# tc08nh.net
KiCad netlist of a schematic drawn in EAGLE
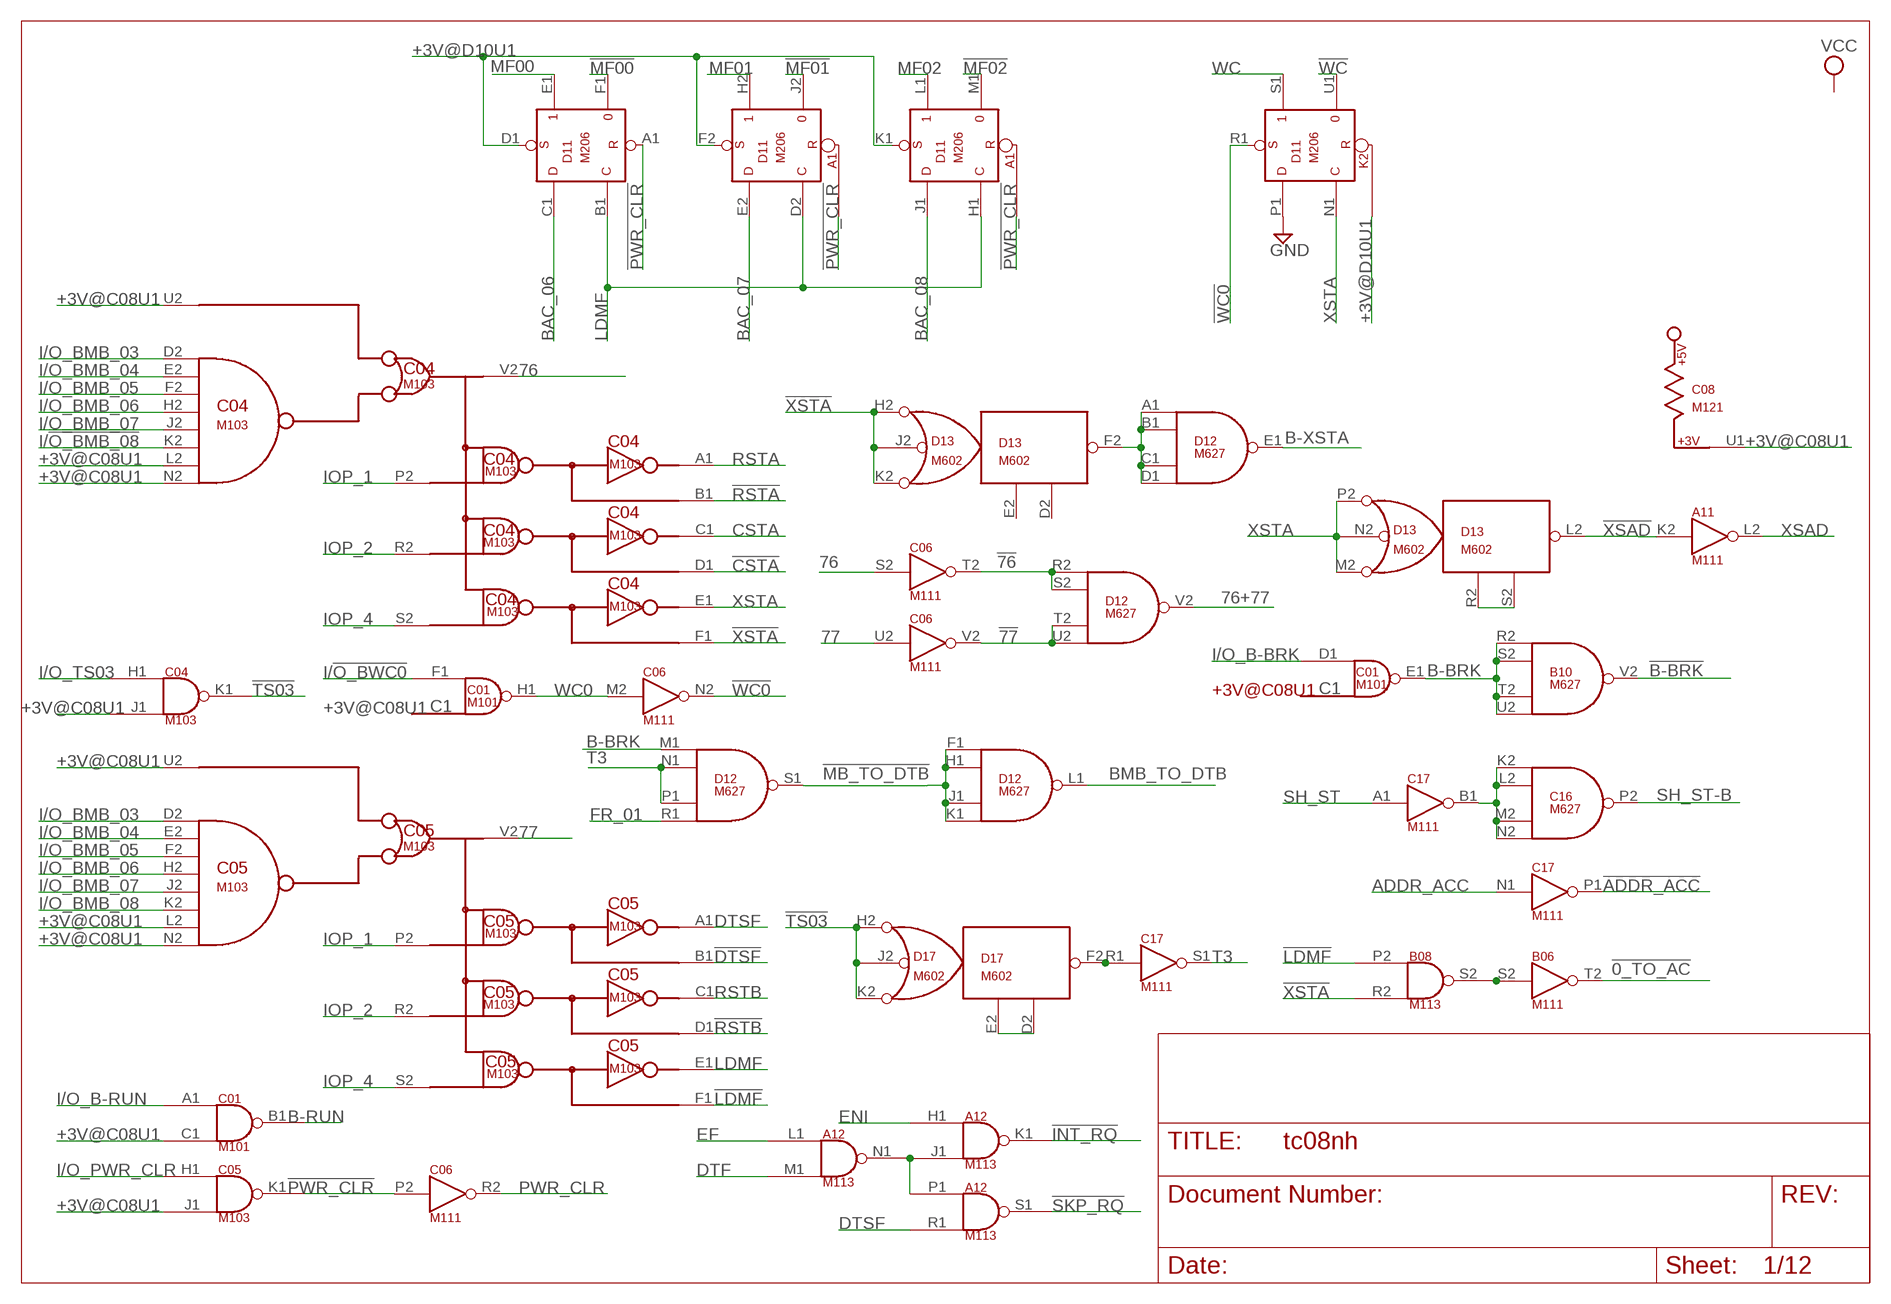
[diagram p0: schematic, sheet 1]
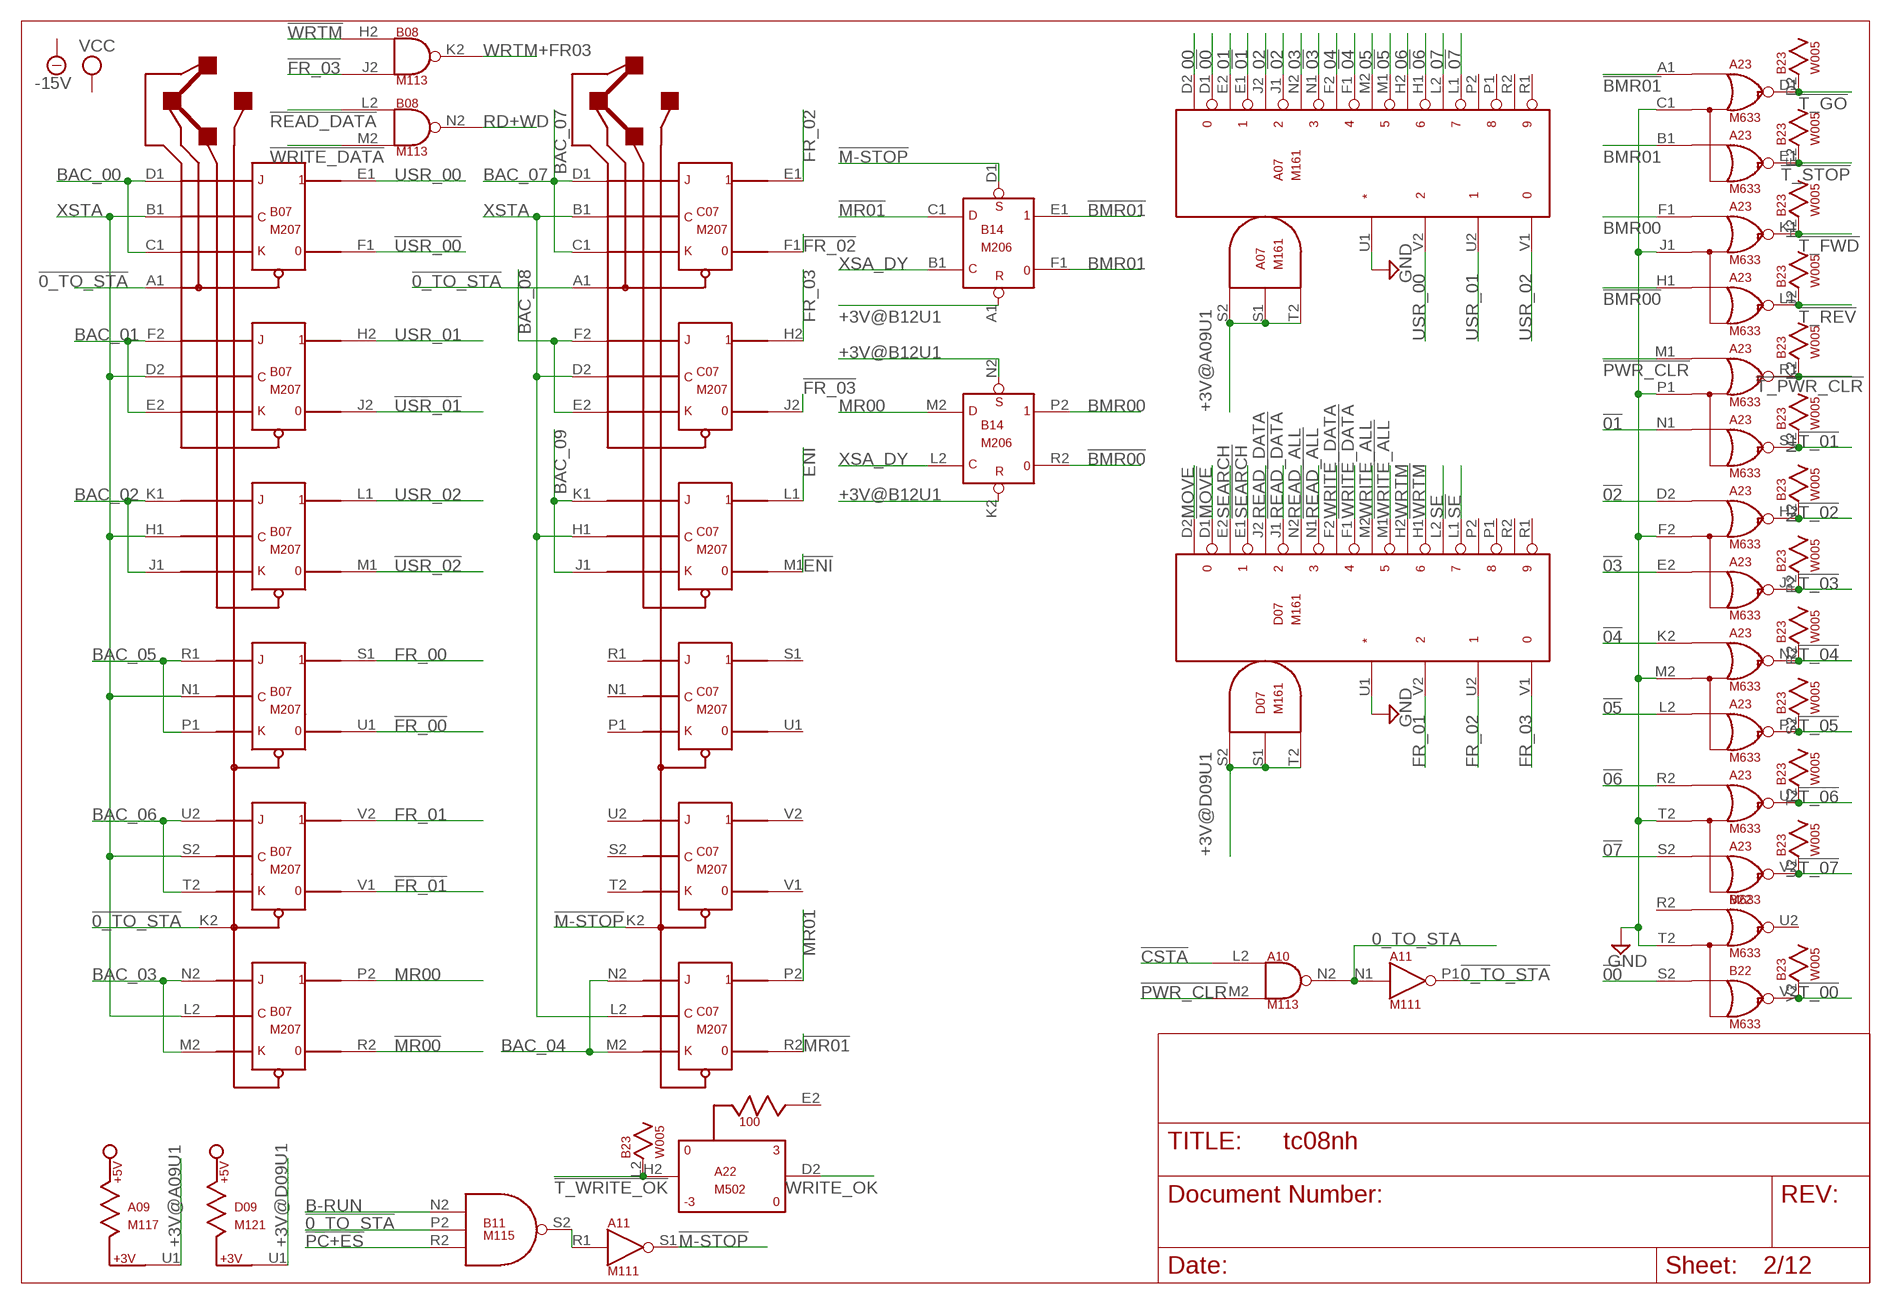
[diagram p1: schematic, sheet 2]
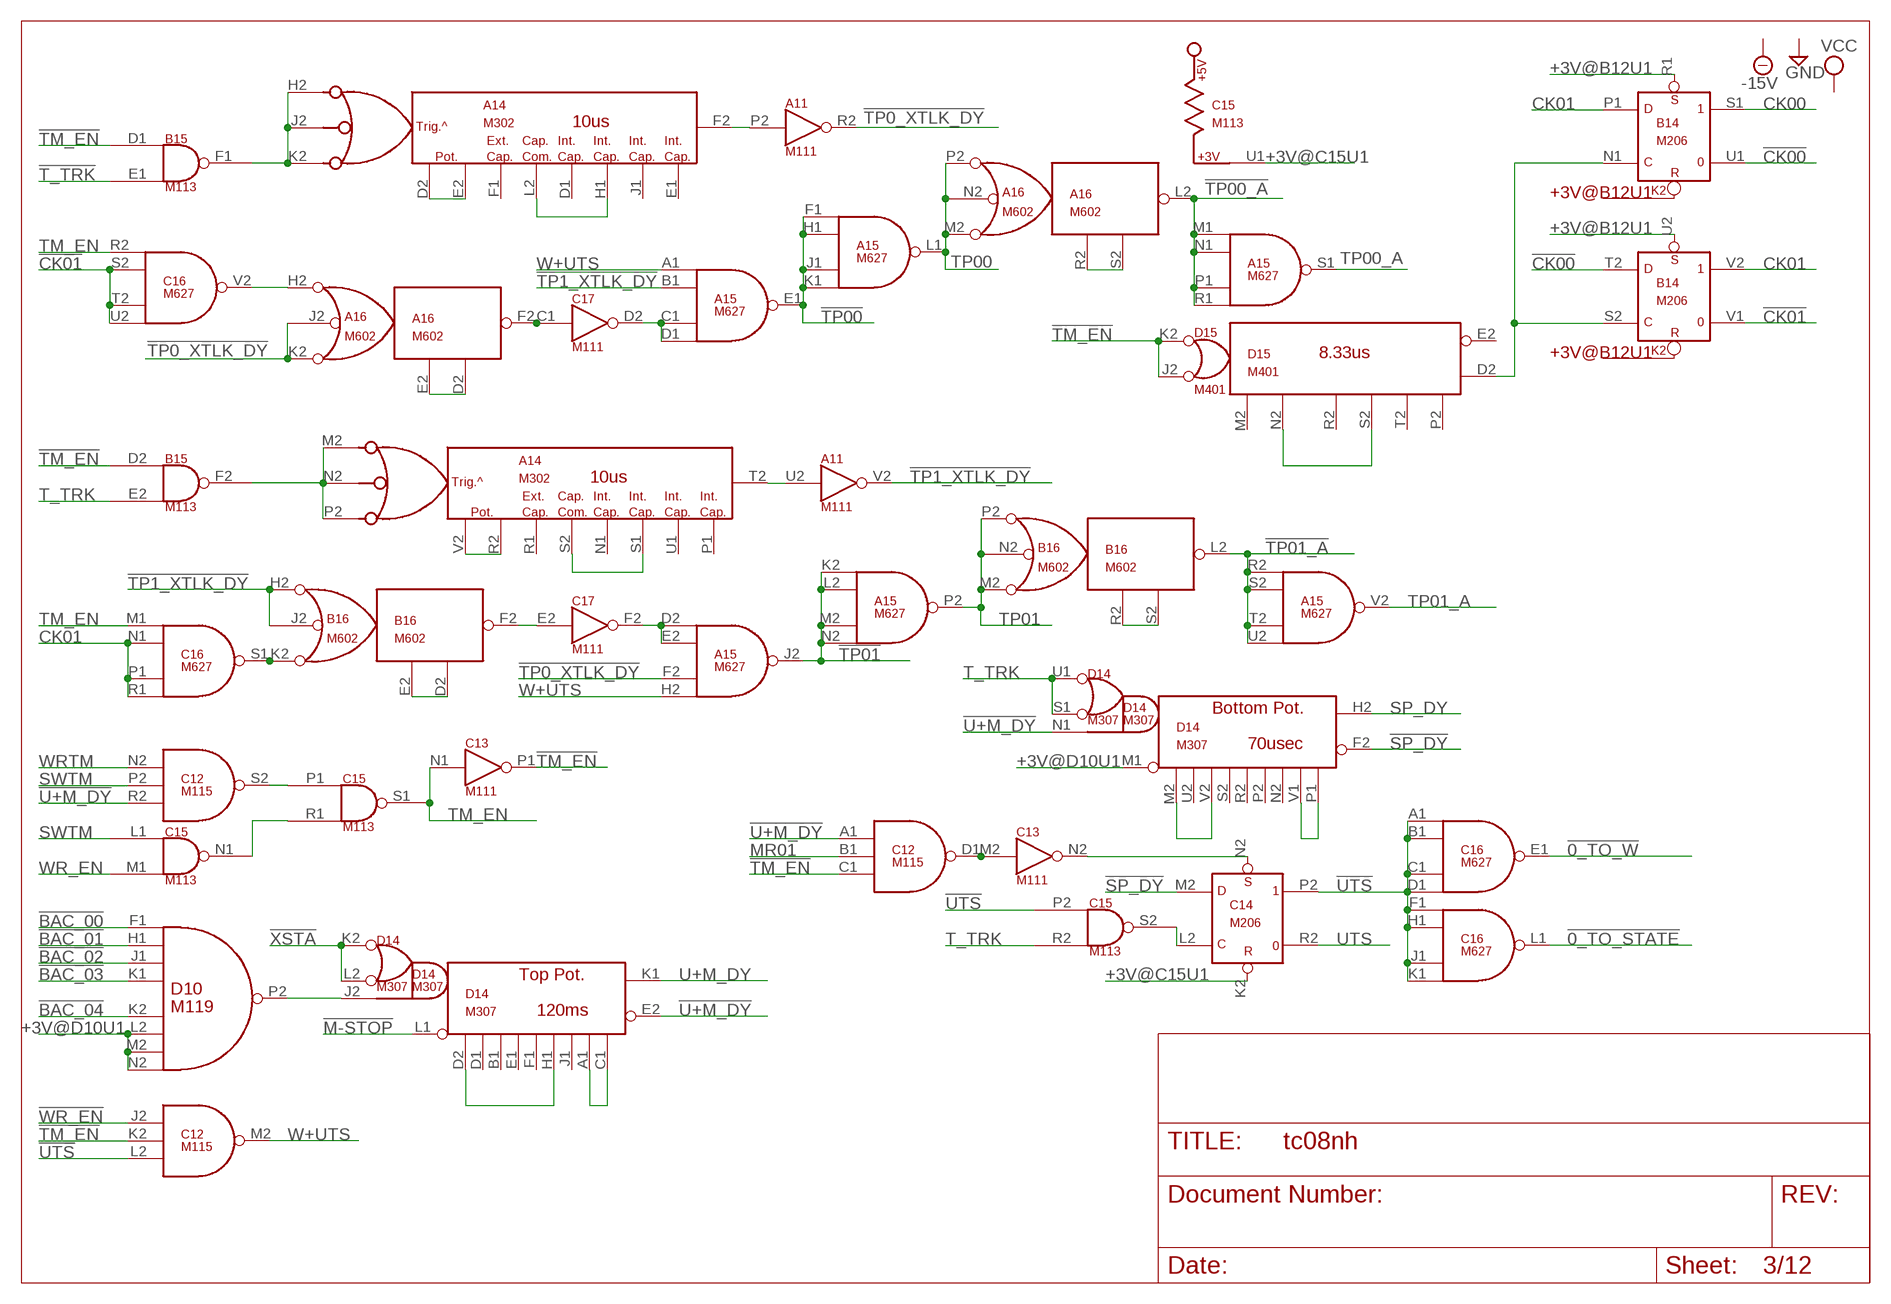
[diagram p2: schematic, sheet 3]
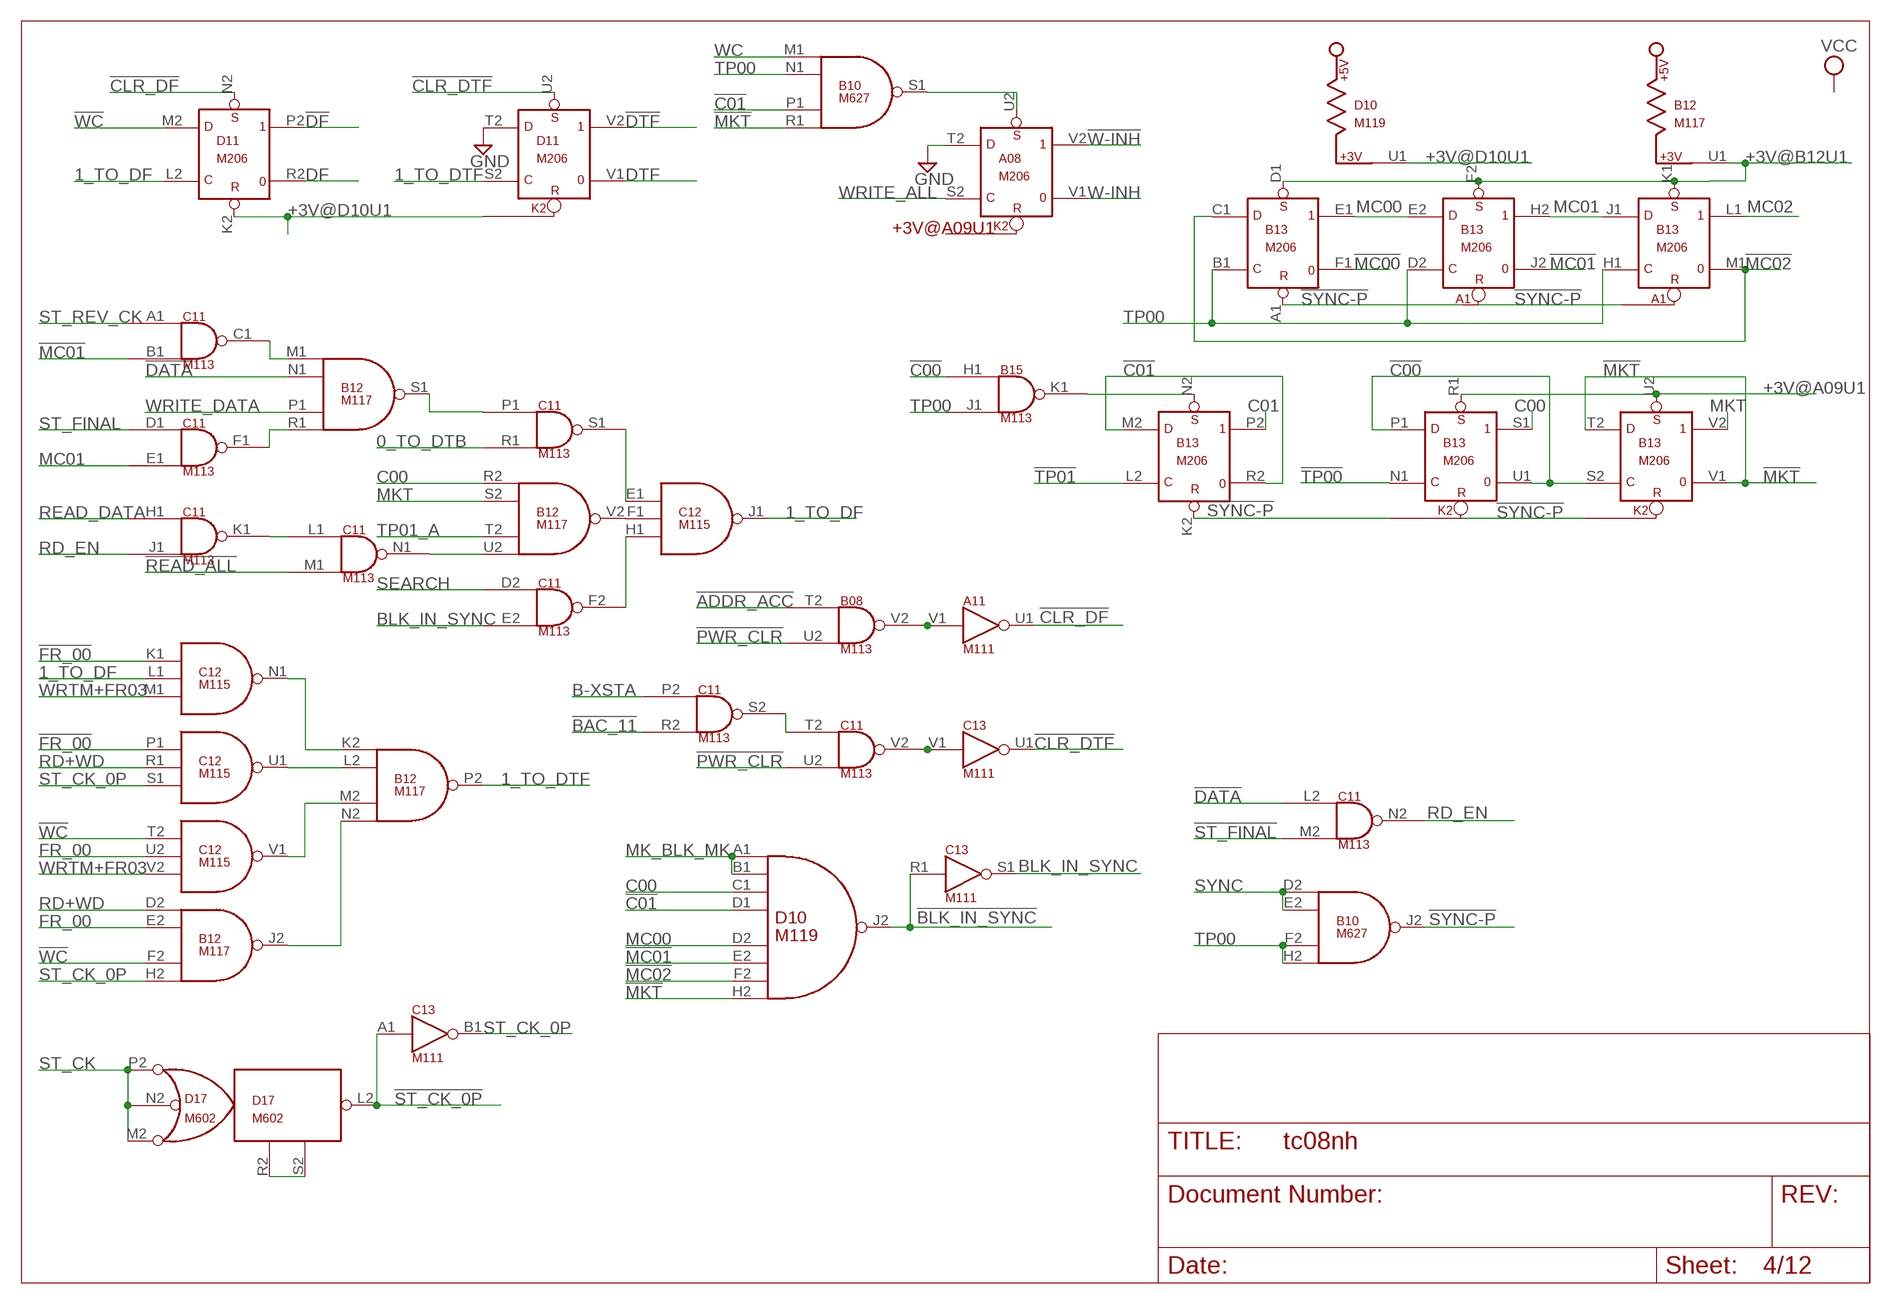
[diagram p3: schematic, sheet 4]
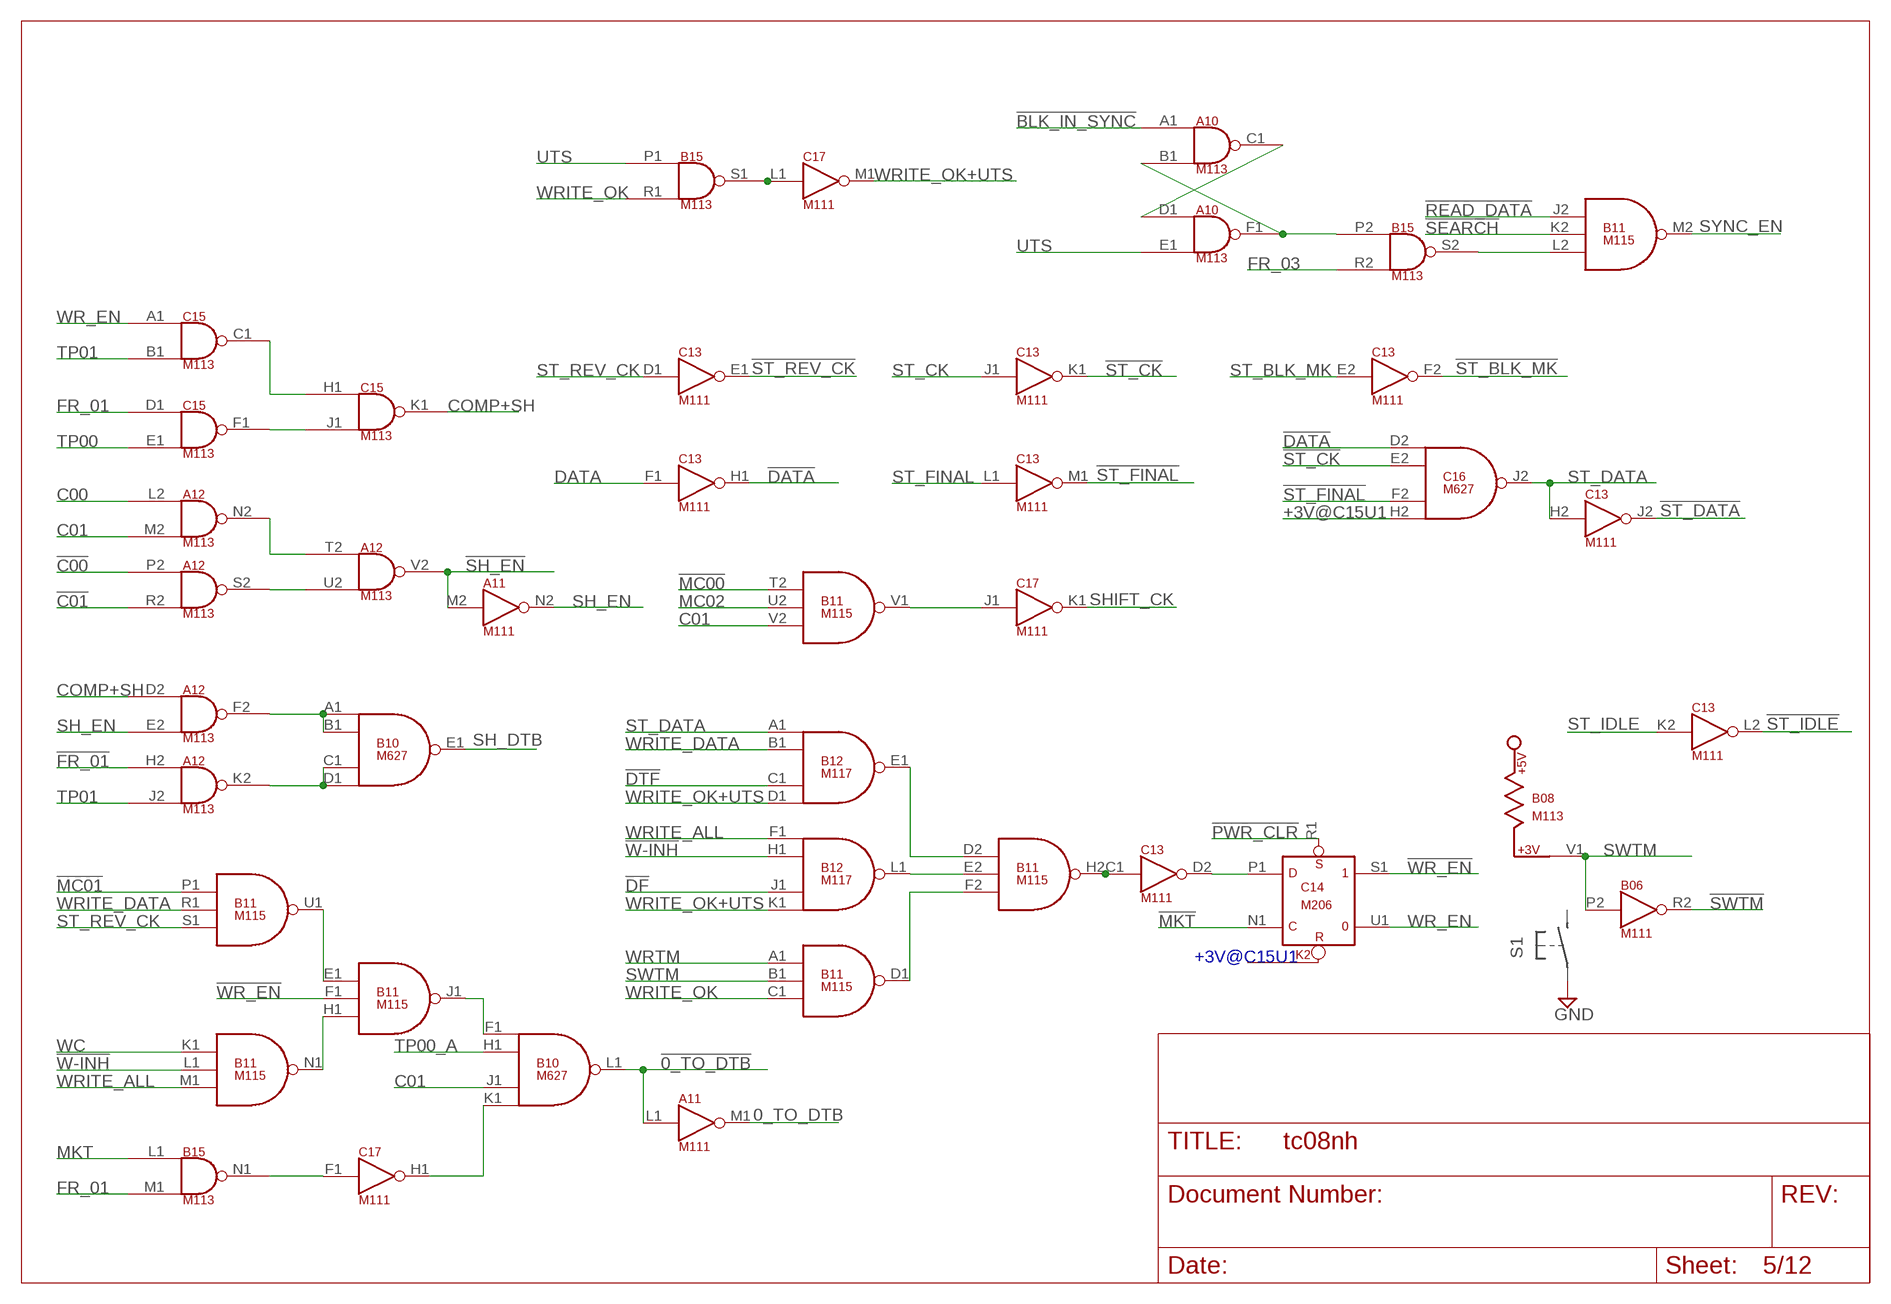
[diagram p4: schematic, sheet 5]
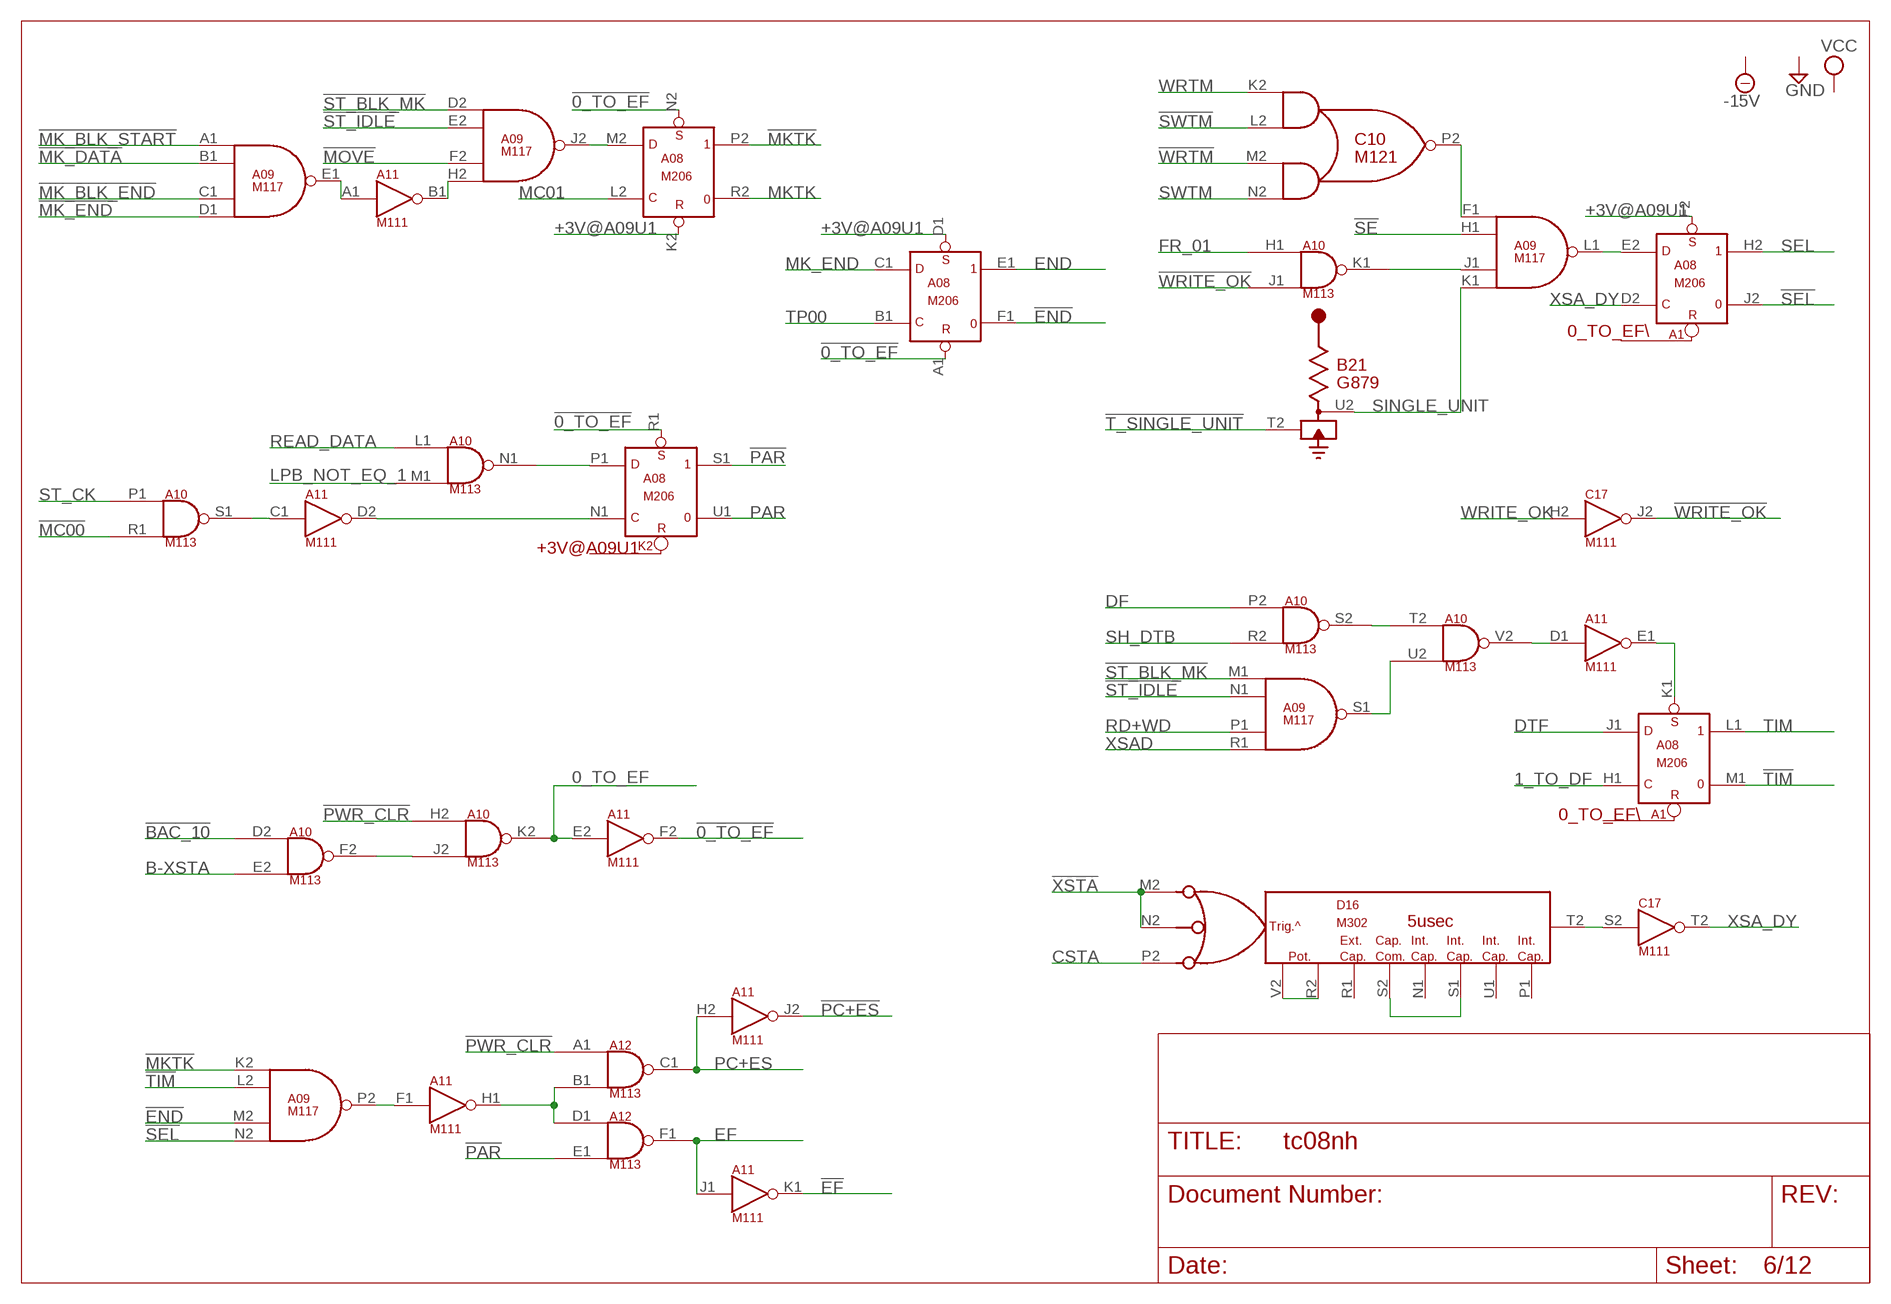
[diagram p5: schematic, sheet 6]
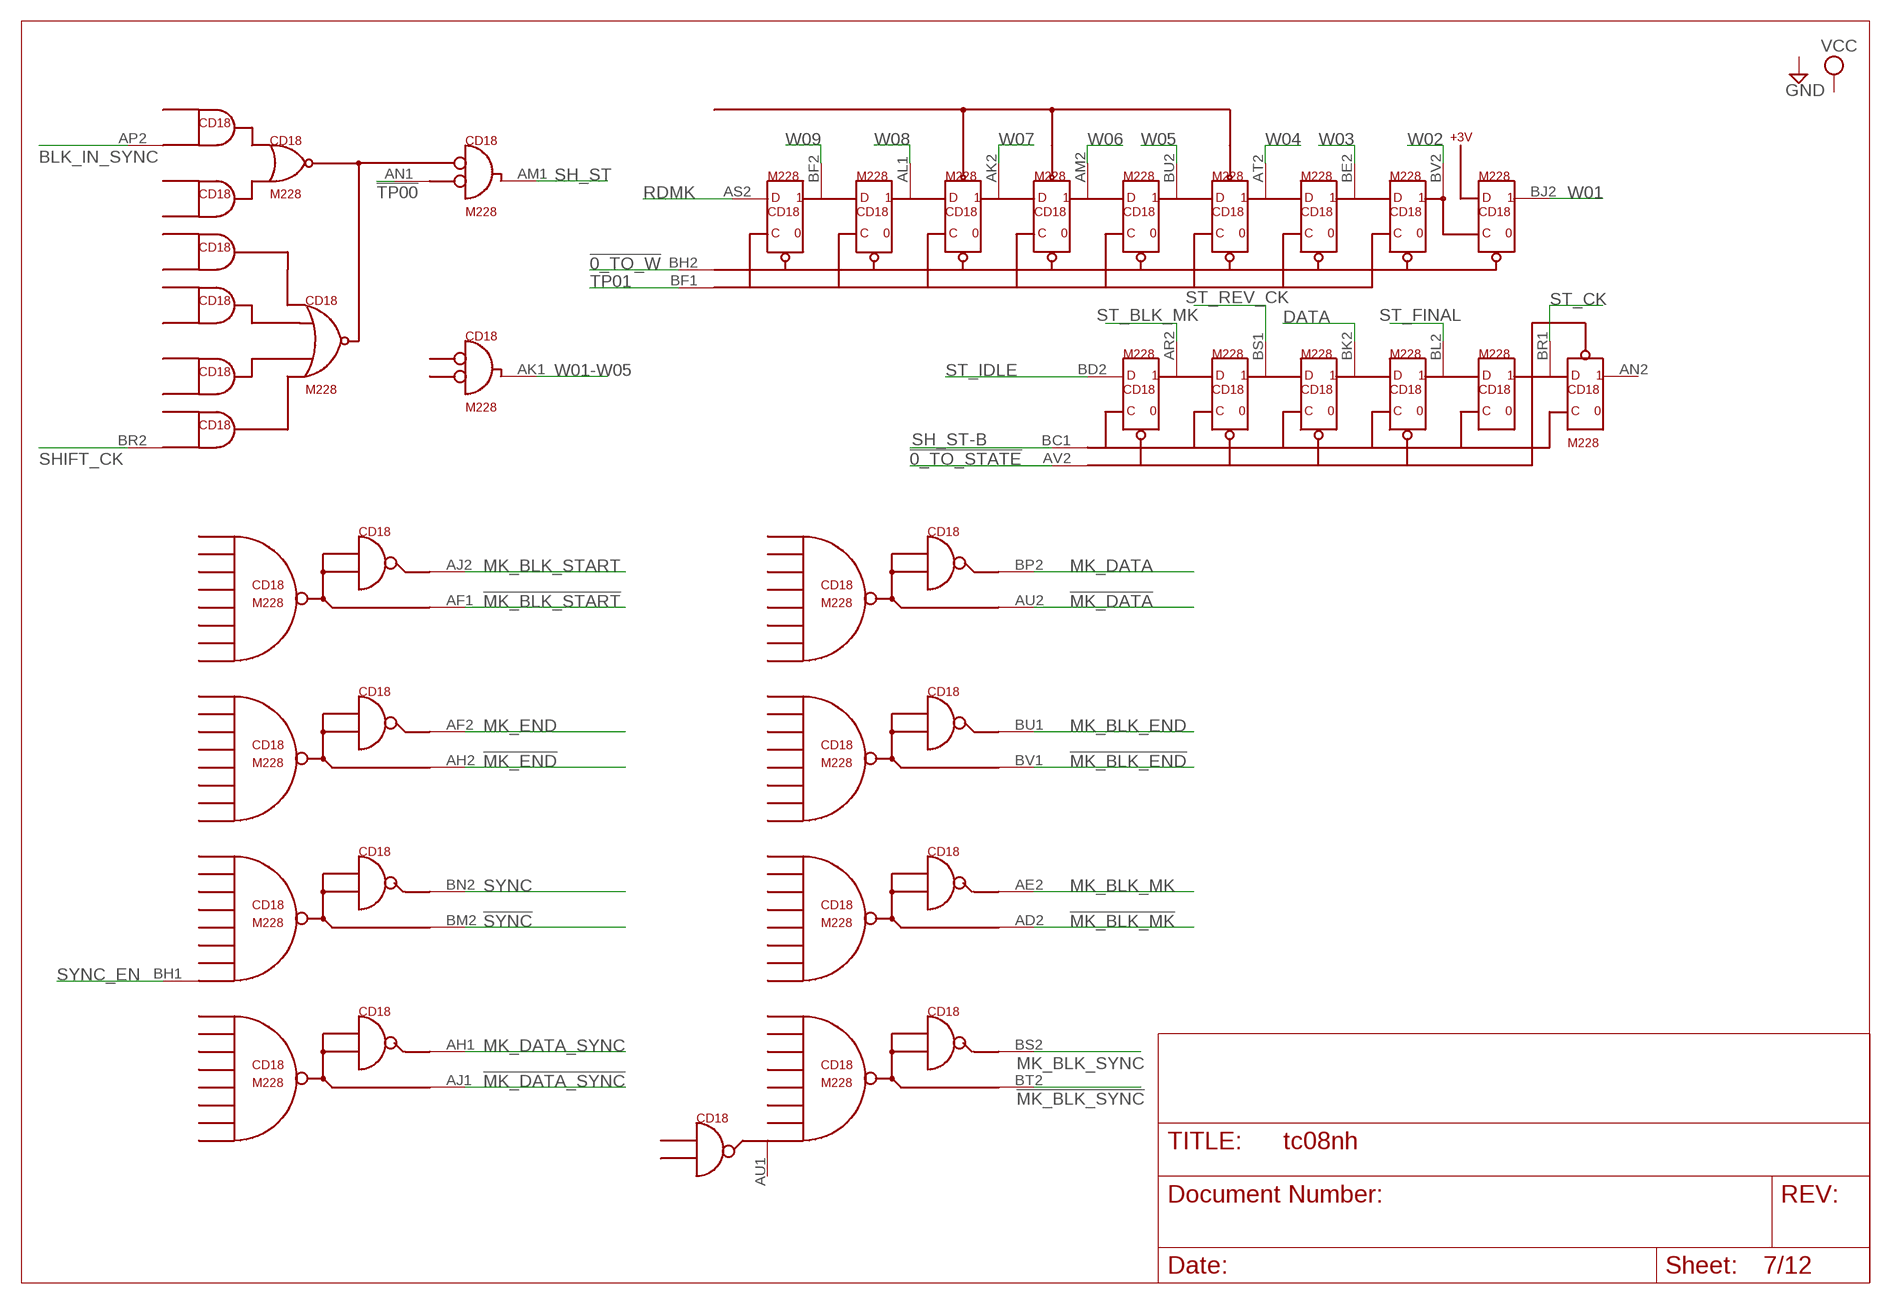
[diagram p6: schematic, sheet 7]
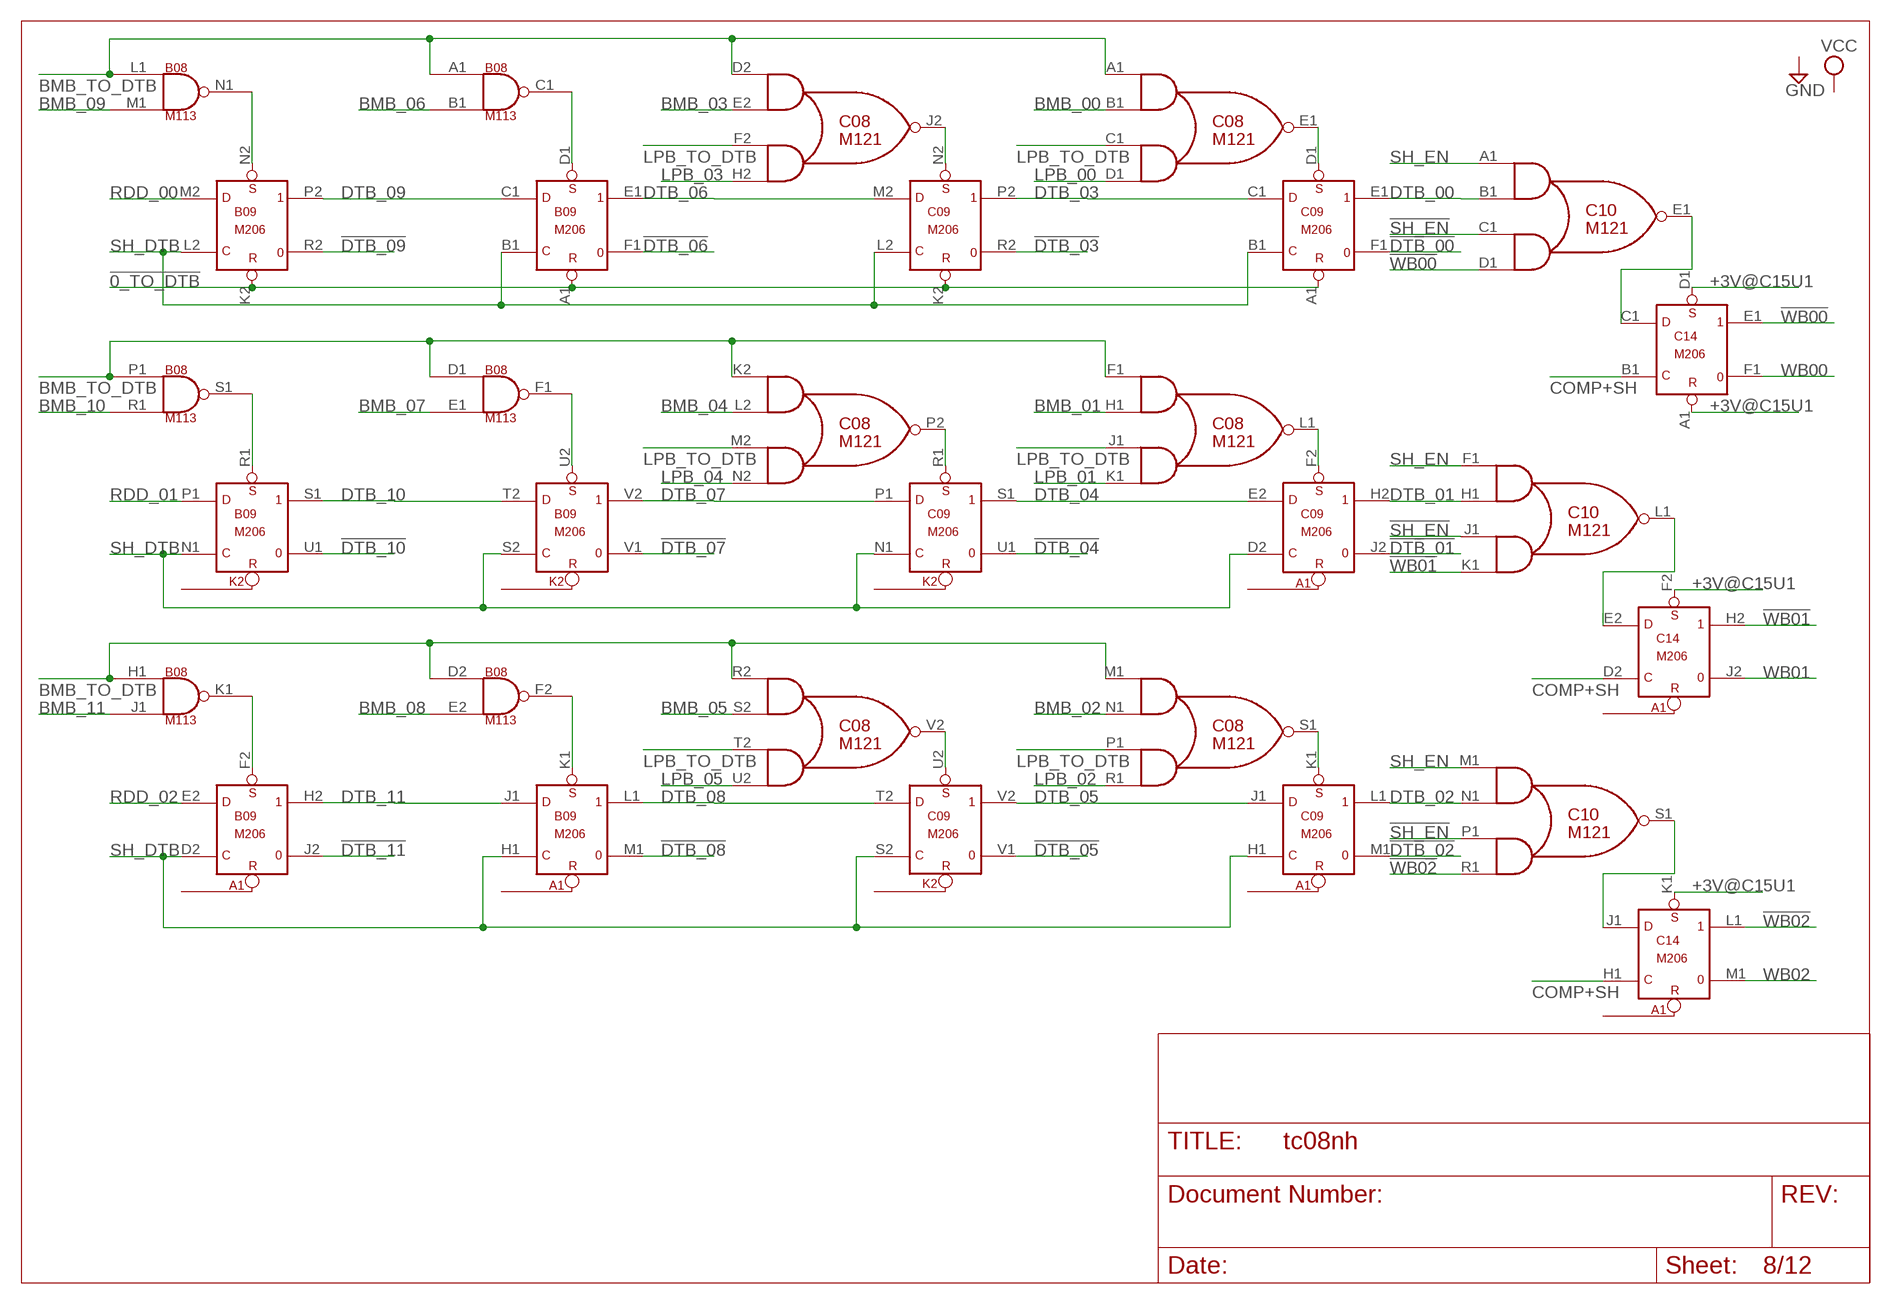
[diagram p7: schematic, sheet 8]
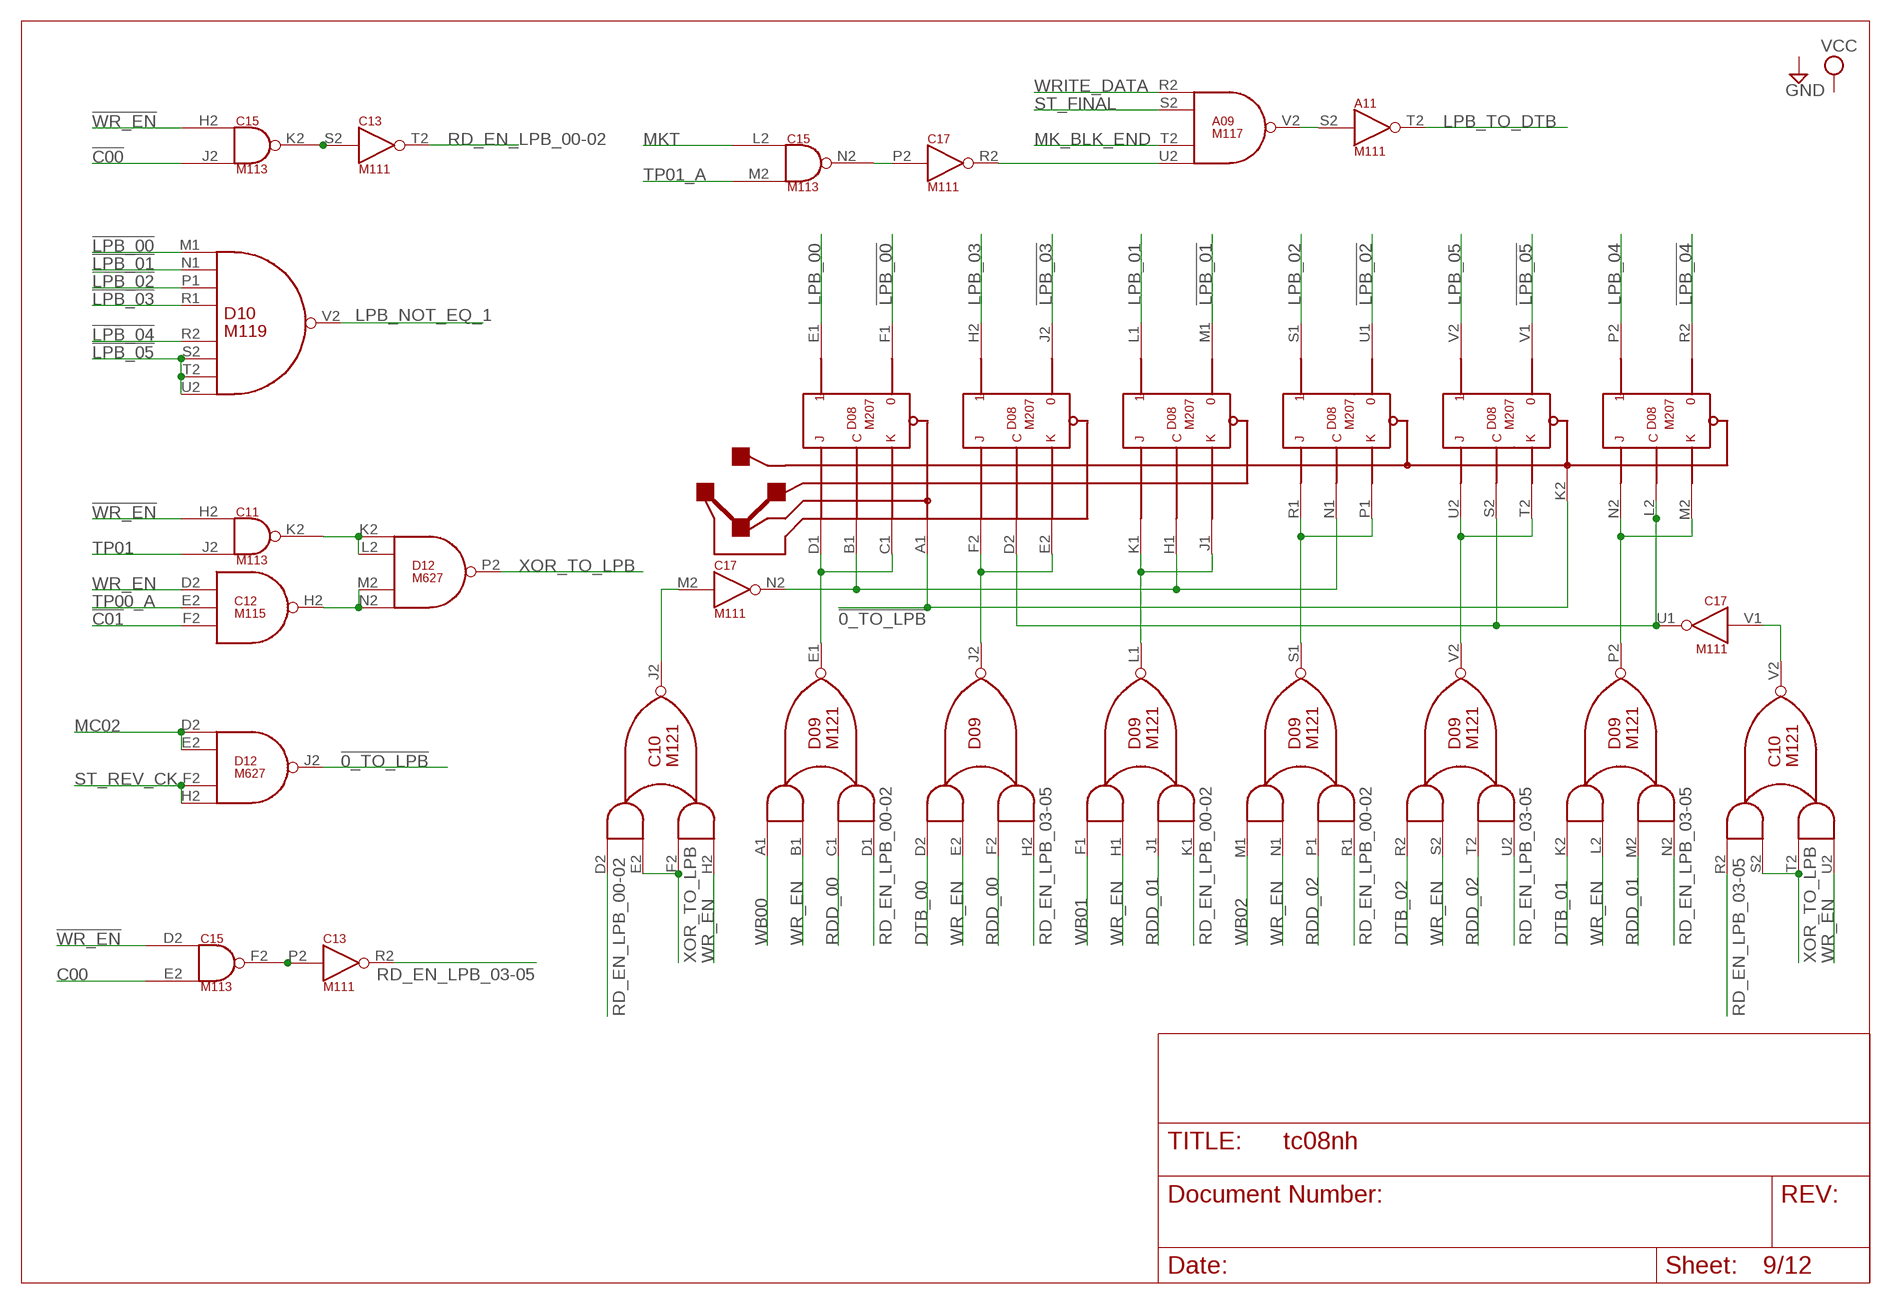
[diagram p8: schematic, sheet 9]
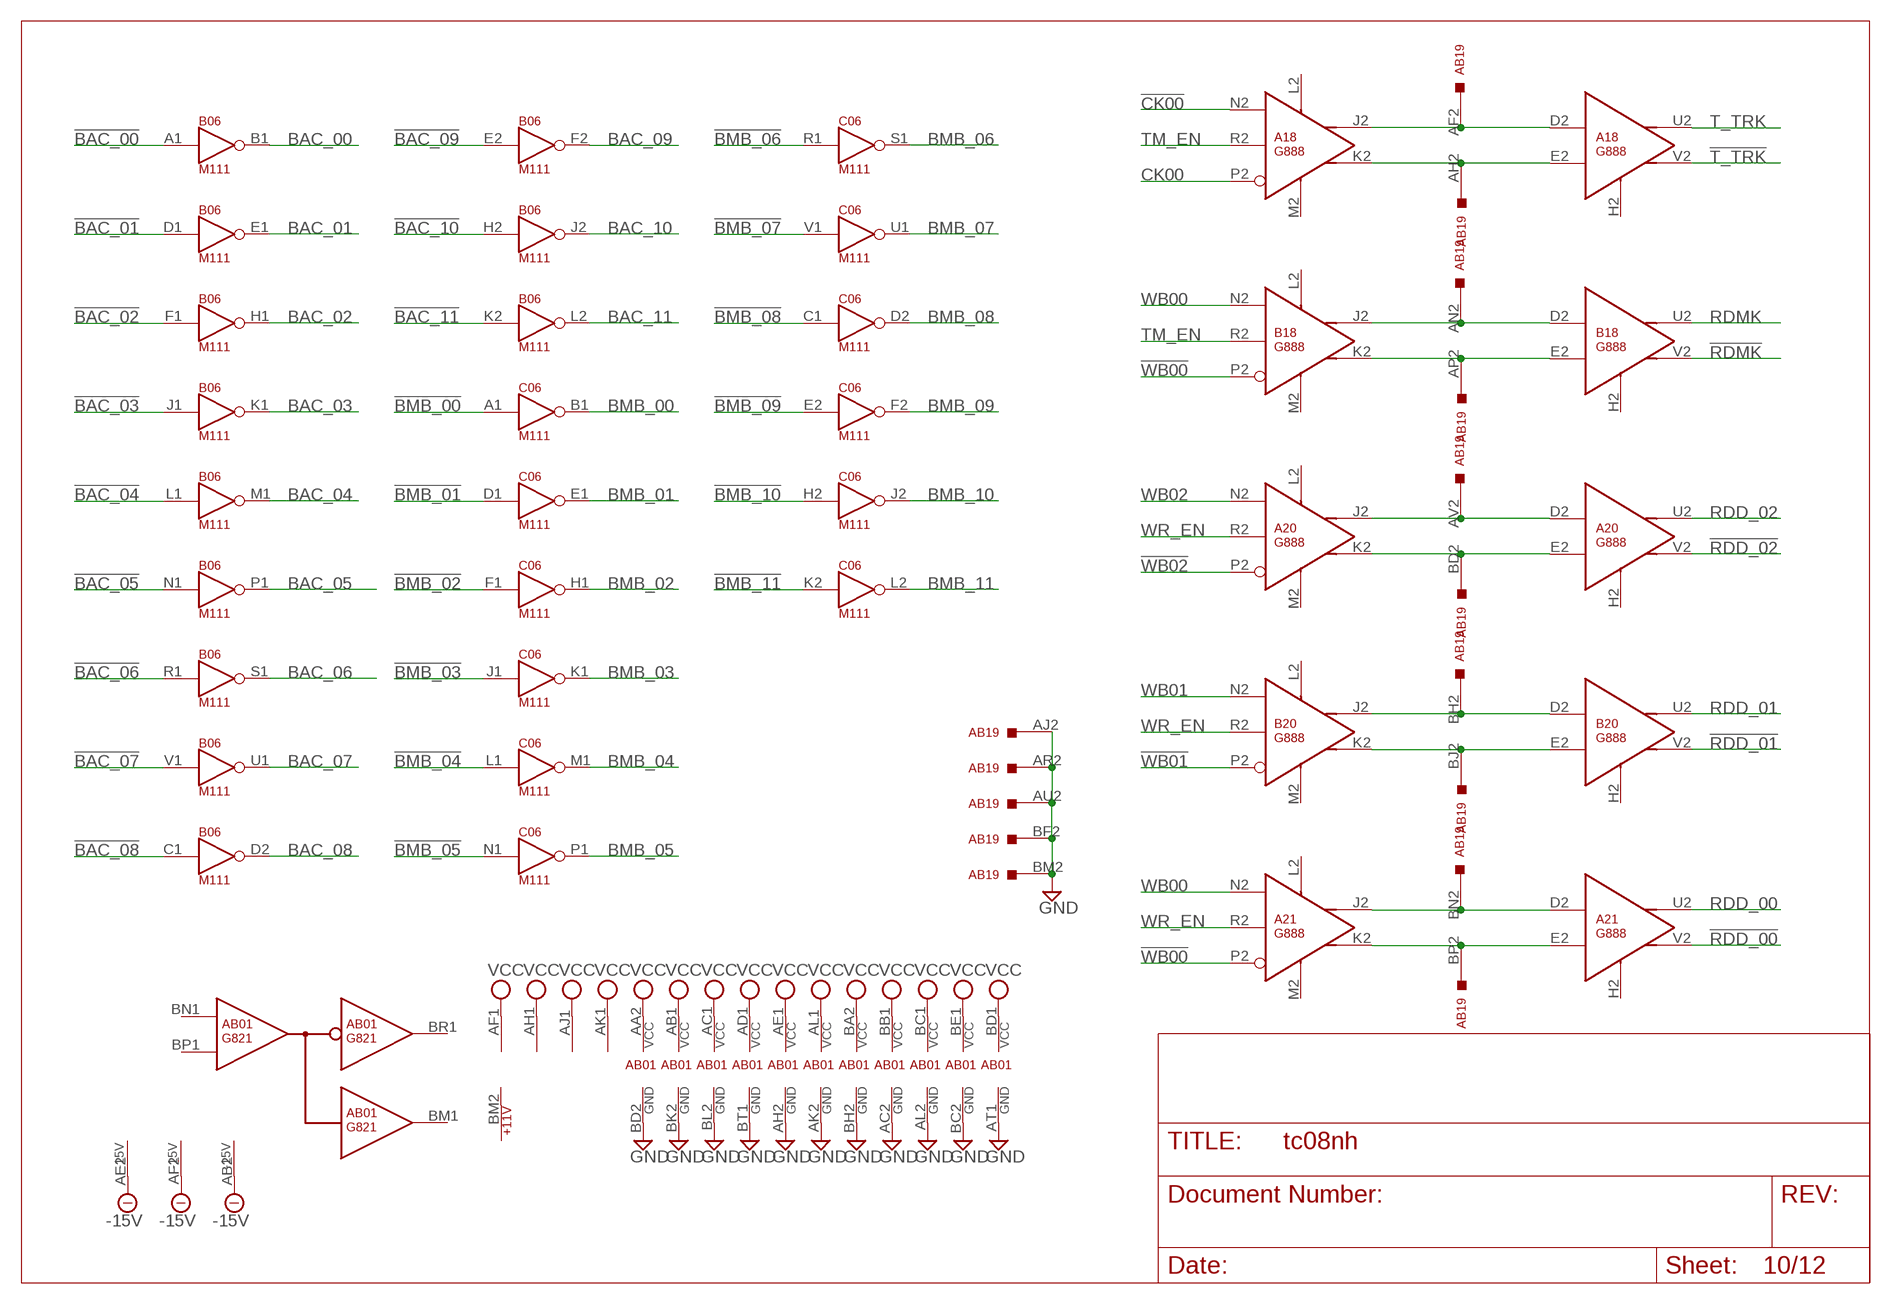
[diagram p9: schematic, sheet 10]
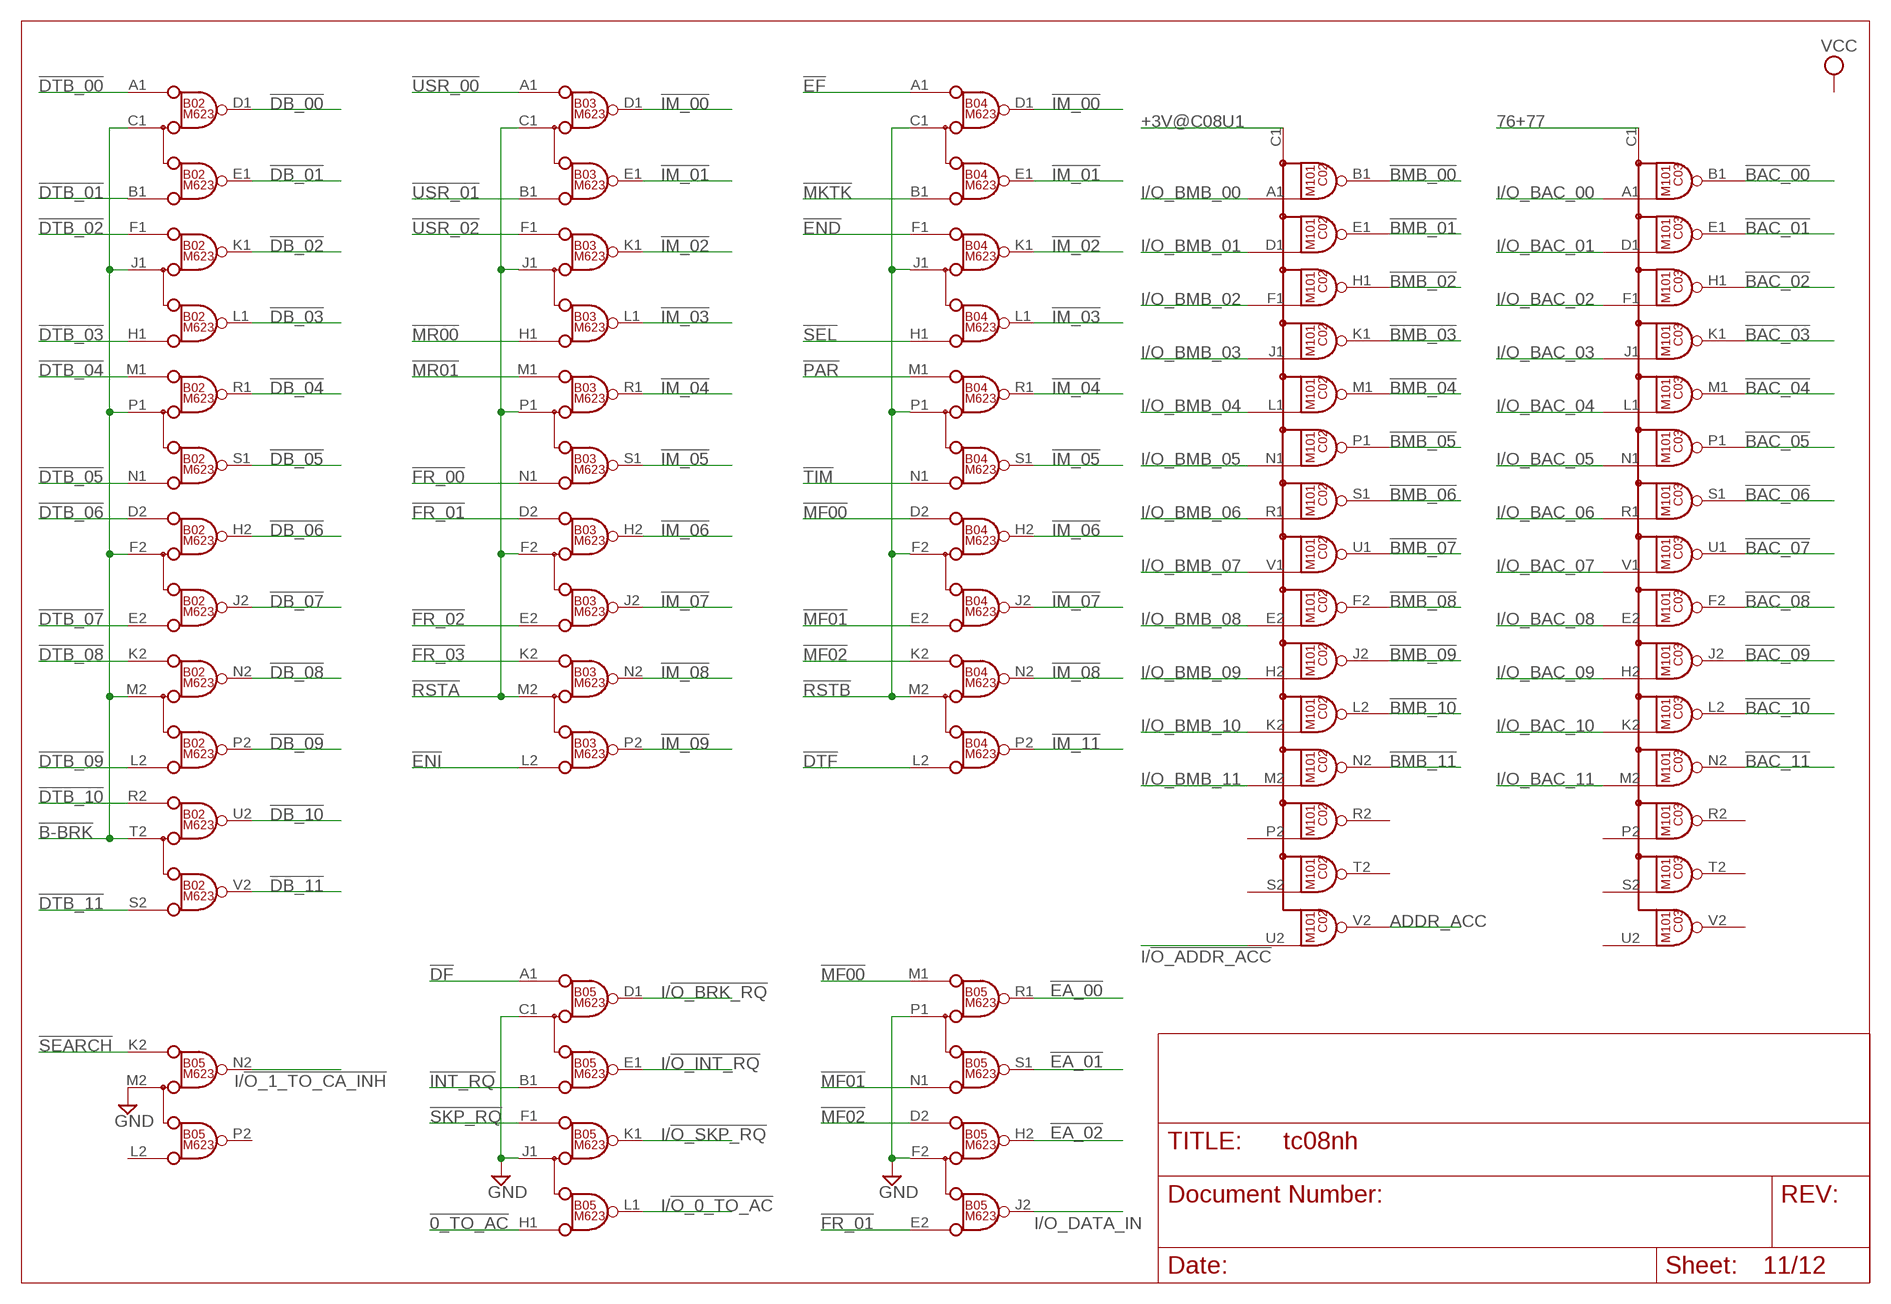
[diagram p10: schematic, sheet 11]
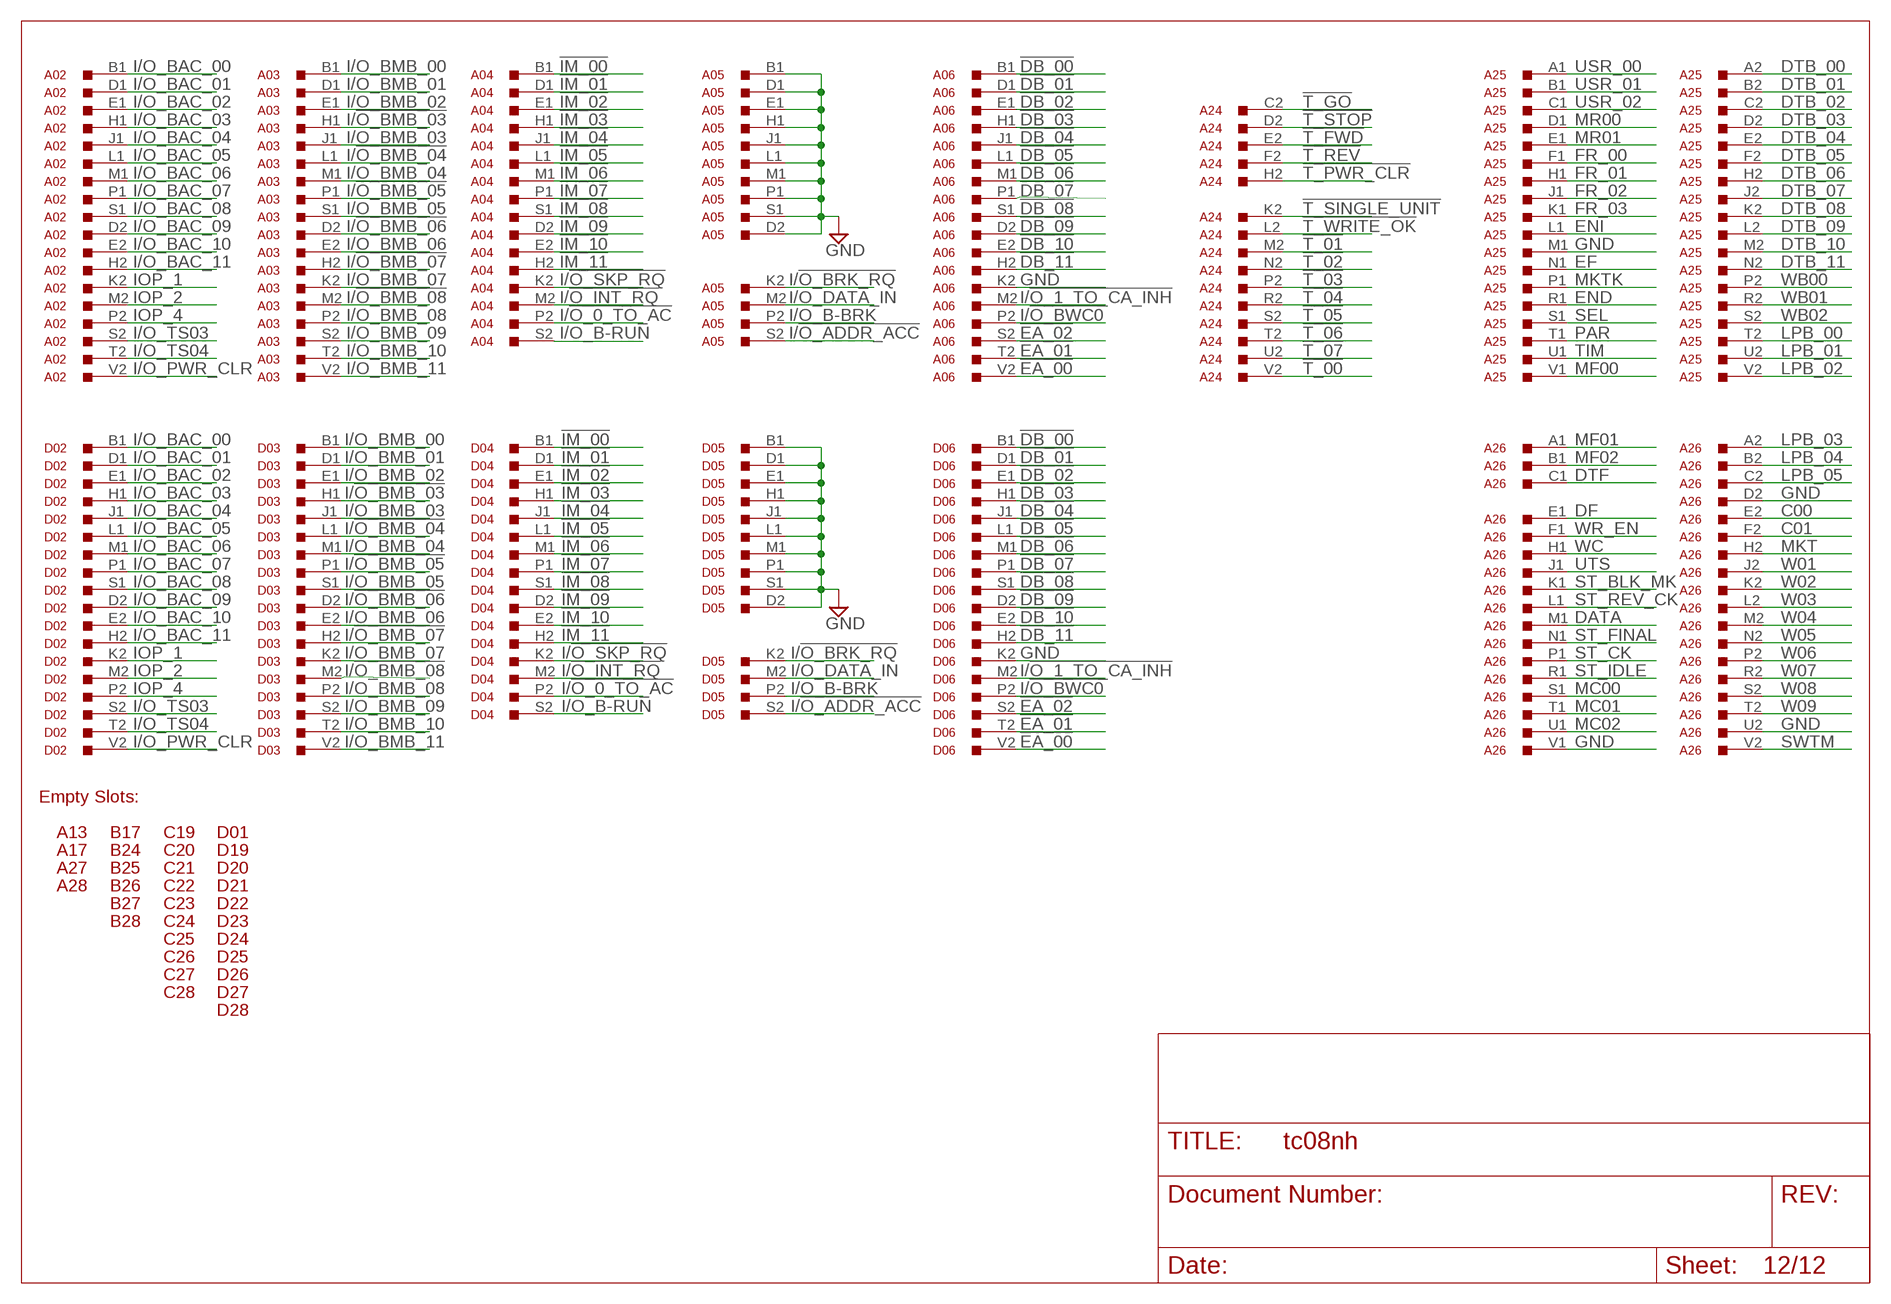
[diagram p11: schematic, sheet 12]

(export (version "E")
  (design (tool "Eeschema 10.0.6"))
  (components
    (comp (ref "B08")
      (value "M113")
      (footprint "eagle-import:H807")
      (libsource (lib "eagle-import") (part "M113"))
    )
    (comp (ref "B09")
      (value "M206")
      (footprint "eagle-import:H807")
      (libsource (lib "eagle-import") (part "M206X"))
    )
    (comp (ref "C08")
      (value "M121")
      (footprint "eagle-import:H807")
      (libsource (lib "eagle-import") (part "M121"))
    )
    (comp (ref "C09")
      (value "M206")
      (footprint "eagle-import:H807")
      (libsource (lib "eagle-import") (part "M206X"))
    )
    (comp (ref "C10")
      (value "M121")
      (footprint "eagle-import:H807")
      (libsource (lib "eagle-import") (part "M121"))
    )
    (comp (ref "C14")
      (value "M206")
      (footprint "eagle-import:H807")
      (libsource (lib "eagle-import") (part "M206X"))
    )
    (comp (ref "A09")
      (value "M117")
      (footprint "eagle-import:H807")
      (libsource (lib "eagle-import") (part "M117"))
    )
    (comp (ref "A11")
      (value "M111")
      (footprint "eagle-import:H807")
      (libsource (lib "eagle-import") (part "M111"))
    )
    (comp (ref "C11")
      (value "M113")
      (footprint "eagle-import:H807")
      (libsource (lib "eagle-import") (part "M113"))
    )
    (comp (ref "C12")
      (value "M115")
      (footprint "eagle-import:H807")
      (libsource (lib "eagle-import") (part "M115"))
    )
    (comp (ref "C13")
      (value "M111")
      (footprint "eagle-import:H807")
      (libsource (lib "eagle-import") (part "M111"))
    )
    (comp (ref "C15")
      (value "M113")
      (footprint "eagle-import:H807")
      (libsource (lib "eagle-import") (part "M113"))
    )
    (comp (ref "C17")
      (value "M111")
      (footprint "eagle-import:H807")
      (libsource (lib "eagle-import") (part "M111"))
    )
    (comp (ref "D08")
      (value "M207")
      (footprint "eagle-import:H807")
      (libsource (lib "eagle-import") (part "M207"))
    )
    (comp (ref "D09")
      (value "M121")
      (footprint "eagle-import:H807")
      (libsource (lib "eagle-import") (part "M121"))
    )
    (comp (ref "D10")
      (value "M119")
      (footprint "eagle-import:H807")
      (libsource (lib "eagle-import") (part "M119"))
    )
    (comp (ref "D12")
      (value "M627")
      (footprint "eagle-import:H807")
      (libsource (lib "eagle-import") (part "M627"))
    )
    (comp (ref "A08")
      (value "M206")
      (footprint "eagle-import:H807")
      (libsource (lib "eagle-import") (part "M206X"))
    )
    (comp (ref "B10")
      (value "M627")
      (footprint "eagle-import:H807")
      (libsource (lib "eagle-import") (part "M627"))
    )
    (comp (ref "B12")
      (value "M117")
      (footprint "eagle-import:H807")
      (libsource (lib "eagle-import") (part "M117"))
    )
    (comp (ref "B13")
      (value "M206")
      (footprint "eagle-import:H807")
      (libsource (lib "eagle-import") (part "M206X"))
    )
    (comp (ref "B15")
      (value "M113")
      (footprint "eagle-import:H807")
      (libsource (lib "eagle-import") (part "M113"))
    )
    (comp (ref "D11")
      (value "M206")
      (footprint "eagle-import:H807")
      (libsource (lib "eagle-import") (part "M206X"))
    )
    (comp (ref "D17")
      (value "M602")
      (footprint "eagle-import:H807")
      (libsource (lib "eagle-import") (part "M602"))
    )
    (comp (ref "A14")
      (value "M302")
      (footprint "eagle-import:H807")
      (libsource (lib "eagle-import") (part "M302"))
    )
    (comp (ref "A15")
      (value "M627")
      (footprint "eagle-import:H807")
      (libsource (lib "eagle-import") (part "M627"))
    )
    (comp (ref "A16")
      (value "M602")
      (footprint "eagle-import:H807")
      (libsource (lib "eagle-import") (part "M602"))
    )
    (comp (ref "B14")
      (value "M206")
      (footprint "eagle-import:H807")
      (libsource (lib "eagle-import") (part "M206X"))
    )
    (comp (ref "B16")
      (value "M602")
      (footprint "eagle-import:H807")
      (libsource (lib "eagle-import") (part "M602"))
    )
    (comp (ref "C16")
      (value "M627")
      (footprint "eagle-import:H807")
      (libsource (lib "eagle-import") (part "M627"))
    )
    (comp (ref "D14")
      (value "M307")
      (footprint "eagle-import:H807")
      (libsource (lib "eagle-import") (part "M307"))
    )
    (comp (ref "D15")
      (value "M401")
      (footprint "eagle-import:H807")
      (libsource (lib "eagle-import") (part "M401"))
    )
    (comp (ref "B02")
      (value "M623")
      (footprint "eagle-import:H807")
      (libsource (lib "eagle-import") (part "M623"))
    )
    (comp (ref "B03")
      (value "M623")
      (footprint "eagle-import:H807")
      (libsource (lib "eagle-import") (part "M623"))
    )
    (comp (ref "B04")
      (value "M623")
      (footprint "eagle-import:H807")
      (libsource (lib "eagle-import") (part "M623"))
    )
    (comp (ref "B05")
      (value "M623")
      (footprint "eagle-import:H807")
      (libsource (lib "eagle-import") (part "M623"))
    )
    (comp (ref "C02")
      (value "M101")
      (footprint "eagle-import:H807")
      (libsource (lib "eagle-import") (part "M101-ARRAY"))
    )
    (comp (ref "C03")
      (value "M101")
      (footprint "eagle-import:H807")
      (libsource (lib "eagle-import") (part "M101-ARRAY"))
    )
    (comp (ref "A02")
      (value "M903")
      (footprint "eagle-import:H807")
      (libsource (lib "eagle-import") (part "M903"))
    )
    (comp (ref "A03")
      (value "M903")
      (footprint "eagle-import:H807")
      (libsource (lib "eagle-import") (part "M903"))
    )
    (comp (ref "A04")
      (value "M903")
      (footprint "eagle-import:H807")
      (libsource (lib "eagle-import") (part "M903"))
    )
    (comp (ref "A05")
      (value "M903")
      (footprint "eagle-import:H807")
      (libsource (lib "eagle-import") (part "M903"))
    )
    (comp (ref "A06")
      (value "M903")
      (footprint "eagle-import:H807")
      (libsource (lib "eagle-import") (part "M903"))
    )
    (comp (ref "A13")
      (value "H807")
      (footprint "eagle-import:H807")
      (libsource (lib "eagle-import") (part "H807"))
    )
    (comp (ref "A17")
      (value "H807")
      (footprint "eagle-import:H807")
      (libsource (lib "eagle-import") (part "H807"))
    )
    (comp (ref "A24")
      (value "W023")
      (footprint "eagle-import:H807")
      (libsource (lib "eagle-import") (part "W023"))
    )
    (comp (ref "A25")
      (value "M916")
      (footprint "eagle-import:H807")
      (libsource (lib "eagle-import") (part "M916"))
    )
    (comp (ref "A26")
      (value "M916")
      (footprint "eagle-import:H807")
      (libsource (lib "eagle-import") (part "M916"))
    )
    (comp (ref "A27")
      (value "H807")
      (footprint "eagle-import:H807")
      (libsource (lib "eagle-import") (part "H807"))
    )
    (comp (ref "A28")
      (value "H807")
      (footprint "eagle-import:H807")
      (libsource (lib "eagle-import") (part "H807"))
    )
    (comp (ref "B17")
      (value "H807")
      (footprint "eagle-import:H807")
      (libsource (lib "eagle-import") (part "H807"))
    )
    (comp (ref "B24")
      (value "H807")
      (footprint "eagle-import:H807")
      (libsource (lib "eagle-import") (part "H807"))
    )
    (comp (ref "B25")
      (value "H807")
      (footprint "eagle-import:H807")
      (libsource (lib "eagle-import") (part "H807"))
    )
    (comp (ref "B26")
      (value "H807")
      (footprint "eagle-import:H807")
      (libsource (lib "eagle-import") (part "H807"))
    )
    (comp (ref "B27")
      (value "H807")
      (footprint "eagle-import:H807")
      (libsource (lib "eagle-import") (part "H807"))
    )
    (comp (ref "B28")
      (value "H807")
      (footprint "eagle-import:H807")
      (libsource (lib "eagle-import") (part "H807"))
    )
    (comp (ref "C19")
      (value "H807")
      (footprint "eagle-import:H807")
      (libsource (lib "eagle-import") (part "H807"))
    )
    (comp (ref "C20")
      (value "H807")
      (footprint "eagle-import:H807")
      (libsource (lib "eagle-import") (part "H807"))
    )
    (comp (ref "C21")
      (value "H807")
      (footprint "eagle-import:H807")
      (libsource (lib "eagle-import") (part "H807"))
    )
    (comp (ref "C22")
      (value "H807")
      (footprint "eagle-import:H807")
      (libsource (lib "eagle-import") (part "H807"))
    )
    (comp (ref "C23")
      (value "H807")
      (footprint "eagle-import:H807")
      (libsource (lib "eagle-import") (part "H807"))
    )
    (comp (ref "C24")
      (value "H807")
      (footprint "eagle-import:H807")
      (libsource (lib "eagle-import") (part "H807"))
    )
    (comp (ref "C25")
      (value "H807")
      (footprint "eagle-import:H807")
      (libsource (lib "eagle-import") (part "H807"))
    )
    (comp (ref "C26")
      (value "H807")
      (footprint "eagle-import:H807")
      (libsource (lib "eagle-import") (part "H807"))
    )
    (comp (ref "C27")
      (value "H807")
      (footprint "eagle-import:H807")
      (libsource (lib "eagle-import") (part "H807"))
    )
    (comp (ref "C28")
      (value "H807")
      (footprint "eagle-import:H807")
      (libsource (lib "eagle-import") (part "H807"))
    )
    (comp (ref "D01")
      (value "H807")
      (footprint "eagle-import:H807")
      (libsource (lib "eagle-import") (part "H807"))
    )
    (comp (ref "D02")
      (value "M903")
      (footprint "eagle-import:H807")
      (libsource (lib "eagle-import") (part "M903"))
    )
    (comp (ref "D03")
      (value "M903")
      (footprint "eagle-import:H807")
      (libsource (lib "eagle-import") (part "M903"))
    )
    (comp (ref "D04")
      (value "M903")
      (footprint "eagle-import:H807")
      (libsource (lib "eagle-import") (part "M903"))
    )
    (comp (ref "D05")
      (value "M903")
      (footprint "eagle-import:H807")
      (libsource (lib "eagle-import") (part "M903"))
    )
    (comp (ref "D06")
      (value "M903")
      (footprint "eagle-import:H807")
      (libsource (lib "eagle-import") (part "M903"))
    )
    (comp (ref "D19")
      (value "H807")
      (footprint "eagle-import:H807")
      (libsource (lib "eagle-import") (part "H807"))
    )
    (comp (ref "D20")
      (value "H807")
      (footprint "eagle-import:H807")
      (libsource (lib "eagle-import") (part "H807"))
    )
    (comp (ref "D21")
      (value "H807")
      (footprint "eagle-import:H807")
      (libsource (lib "eagle-import") (part "H807"))
    )
    (comp (ref "D22")
      (value "H807")
      (footprint "eagle-import:H807")
      (libsource (lib "eagle-import") (part "H807"))
    )
    (comp (ref "D23")
      (value "H807")
      (footprint "eagle-import:H807")
      (libsource (lib "eagle-import") (part "H807"))
    )
    (comp (ref "D24")
      (value "H807")
      (footprint "eagle-import:H807")
      (libsource (lib "eagle-import") (part "H807"))
    )
    (comp (ref "D25")
      (value "H807")
      (footprint "eagle-import:H807")
      (libsource (lib "eagle-import") (part "H807"))
    )
    (comp (ref "D26")
      (value "H807")
      (footprint "eagle-import:H807")
      (libsource (lib "eagle-import") (part "H807"))
    )
    (comp (ref "D27")
      (value "H807")
      (footprint "eagle-import:H807")
      (libsource (lib "eagle-import") (part "H807"))
    )
    (comp (ref "D28")
      (value "H807")
      (footprint "eagle-import:H807")
      (libsource (lib "eagle-import") (part "H807"))
    )
    (comp (ref "CD18")
      (value "M228")
      (footprint "eagle-import:H807-2")
      (libsource (lib "eagle-import") (part "M228"))
    )
    (comp (ref "A07")
      (value "M161")
      (footprint "eagle-import:H807")
      (libsource (lib "eagle-import") (part "M161"))
    )
    (comp (ref "A10")
      (value "M113")
      (footprint "eagle-import:H807")
      (libsource (lib "eagle-import") (part "M113"))
    )
    (comp (ref "A22")
      (value "M502")
      (footprint "eagle-import:H807")
      (libsource (lib "eagle-import") (part "M502"))
    )
    (comp (ref "A23")
      (value "M633")
      (footprint "eagle-import:H807")
      (libsource (lib "eagle-import") (part "M633"))
    )
    (comp (ref "B07")
      (value "M207")
      (footprint "eagle-import:H807")
      (libsource (lib "eagle-import") (part "M207"))
    )
    (comp (ref "B11")
      (value "M115")
      (footprint "eagle-import:H807")
      (libsource (lib "eagle-import") (part "M115"))
    )
    (comp (ref "B22")
      (value "M633")
      (footprint "eagle-import:H807")
      (libsource (lib "eagle-import") (part "M633"))
    )
    (comp (ref "B23")
      (value "W005")
      (footprint "eagle-import:H807")
      (libsource (lib "eagle-import") (part "W005"))
    )
    (comp (ref "C07")
      (value "M207")
      (footprint "eagle-import:H807")
      (libsource (lib "eagle-import") (part "M207"))
    )
    (comp (ref "D07")
      (value "M161")
      (footprint "eagle-import:H807")
      (libsource (lib "eagle-import") (part "M161"))
    )
    (comp (ref "A18")
      (value "G888")
      (footprint "eagle-import:H807")
      (libsource (lib "eagle-import") (part "G888"))
    )
    (comp (ref "A20")
      (value "G888")
      (footprint "eagle-import:H807")
      (libsource (lib "eagle-import") (part "G888"))
    )
    (comp (ref "A21")
      (value "G888")
      (footprint "eagle-import:H807")
      (libsource (lib "eagle-import") (part "G888"))
    )
    (comp (ref "AB01")
      (value "G821")
      (footprint "eagle-import:H807-2")
      (libsource (lib "eagle-import") (part "G821"))
    )
    (comp (ref "AB19")
      (value "W032")
      (footprint "eagle-import:H807-2")
      (libsource (lib "eagle-import") (part "W032"))
    )
    (comp (ref "B06")
      (value "M111")
      (footprint "eagle-import:H807")
      (libsource (lib "eagle-import") (part "M111"))
    )
    (comp (ref "B18")
      (value "G888")
      (footprint "eagle-import:H807")
      (libsource (lib "eagle-import") (part "G888"))
    )
    (comp (ref "B20")
      (value "G888")
      (footprint "eagle-import:H807")
      (libsource (lib "eagle-import") (part "G888"))
    )
    (comp (ref "C06")
      (value "M111")
      (footprint "eagle-import:H807")
      (libsource (lib "eagle-import") (part "M111"))
    )
    (comp (ref "A12")
      (value "M113")
      (footprint "eagle-import:H807")
      (libsource (lib "eagle-import") (part "M113"))
    )
    (comp (ref "B21")
      (value "G879")
      (footprint "eagle-import:H807")
      (libsource (lib "eagle-import") (part "G879"))
    )
    (comp (ref "D16")
      (value "M302")
      (footprint "eagle-import:H807")
      (libsource (lib "eagle-import") (part "M302"))
    )
    (comp (ref "C01")
      (value "M101")
      (footprint "eagle-import:H807")
      (libsource (lib "eagle-import") (part "M101"))
    )
    (comp (ref "C04")
      (value "M103")
      (footprint "eagle-import:H807")
      (libsource (lib "eagle-import") (part "M103"))
    )
    (comp (ref "C05")
      (value "M103")
      (footprint "eagle-import:H807")
      (libsource (lib "eagle-import") (part "M103"))
    )
    (comp (ref "D13")
      (value "M602")
      (footprint "eagle-import:H807")
      (libsource (lib "eagle-import") (part "M602"))
    )
  )
  (nets
    (net (code "1") (name "+3V@A09U1") (class "Default")
      (node (ref "A07") (pin "S1") (pinfunction "EN2_S1") (pintype "input"))
      (node (ref "A07") (pin "S2") (pinfunction "EN1_S2") (pintype "input"))
      (node (ref "A07") (pin "T2") (pinfunction "EN3_T2") (pintype "input"))
      (node (ref "A08") (pin "D1") (pinfunction "S_D1") (pintype "input"))
      (node (ref "A08") (pin "F2") (pinfunction "S_F2") (pintype "input"))
      (node (ref "A08") (pin "K2") (pinfunction "R_K2") (pintype "input"))
      (node (ref "A09") (pin "U1") (pinfunction "P$1_U1") (pintype "passive"))
      (node (ref "B13") (pin "R1") (pinfunction "S_R1") (pintype "input"))
      (node (ref "B13") (pin "U2") (pinfunction "S_U2") (pintype "input"))
    )
    (net (code "2") (name "+3V@B12U1") (class "Default")
      (node (ref "B12") (pin "U1") (pinfunction "P$1_U1") (pintype "passive"))
      (node (ref "B13") (pin "D1") (pinfunction "S_D1") (pintype "input"))
      (node (ref "B13") (pin "F2") (pinfunction "S_F2") (pintype "input"))
      (node (ref "B13") (pin "K1") (pinfunction "S_K1") (pintype "input"))
      (node (ref "B14") (pin "A1") (pinfunction "R_A1") (pintype "input"))
      (node (ref "B14") (pin "K2") (pinfunction "R_K2") (pintype "input"))
      (node (ref "B14") (pin "N2") (pinfunction "S_N2") (pintype "input"))
      (node (ref "B14") (pin "R1") (pinfunction "S_R1") (pintype "input"))
      (node (ref "B14") (pin "U2") (pinfunction "S_U2") (pintype "input"))
    )
    (net (code "3") (name "+3V@C08U1") (class "Default")
      (node (ref "C01") (pin "C1") (pinfunction "IN2_C1") (pintype "input"))
      (node (ref "C02") (pin "C1") (pinfunction "ENABLE_C1") (pintype "input"))
      (node (ref "C04") (pin "J1") (pinfunction "IN2_J1") (pintype "input"))
      (node (ref "C04") (pin "L2") (pinfunction "L2_L2") (pintype "input"))
      (node (ref "C04") (pin "N2") (pinfunction "N2_N2") (pintype "input"))
      (node (ref "C04") (pin "U2") (pinfunction "U2_U2") (pintype "input"))
      (node (ref "C05") (pin "J1") (pinfunction "IN2_J1") (pintype "input"))
      (node (ref "C05") (pin "L2") (pinfunction "L2_L2") (pintype "input"))
      (node (ref "C05") (pin "N2") (pinfunction "N2_N2") (pintype "input"))
      (node (ref "C05") (pin "U2") (pinfunction "U2_U2") (pintype "input"))
      (node (ref "C08") (pin "U1") (pinfunction "P$1_U1") (pintype "passive"))
    )
    (net (code "4") (name "+3V@C15U1") (class "Default")
      (node (ref "C14") (pin "A1") (pinfunction "R_A1") (pintype "input"))
      (node (ref "C14") (pin "D1") (pinfunction "S_D1") (pintype "input"))
      (node (ref "C14") (pin "F2") (pinfunction "S_F2") (pintype "input"))
      (node (ref "C14") (pin "K1") (pinfunction "S_K1") (pintype "input"))
      (node (ref "C14") (pin "K2") (pinfunction "R_K2") (pintype "input"))
      (node (ref "C15") (pin "U1") (pinfunction "P$1_U1") (pintype "passive"))
      (node (ref "C16") (pin "H2") (pinfunction "IN4_H2") (pintype "input"))
    )
    (net (code "5") (name "+3V@D09U1") (class "Default")
      (node (ref "D07") (pin "S1") (pinfunction "EN2_S1") (pintype "input"))
      (node (ref "D07") (pin "S2") (pinfunction "EN1_S2") (pintype "input"))
      (node (ref "D07") (pin "T2") (pinfunction "EN3_T2") (pintype "input"))
      (node (ref "D09") (pin "U1") (pinfunction "P$1_U1") (pintype "passive"))
    )
    (net (code "6") (name "+3V@D10U1") (class "Default")
      (node (ref "D10") (pin "L2") (pinfunction "IN6_L2") (pintype "input"))
      (node (ref "D10") (pin "M2") (pinfunction "IN7_M2") (pintype "input"))
      (node (ref "D10") (pin "N2") (pinfunction "IN8_N2") (pintype "input"))
      (node (ref "D10") (pin "U1") (pinfunction "P$1_U1") (pintype "passive"))
      (node (ref "D11") (pin "D1") (pinfunction "S_D1") (pintype "input"))
      (node (ref "D11") (pin "F2") (pinfunction "S_F2") (pintype "input"))
      (node (ref "D11") (pin "K1") (pinfunction "S_K1") (pintype "input"))
      (node (ref "D11") (pin "K2") (pinfunction "R_K2") (pintype "input"))
      (node (ref "D14") (pin "M1") (pinfunction "M1_M1") (pintype "input"))
    )
    (net (code "7") (name "+11V") (class "Default")
      (node (ref "AB01") (pin "BM2") (pinfunction "+11V_BM2") (pintype "power_in"))
    )
    (net (code "8") (name "-15V") (class "Default")
      (node (ref "AB01") (pin "AB2") (pinfunction "-15V_AB2") (pintype "power_in"))
      (node (ref "AB01") (pin "AE2") (pinfunction "-15V_AE2") (pintype "power_in"))
      (node (ref "AB01") (pin "AF2") (pinfunction "-15V_AF2") (pintype "power_in"))
    )
    (net (code "9") (name "00") (class "Default")
      (node (ref "A07") (pin "D2") (pinfunction "O0_D2") (pintype "output"))
    )
    (net (code "10") (name "0_TO_DTB") (class "Default")
      (node (ref "A11") (pin "M1") (pinfunction "OUT_M1") (pintype "output"))
      (node (ref "C11") (pin "R1") (pinfunction "IN2_R1") (pintype "input"))
    )
    (net (code "11") (name "0_TO_EF") (class "Default")
      (node (ref "A10") (pin "K2") (pinfunction "OUT_K2") (pintype "output"))
      (node (ref "A11") (pin "E2") (pinfunction "IN_E2") (pintype "input"))
    )
    (net (code "12") (name "0_TO_STA") (class "Default")
      (node (ref "A10") (pin "N2") (pinfunction "OUT_N2") (pintype "output"))
      (node (ref "A11") (pin "N1") (pinfunction "IN_N1") (pintype "input"))
    )
    (net (code "13") (name "01") (class "Default")
      (node (ref "A07") (pin "E2") (pinfunction "O1_E2") (pintype "output"))
    )
    (net (code "14") (name "1_TO_DF") (class "Default")
      (node (ref "A08") (pin "H1") (pinfunction "C_H1") (pintype "input"))
      (node (ref "C12") (pin "J1") (pinfunction "OUT_J1") (pintype "output"))
      (node (ref "C12") (pin "L1") (pinfunction "IN2_L1") (pintype "input"))
      (node (ref "D11") (pin "L2") (pinfunction "C_L2") (pintype "input"))
    )
    (net (code "15") (name "1_TO_DTF") (class "Default")
      (node (ref "B12") (pin "P2") (pinfunction "OUT_P2") (pintype "output"))
      (node (ref "D11") (pin "S2") (pinfunction "C_S2") (pintype "input"))
    )
    (net (code "16") (name "02") (class "Default")
      (node (ref "A07") (pin "J2") (pinfunction "O2_J2") (pintype "output"))
    )
    (net (code "17") (name "03") (class "Default")
      (node (ref "A07") (pin "N2") (pinfunction "O3_N2") (pintype "output"))
    )
    (net (code "18") (name "04") (class "Default")
      (node (ref "A07") (pin "F2") (pinfunction "O4_F2") (pintype "output"))
    )
    (net (code "19") (name "05") (class "Default")
      (node (ref "A07") (pin "M2") (pinfunction "O5_M2") (pintype "output"))
    )
    (net (code "20") (name "06") (class "Default")
      (node (ref "A07") (pin "H2") (pinfunction "O6_H2") (pintype "output"))
    )
    (net (code "21") (name "07") (class "Default")
      (node (ref "A07") (pin "L2") (pinfunction "O7_L2") (pintype "output"))
    )
    (net (code "22") (name "76") (class "Default")
      (node (ref "C04") (pin "V2") (pinfunction "V2_V2") (pintype "output"))
      (node (ref "C06") (pin "S2") (pinfunction "IN_S2") (pintype "input"))
    )
    (net (code "23") (name "76+77") (class "Default")
      (node (ref "C03") (pin "C1") (pinfunction "ENABLE_C1") (pintype "input"))
      (node (ref "D12") (pin "V2") (pinfunction "OUT_V2") (pintype "output"))
    )
    (net (code "24") (name "77") (class "Default")
      (node (ref "C05") (pin "V2") (pinfunction "V2_V2") (pintype "output"))
      (node (ref "C06") (pin "U2") (pinfunction "IN_U2") (pintype "input"))
    )
    (net (code "25") (name "ADDR_ACC") (class "Default")
      (node (ref "C02") (pin "V2") (pinfunction "O15_V2") (pintype "output"))
      (node (ref "C17") (pin "N1") (pinfunction "IN_N1") (pintype "input"))
    )
    (net (code "26") (name "B-BRK") (class "Default")
      (node (ref "B10") (pin "R2") (pinfunction "IN1_R2") (pintype "input"))
      (node (ref "B10") (pin "S2") (pinfunction "IN2_S2") (pintype "input"))
      (node (ref "B10") (pin "T2") (pinfunction "IN3_T2") (pintype "input"))
      (node (ref "B10") (pin "U2") (pinfunction "IN4_U2") (pintype "input"))
      (node (ref "C01") (pin "E1") (pinfunction "OUT_E1") (pintype "output"))
      (node (ref "D12") (pin "M1") (pinfunction "IN1_M1") (pintype "input"))
    )
    (net (code "27") (name "B-RUN") (class "Default")
      (node (ref "B11") (pin "N2") (pinfunction "IN1_N2") (pintype "input"))
      (node (ref "C01") (pin "B1") (pinfunction "OUT_B1") (pintype "output"))
    )
    (net (code "28") (name "B-XSTA") (class "Default")
      (node (ref "A10") (pin "E2") (pinfunction "IN2_E2") (pintype "input"))
      (node (ref "C11") (pin "P2") (pinfunction "IN1_P2") (pintype "input"))
      (node (ref "D12") (pin "E1") (pinfunction "OUT_E1") (pintype "output"))
    )
    (net (code "29") (name "BAC_00") (class "Default")
      (node (ref "B06") (pin "B1") (pinfunction "OUT_B1") (pintype "output"))
      (node (ref "B07") (pin "C1") (pinfunction "C1_C1") (pintype "input"))
      (node (ref "B07") (pin "D1") (pinfunction "D1_D1") (pintype "input"))
    )
    (net (code "30") (name "BAC_01") (class "Default")
      (node (ref "B06") (pin "E1") (pinfunction "OUT_E1") (pintype "output"))
      (node (ref "B07") (pin "E2") (pinfunction "E2_E2") (pintype "input"))
      (node (ref "B07") (pin "F2") (pinfunction "F2_F2") (pintype "input"))
    )
    (net (code "31") (name "BAC_02") (class "Default")
      (node (ref "B06") (pin "H1") (pinfunction "OUT_H1") (pintype "output"))
      (node (ref "B07") (pin "J1") (pinfunction "J1_J1") (pintype "input"))
      (node (ref "B07") (pin "K1") (pinfunction "K1_K1") (pintype "input"))
    )
    (net (code "32") (name "BAC_03") (class "Default")
      (node (ref "B06") (pin "K1") (pinfunction "OUT_K1") (pintype "output"))
      (node (ref "B07") (pin "M2") (pinfunction "M2_M2") (pintype "input"))
      (node (ref "B07") (pin "N2") (pinfunction "N2_N2") (pintype "input"))
    )
    (net (code "33") (name "BAC_04") (class "Default")
      (node (ref "B06") (pin "M1") (pinfunction "OUT_M1") (pintype "output"))
      (node (ref "C07") (pin "M2") (pinfunction "M2_M2") (pintype "input"))
      (node (ref "C07") (pin "N2") (pinfunction "N2_N2") (pintype "input"))
    )
    (net (code "34") (name "BAC_05") (class "Default")
      (node (ref "B06") (pin "P1") (pinfunction "OUT_P1") (pintype "output"))
      (node (ref "B07") (pin "P1") (pinfunction "P1_P1") (pintype "input"))
      (node (ref "B07") (pin "R1") (pinfunction "R1_R1") (pintype "input"))
    )
    (net (code "35") (name "BAC_06") (class "Default")
      (node (ref "B06") (pin "S1") (pinfunction "OUT_S1") (pintype "output"))
      (node (ref "B07") (pin "T2") (pinfunction "T2_T2") (pintype "input"))
      (node (ref "B07") (pin "U2") (pinfunction "U2_U2") (pintype "input"))
      (node (ref "D11") (pin "C1") (pinfunction "D_C1") (pintype "input"))
    )
    (net (code "36") (name "BAC_07") (class "Default")
      (node (ref "B06") (pin "U1") (pinfunction "OUT_U1") (pintype "output"))
      (node (ref "C07") (pin "C1") (pinfunction "C1_C1") (pintype "input"))
      (node (ref "C07") (pin "D1") (pinfunction "D1_D1") (pintype "input"))
      (node (ref "D11") (pin "E2") (pinfunction "D_E2") (pintype "input"))
    )
    (net (code "37") (name "BAC_08") (class "Default")
      (node (ref "B06") (pin "D2") (pinfunction "OUT_D2") (pintype "output"))
      (node (ref "C07") (pin "E2") (pinfunction "E2_E2") (pintype "input"))
      (node (ref "C07") (pin "F2") (pinfunction "F2_F2") (pintype "input"))
      (node (ref "D11") (pin "J1") (pinfunction "D_J1") (pintype "input"))
    )
    (net (code "38") (name "BAC_09") (class "Default")
      (node (ref "B06") (pin "F2") (pinfunction "OUT_F2") (pintype "output"))
      (node (ref "C07") (pin "J1") (pinfunction "J1_J1") (pintype "input"))
      (node (ref "C07") (pin "K1") (pinfunction "K1_K1") (pintype "input"))
    )
    (net (code "39") (name "BAC_10") (class "Default")
      (node (ref "B06") (pin "J2") (pinfunction "OUT_J2") (pintype "output"))
    )
    (net (code "40") (name "BAC_11") (class "Default")
      (node (ref "B06") (pin "L2") (pinfunction "OUT_L2") (pintype "output"))
    )
    (net (code "41") (name "BLK_IN_SYNC") (class "Default")
      (node (ref "C11") (pin "E2") (pinfunction "IN2_E2") (pintype "input"))
      (node (ref "C13") (pin "S1") (pinfunction "OUT_S1") (pintype "output"))
      (node (ref "CD18") (pin "AP2") (pinfunction "AP2_AP2") (pintype "input"))
    )
    (net (code "42") (name "BMB_00") (class "Default")
      (node (ref "C06") (pin "B1") (pinfunction "OUT_B1") (pintype "output"))
      (node (ref "C08") (pin "B1") (pinfunction "IN1B_B1") (pintype "input"))
    )
    (net (code "43") (name "BMB_01") (class "Default")
      (node (ref "C06") (pin "E1") (pinfunction "OUT_E1") (pintype "output"))
      (node (ref "C08") (pin "H1") (pinfunction "IN1B_H1") (pintype "input"))
    )
    (net (code "44") (name "BMB_02") (class "Default")
      (node (ref "C06") (pin "H1") (pinfunction "OUT_H1") (pintype "output"))
      (node (ref "C08") (pin "N1") (pinfunction "IN1B_N1") (pintype "input"))
    )
    (net (code "45") (name "BMB_03") (class "Default")
      (node (ref "C06") (pin "K1") (pinfunction "OUT_K1") (pintype "output"))
      (node (ref "C08") (pin "E2") (pinfunction "IN1B_E2") (pintype "input"))
    )
    (net (code "46") (name "BMB_04") (class "Default")
      (node (ref "C06") (pin "M1") (pinfunction "OUT_M1") (pintype "output"))
      (node (ref "C08") (pin "L2") (pinfunction "IN1B_L2") (pintype "input"))
    )
    (net (code "47") (name "BMB_05") (class "Default")
      (node (ref "C06") (pin "P1") (pinfunction "OUT_P1") (pintype "output"))
      (node (ref "C08") (pin "S2") (pinfunction "IN1B_S2") (pintype "input"))
    )
    (net (code "48") (name "BMB_06") (class "Default")
      (node (ref "B08") (pin "B1") (pinfunction "IN2_B1") (pintype "input"))
      (node (ref "C06") (pin "S1") (pinfunction "OUT_S1") (pintype "output"))
    )
    (net (code "49") (name "BMB_07") (class "Default")
      (node (ref "B08") (pin "E1") (pinfunction "IN2_E1") (pintype "input"))
      (node (ref "C06") (pin "U1") (pinfunction "OUT_U1") (pintype "output"))
    )
    (net (code "50") (name "BMB_08") (class "Default")
      (node (ref "B08") (pin "E2") (pinfunction "IN2_E2") (pintype "input"))
      (node (ref "C06") (pin "D2") (pinfunction "OUT_D2") (pintype "output"))
    )
    (net (code "51") (name "BMB_09") (class "Default")
      (node (ref "B08") (pin "M1") (pinfunction "IN2_M1") (pintype "input"))
      (node (ref "C06") (pin "F2") (pinfunction "OUT_F2") (pintype "output"))
    )
    (net (code "52") (name "BMB_10") (class "Default")
      (node (ref "B08") (pin "R1") (pinfunction "IN2_R1") (pintype "input"))
      (node (ref "C06") (pin "J2") (pinfunction "OUT_J2") (pintype "output"))
    )
    (net (code "53") (name "BMB_11") (class "Default")
      (node (ref "B08") (pin "J1") (pinfunction "IN2_J1") (pintype "input"))
      (node (ref "C06") (pin "L2") (pinfunction "OUT_L2") (pintype "output"))
    )
    (net (code "54") (name "BMB_TO_DTB") (class "Default")
      (node (ref "B08") (pin "A1") (pinfunction "IN1_A1") (pintype "input"))
      (node (ref "B08") (pin "D1") (pinfunction "IN1_D1") (pintype "input"))
      (node (ref "B08") (pin "D2") (pinfunction "IN1_D2") (pintype "input"))
      (node (ref "B08") (pin "H1") (pinfunction "IN1_H1") (pintype "input"))
      (node (ref "B08") (pin "L1") (pinfunction "IN1_L1") (pintype "input"))
      (node (ref "B08") (pin "P1") (pinfunction "IN1_P1") (pintype "input"))
      (node (ref "C08") (pin "A1") (pinfunction "IN1A_A1") (pintype "input"))
      (node (ref "C08") (pin "D2") (pinfunction "IN1A_D2") (pintype "input"))
      (node (ref "C08") (pin "F1") (pinfunction "IN1A_F1") (pintype "input"))
      (node (ref "C08") (pin "K2") (pinfunction "IN1A_K2") (pintype "input"))
      (node (ref "C08") (pin "M1") (pinfunction "IN1A_M1") (pintype "input"))
      (node (ref "C08") (pin "R2") (pinfunction "IN1A_R2") (pintype "input"))
      (node (ref "D12") (pin "L1") (pinfunction "OUT_L1") (pintype "output"))
    )
    (net (code "55") (name "BMR00") (class "Default")
      (node (ref "A23") (pin "F1") (pinfunction "A_F1") (pintype "input"))
      (node (ref "B14") (pin "P2") (pinfunction "1_P2") (pintype "output"))
    )
    (net (code "56") (name "BMR01") (class "Default")
      (node (ref "A23") (pin "B1") (pinfunction "B_B1") (pintype "input"))
      (node (ref "B14") (pin "F1") (pinfunction "0_F1") (pintype "output"))
    )
    (net (code "57") (name "C00") (class "Default")
      (node (ref "A12") (pin "L2") (pinfunction "IN1_L2") (pintype "input"))
      (node (ref "A26") (pin "E2") (pinfunction "P$2_E2") (pintype "bidirectional"))
      (node (ref "B12") (pin "R2") (pinfunction "IN1_R2") (pintype "input"))
      (node (ref "B13") (pin "S1") (pinfunction "1_S1") (pintype "output"))
      (node (ref "C15") (pin "E2") (pinfunction "IN2_E2") (pintype "input"))
      (node (ref "D10") (pin "C1") (pinfunction "IN3_C1") (pintype "input"))
    )
    (net (code "58") (name "C01") (class "Default")
      (node (ref "A12") (pin "M2") (pinfunction "IN2_M2") (pintype "input"))
      (node (ref "A26") (pin "F2") (pinfunction "P$2_F2") (pintype "bidirectional"))
      (node (ref "B10") (pin "J1") (pinfunction "IN3_J1") (pintype "input"))
      (node (ref "B11") (pin "V2") (pinfunction "IN3_V2") (pintype "input"))
      (node (ref "B13") (pin "P2") (pinfunction "1_P2") (pintype "output"))
    )
    (net (code "59") (name "CK00") (class "Default")
      (node (ref "A18") (pin "P2") (pinfunction "P2_P2") (pintype "input"))
      (node (ref "B14") (pin "S1") (pinfunction "1_S1") (pintype "output"))
    )
    (net (code "60") (name "CK01") (class "Default")
      (node (ref "B14") (pin "P1") (pinfunction "D_P1") (pintype "input"))
      (node (ref "B14") (pin "V2") (pinfunction "1_V2") (pintype "output"))
      (node (ref "C16") (pin "N1") (pinfunction "IN2_N1") (pintype "input"))
      (node (ref "C16") (pin "P1") (pinfunction "IN3_P1") (pintype "input"))
      (node (ref "C16") (pin "R1") (pinfunction "IN4_R1") (pintype "input"))
    )
    (net (code "61") (name "COMP+SH") (class "Default")
      (node (ref "A12") (pin "D2") (pinfunction "IN1_D2") (pintype "input"))
      (node (ref "C14") (pin "B1") (pinfunction "C_B1") (pintype "input"))
      (node (ref "C14") (pin "D2") (pinfunction "C_D2") (pintype "input"))
      (node (ref "C14") (pin "H1") (pinfunction "C_H1") (pintype "input"))
      (node (ref "C15") (pin "K1") (pinfunction "OUT_K1") (pintype "output"))
    )
    (net (code "62") (name "CSTA") (class "Default")
      (node (ref "C04") (pin "C1") (pinfunction "C1_C1") (pintype "output"))
      (node (ref "D16") (pin "P2") (pinfunction "K2_P2") (pintype "input"))
    )
    (net (code "63") (name "DATA") (class "Default")
      (node (ref "A26") (pin "M1") (pinfunction "P$2_M1") (pintype "bidirectional"))
      (node (ref "C13") (pin "F1") (pinfunction "IN_F1") (pintype "input"))
      (node (ref "CD18") (pin "BK2") (pinfunction "BK2_BK2") (pintype "output"))
    )
    (net (code "64") (name "DF") (class "Default")
      (node (ref "A10") (pin "P2") (pinfunction "IN1_P2") (pintype "input"))
      (node (ref "A26") (pin "E1") (pinfunction "P$2_E1") (pintype "bidirectional"))
      (node (ref "D11") (pin "R2") (pinfunction "0_R2") (pintype "output"))
    )
    (net (code "65") (name "DTB_00") (class "Default")
      (node (ref "A25") (pin "A2") (pinfunction "P$2_A2") (pintype "bidirectional"))
      (node (ref "C09") (pin "E1") (pinfunction "1_E1") (pintype "output"))
      (node (ref "C10") (pin "B1") (pinfunction "IN1B_B1") (pintype "input"))
      (node (ref "D09") (pin "D2") (pinfunction "IN1A_D2") (pintype "input"))
    )
    (net (code "66") (name "DTB_01") (class "Default")
      (node (ref "A25") (pin "B2") (pinfunction "P$2_B2") (pintype "bidirectional"))
      (node (ref "C09") (pin "H2") (pinfunction "1_H2") (pintype "output"))
      (node (ref "C10") (pin "H1") (pinfunction "IN1B_H1") (pintype "input"))
      (node (ref "D09") (pin "K2") (pinfunction "IN1A_K2") (pintype "input"))
    )
    (net (code "67") (name "DTB_02") (class "Default")
      (node (ref "A25") (pin "C2") (pinfunction "P$2_C2") (pintype "bidirectional"))
      (node (ref "C09") (pin "L1") (pinfunction "1_L1") (pintype "output"))
      (node (ref "C10") (pin "N1") (pinfunction "IN1B_N1") (pintype "input"))
      (node (ref "D09") (pin "R2") (pinfunction "IN1A_R2") (pintype "input"))
    )
    (net (code "68") (name "DTB_03") (class "Default")
      (node (ref "A25") (pin "D2") (pinfunction "P$2_D2") (pintype "bidirectional"))
      (node (ref "C09") (pin "C1") (pinfunction "D_C1") (pintype "input"))
      (node (ref "C09") (pin "P2") (pinfunction "1_P2") (pintype "output"))
    )
    (net (code "69") (name "DTB_04") (class "Default")
      (node (ref "A25") (pin "E2") (pinfunction "P$2_E2") (pintype "bidirectional"))
      (node (ref "C09") (pin "E2") (pinfunction "D_E2") (pintype "input"))
      (node (ref "C09") (pin "S1") (pinfunction "1_S1") (pintype "output"))
    )
    (net (code "70") (name "DTB_05") (class "Default")
      (node (ref "A25") (pin "F2") (pinfunction "P$2_F2") (pintype "bidirectional"))
      (node (ref "C09") (pin "J1") (pinfunction "D_J1") (pintype "input"))
      (node (ref "C09") (pin "V2") (pinfunction "1_V2") (pintype "output"))
    )
    (net (code "71") (name "DTB_06") (class "Default")
      (node (ref "A25") (pin "H2") (pinfunction "P$2_H2") (pintype "bidirectional"))
      (node (ref "B09") (pin "E1") (pinfunction "1_E1") (pintype "output"))
      (node (ref "C09") (pin "M2") (pinfunction "D_M2") (pintype "input"))
    )
    (net (code "72") (name "DTB_07") (class "Default")
      (node (ref "A25") (pin "J2") (pinfunction "P$2_J2") (pintype "bidirectional"))
      (node (ref "B09") (pin "V2") (pinfunction "1_V2") (pintype "output"))
      (node (ref "C09") (pin "P1") (pinfunction "D_P1") (pintype "input"))
    )
    (net (code "73") (name "DTB_08") (class "Default")
      (node (ref "A25") (pin "K2") (pinfunction "P$2_K2") (pintype "bidirectional"))
      (node (ref "B09") (pin "L1") (pinfunction "1_L1") (pintype "output"))
      (node (ref "C09") (pin "T2") (pinfunction "D_T2") (pintype "input"))
    )
    (net (code "74") (name "DTB_09") (class "Default")
      (node (ref "A25") (pin "L2") (pinfunction "P$2_L2") (pintype "bidirectional"))
      (node (ref "B09") (pin "C1") (pinfunction "D_C1") (pintype "input"))
      (node (ref "B09") (pin "P2") (pinfunction "1_P2") (pintype "output"))
    )
    (net (code "75") (name "DTB_10") (class "Default")
      (node (ref "A25") (pin "M2") (pinfunction "P$2_M2") (pintype "bidirectional"))
      (node (ref "B09") (pin "S1") (pinfunction "1_S1") (pintype "output"))
      (node (ref "B09") (pin "T2") (pinfunction "D_T2") (pintype "input"))
    )
    (net (code "76") (name "DTB_11") (class "Default")
      (node (ref "A25") (pin "N2") (pinfunction "P$2_N2") (pintype "bidirectional"))
      (node (ref "B09") (pin "H2") (pinfunction "1_H2") (pintype "output"))
      (node (ref "B09") (pin "J1") (pinfunction "D_J1") (pintype "input"))
    )
    (net (code "77") (name "DTF") (class "Default")
      (node (ref "A08") (pin "J1") (pinfunction "D_J1") (pintype "input"))
      (node (ref "A12") (pin "M1") (pinfunction "IN2_M1") (pintype "input"))
      (node (ref "A26") (pin "C1") (pinfunction "P$2_C1") (pintype "bidirectional"))
      (node (ref "D11") (pin "V1") (pinfunction "0_V1") (pintype "output"))
    )
    (net (code "78") (name "DTSF") (class "Default")
      (node (ref "A12") (pin "R1") (pinfunction "IN2_R1") (pintype "input"))
      (node (ref "C05") (pin "A1") (pinfunction "A1_A1") (pintype "output"))
    )
    (net (code "79") (name "EF") (class "Default")
      (node (ref "A11") (pin "J1") (pinfunction "IN_J1") (pintype "input"))
      (node (ref "A12") (pin "F1") (pinfunction "OUT_F1") (pintype "output"))
      (node (ref "A12") (pin "L1") (pinfunction "IN1_L1") (pintype "input"))
      (node (ref "A25") (pin "N1") (pinfunction "P$2_N1") (pintype "bidirectional"))
    )
    (net (code "80") (name "END") (class "Default")
      (node (ref "A08") (pin "E1") (pinfunction "1_E1") (pintype "output"))
      (node (ref "A25") (pin "R1") (pinfunction "P$2_R1") (pintype "bidirectional"))
    )
    (net (code "81") (name "ENI") (class "Default")
      (node (ref "A12") (pin "H1") (pinfunction "IN1_H1") (pintype "input"))
      (node (ref "A25") (pin "L1") (pinfunction "P$2_L1") (pintype "bidirectional"))
      (node (ref "C07") (pin "L1") (pinfunction "L1_L1") (pintype "output"))
    )
    (net (code "82") (name "FR_00") (class "Default")
      (node (ref "A25") (pin "F1") (pinfunction "P$2_F1") (pintype "bidirectional"))
      (node (ref "B07") (pin "S1") (pinfunction "S1_S1") (pintype "output"))
      (node (ref "B12") (pin "E2") (pinfunction "IN2_E2") (pintype "input"))
      (node (ref "C12") (pin "U2") (pinfunction "IN2_U2") (pintype "input"))
    )
    (net (code "83") (name "FR_01") (class "Default")
      (node (ref "A10") (pin "H1") (pinfunction "IN1_H1") (pintype "input"))
      (node (ref "A25") (pin "H1") (pinfunction "P$2_H1") (pintype "bidirectional"))
      (node (ref "B07") (pin "V2") (pinfunction "V2_V2") (pintype "output"))
      (node (ref "B15") (pin "M1") (pinfunction "IN2_M1") (pintype "input"))
      (node (ref "C15") (pin "D1") (pinfunction "IN1_D1") (pintype "input"))
      (node (ref "D07") (pin "V2") (pinfunction "IN2_V2") (pintype "input"))
      (node (ref "D12") (pin "R1") (pinfunction "IN4_R1") (pintype "input"))
    )
    (net (code "84") (name "FR_02") (class "Default")
      (node (ref "A25") (pin "J1") (pinfunction "P$2_J1") (pintype "bidirectional"))
      (node (ref "C07") (pin "E1") (pinfunction "E1_E1") (pintype "output"))
      (node (ref "D07") (pin "U2") (pinfunction "IN1_U2") (pintype "input"))
    )
    (net (code "85") (name "FR_03") (class "Default")
      (node (ref "A25") (pin "K1") (pinfunction "P$2_K1") (pintype "bidirectional"))
      (node (ref "B15") (pin "R2") (pinfunction "IN2_R2") (pintype "input"))
      (node (ref "C07") (pin "H2") (pinfunction "H2_H2") (pintype "output"))
      (node (ref "D07") (pin "V1") (pinfunction "IN0_V1") (pintype "input"))
    )
    (net (code "86") (name "GND") (class "Default")
      (node (ref "A05") (pin "B1") (pinfunction "P$2_B1") (pintype "bidirectional"))
      (node (ref "A05") (pin "D1") (pinfunction "P$2_D1") (pintype "bidirectional"))
      (node (ref "A05") (pin "D2") (pinfunction "P$2_D2") (pintype "bidirectional"))
      (node (ref "A05") (pin "E1") (pinfunction "P$2_E1") (pintype "bidirectional"))
      (node (ref "A05") (pin "H1") (pinfunction "P$2_H1") (pintype "bidirectional"))
      (node (ref "A05") (pin "J1") (pinfunction "P$2_J1") (pintype "bidirectional"))
      (node (ref "A05") (pin "L1") (pinfunction "P$2_L1") (pintype "bidirectional"))
      (node (ref "A05") (pin "M1") (pinfunction "P$2_M1") (pintype "bidirectional"))
      (node (ref "A05") (pin "P1") (pinfunction "P$2_P1") (pintype "bidirectional"))
      (node (ref "A05") (pin "S1") (pinfunction "P$2_S1") (pintype "bidirectional"))
      (node (ref "A06") (pin "K2") (pinfunction "P$2_K2") (pintype "bidirectional"))
      (node (ref "A07") (pin "U1") (pinfunction "IN*_U1") (pintype "input"))
      (node (ref "A08") (pin "T2") (pinfunction "D_T2") (pintype "input"))
      (node (ref "A23") (pin "C1") (pinfunction "C_C1") (pintype "input"))
      (node (ref "A23") (pin "F2") (pinfunction "C_F2") (pintype "input"))
      (node (ref "A23") (pin "J1") (pinfunction "C_J1") (pintype "input"))
      (node (ref "A23") (pin "M2") (pinfunction "C_M2") (pintype "input"))
      (node (ref "A23") (pin "P1") (pinfunction "C_P1") (pintype "input"))
      (node (ref "A23") (pin "T2") (pinfunction "C_T2") (pintype "input"))
      (node (ref "A25") (pin "M1") (pinfunction "P$2_M1") (pintype "bidirectional"))
      (node (ref "A26") (pin "D2") (pinfunction "P$2_D2") (pintype "bidirectional"))
      (node (ref "A26") (pin "U2") (pinfunction "P$2_U2") (pintype "bidirectional"))
      (node (ref "A26") (pin "V1") (pinfunction "P$2_V1") (pintype "bidirectional"))
      (node (ref "AB01") (pin "AC2") (pinfunction "GND_AC2") (pintype "power_in"))
      (node (ref "AB01") (pin "AH2") (pinfunction "GND_AH2") (pintype "power_in"))
      (node (ref "AB01") (pin "AK2") (pinfunction "GND_AK2") (pintype "power_in"))
      (node (ref "AB01") (pin "AL2") (pinfunction "GND_AL2") (pintype "power_in"))
      (node (ref "AB01") (pin "AT1") (pinfunction "GND_AT1") (pintype "power_in"))
      (node (ref "AB01") (pin "BC2") (pinfunction "GND_BC2") (pintype "power_in"))
      (node (ref "AB01") (pin "BD2") (pinfunction "GND_BD2") (pintype "power_in"))
      (node (ref "AB01") (pin "BH2") (pinfunction "GND_BH2") (pintype "power_in"))
      (node (ref "AB01") (pin "BK2") (pinfunction "GND_BK2") (pintype "power_in"))
      (node (ref "AB01") (pin "BL2") (pinfunction "GND_BL2") (pintype "power_in"))
      (node (ref "AB01") (pin "BT1") (pinfunction "GND_BT1") (pintype "power_in"))
      (node (ref "AB19") (pin "AJ2") (pinfunction "P$2_AJ2") (pintype "bidirectional"))
      (node (ref "AB19") (pin "AR2") (pinfunction "P$2_AR2") (pintype "bidirectional"))
      (node (ref "AB19") (pin "AU2") (pinfunction "P$2_AU2") (pintype "bidirectional"))
      (node (ref "AB19") (pin "BF2") (pinfunction "P$2_BF2") (pintype "bidirectional"))
      (node (ref "AB19") (pin "BM2") (pinfunction "P$2_BM2") (pintype "bidirectional"))
      (node (ref "B05") (pin "C1") (pinfunction "C_C1") (pintype "input"))
      (node (ref "B05") (pin "F2") (pinfunction "C_F2") (pintype "input"))
      (node (ref "B05") (pin "J1") (pinfunction "C_J1") (pintype "input"))
      (node (ref "B05") (pin "M2") (pinfunction "C_M2") (pintype "input"))
      (node (ref "B05") (pin "P1") (pinfunction "C_P1") (pintype "input"))
      (node (ref "B22") (pin "T2") (pinfunction "C_T2") (pintype "input"))
      (node (ref "D05") (pin "B1") (pinfunction "P$2_B1") (pintype "bidirectional"))
      (node (ref "D05") (pin "D1") (pinfunction "P$2_D1") (pintype "bidirectional"))
      (node (ref "D05") (pin "D2") (pinfunction "P$2_D2") (pintype "bidirectional"))
      (node (ref "D05") (pin "E1") (pinfunction "P$2_E1") (pintype "bidirectional"))
      (node (ref "D05") (pin "H1") (pinfunction "P$2_H1") (pintype "bidirectional"))
      (node (ref "D05") (pin "J1") (pinfunction "P$2_J1") (pintype "bidirectional"))
      (node (ref "D05") (pin "L1") (pinfunction "P$2_L1") (pintype "bidirectional"))
      (node (ref "D05") (pin "M1") (pinfunction "P$2_M1") (pintype "bidirectional"))
      (node (ref "D05") (pin "P1") (pinfunction "P$2_P1") (pintype "bidirectional"))
      (node (ref "D05") (pin "S1") (pinfunction "P$2_S1") (pintype "bidirectional"))
      (node (ref "D06") (pin "K2") (pinfunction "P$2_K2") (pintype "bidirectional"))
      (node (ref "D07") (pin "U1") (pinfunction "IN*_U1") (pintype "input"))
      (node (ref "D11") (pin "P1") (pinfunction "D_P1") (pintype "input"))
      (node (ref "D11") (pin "T2") (pinfunction "D_T2") (pintype "input"))
    )
    (net (code "87") (name "IOP_1") (class "Default")
      (node (ref "A02") (pin "K2") (pinfunction "P$2_K2") (pintype "bidirectional"))
      (node (ref "C04") (pin "P2") (pinfunction "P2_P2") (pintype "input"))
      (node (ref "C05") (pin "P2") (pinfunction "P2_P2") (pintype "input"))
      (node (ref "D02") (pin "K2") (pinfunction "P$2_K2") (pintype "bidirectional"))
    )
    (net (code "88") (name "IOP_2") (class "Default")
      (node (ref "A02") (pin "M2") (pinfunction "P$2_M2") (pintype "bidirectional"))
      (node (ref "C04") (pin "R2") (pinfunction "R2_R2") (pintype "input"))
      (node (ref "C05") (pin "R2") (pinfunction "R2_R2") (pintype "input"))
      (node (ref "D02") (pin "M2") (pinfunction "P$2_M2") (pintype "bidirectional"))
    )
    (net (code "89") (name "IOP_4") (class "Default")
      (node (ref "A02") (pin "P2") (pinfunction "P$2_P2") (pintype "bidirectional"))
      (node (ref "C04") (pin "S2") (pinfunction "S2_S2") (pintype "input"))
      (node (ref "C05") (pin "S2") (pinfunction "S2_S2") (pintype "input"))
      (node (ref "D02") (pin "P2") (pinfunction "P$2_P2") (pintype "bidirectional"))
    )
    (net (code "90") (name "I{slash}O_B-BRK") (class "Default")
      (node (ref "A05") (pin "P2") (pinfunction "P$2_P2") (pintype "bidirectional"))
      (node (ref "C01") (pin "D1") (pinfunction "IN_D1") (pintype "input"))
      (node (ref "D05") (pin "P2") (pinfunction "P$2_P2") (pintype "bidirectional"))
    )
    (net (code "91") (name "I{slash}O_B-RUN") (class "Default")
      (node (ref "A04") (pin "S2") (pinfunction "P$2_S2") (pintype "bidirectional"))
      (node (ref "C01") (pin "A1") (pinfunction "IN1_A1") (pintype "input"))
      (node (ref "D04") (pin "S2") (pinfunction "P$2_S2") (pintype "bidirectional"))
    )
    (net (code "92") (name "I{slash}O_BAC_00") (class "Default")
      (node (ref "A02") (pin "B1") (pinfunction "P$2_B1") (pintype "bidirectional"))
      (node (ref "C03") (pin "A1") (pinfunction "IN1_A1") (pintype "input"))
      (node (ref "D02") (pin "B1") (pinfunction "P$2_B1") (pintype "bidirectional"))
    )
    (net (code "93") (name "I{slash}O_BAC_01") (class "Default")
      (node (ref "A02") (pin "D1") (pinfunction "P$2_D1") (pintype "bidirectional"))
      (node (ref "C03") (pin "D1") (pinfunction "IN2_D1") (pintype "input"))
      (node (ref "D02") (pin "D1") (pinfunction "P$2_D1") (pintype "bidirectional"))
    )
    (net (code "94") (name "I{slash}O_BAC_02") (class "Default")
      (node (ref "A02") (pin "E1") (pinfunction "P$2_E1") (pintype "bidirectional"))
      (node (ref "C03") (pin "F1") (pinfunction "IN3_F1") (pintype "input"))
      (node (ref "D02") (pin "E1") (pinfunction "P$2_E1") (pintype "bidirectional"))
    )
    (net (code "95") (name "I{slash}O_BAC_03") (class "Default")
      (node (ref "A02") (pin "H1") (pinfunction "P$2_H1") (pintype "bidirectional"))
      (node (ref "C03") (pin "J1") (pinfunction "IN4_J1") (pintype "input"))
      (node (ref "D02") (pin "H1") (pinfunction "P$2_H1") (pintype "bidirectional"))
    )
    (net (code "96") (name "I{slash}O_BAC_04") (class "Default")
      (node (ref "A02") (pin "J1") (pinfunction "P$2_J1") (pintype "bidirectional"))
      (node (ref "C03") (pin "L1") (pinfunction "IN5_L1") (pintype "input"))
      (node (ref "D02") (pin "J1") (pinfunction "P$2_J1") (pintype "bidirectional"))
    )
    (net (code "97") (name "I{slash}O_BAC_05") (class "Default")
      (node (ref "A02") (pin "L1") (pinfunction "P$2_L1") (pintype "bidirectional"))
      (node (ref "C03") (pin "N1") (pinfunction "IN6_N1") (pintype "input"))
      (node (ref "D02") (pin "L1") (pinfunction "P$2_L1") (pintype "bidirectional"))
    )
    (net (code "98") (name "I{slash}O_BAC_06") (class "Default")
      (node (ref "A02") (pin "M1") (pinfunction "P$2_M1") (pintype "bidirectional"))
      (node (ref "C03") (pin "R1") (pinfunction "IN7_R1") (pintype "input"))
      (node (ref "D02") (pin "M1") (pinfunction "P$2_M1") (pintype "bidirectional"))
    )
    (net (code "99") (name "I{slash}O_BAC_07") (class "Default")
      (node (ref "A02") (pin "P1") (pinfunction "P$2_P1") (pintype "bidirectional"))
      (node (ref "C03") (pin "V1") (pinfunction "IN8_V1") (pintype "input"))
      (node (ref "D02") (pin "P1") (pinfunction "P$2_P1") (pintype "bidirectional"))
    )
    (net (code "100") (name "I{slash}O_BAC_08") (class "Default")
      (node (ref "A02") (pin "S1") (pinfunction "P$2_S1") (pintype "bidirectional"))
      (node (ref "C03") (pin "E2") (pinfunction "IN9_E2") (pintype "input"))
      (node (ref "D02") (pin "S1") (pinfunction "P$2_S1") (pintype "bidirectional"))
    )
    (net (code "101") (name "I{slash}O_BAC_09") (class "Default")
      (node (ref "A02") (pin "D2") (pinfunction "P$2_D2") (pintype "bidirectional"))
      (node (ref "C03") (pin "H2") (pinfunction "IN10_H2") (pintype "input"))
      (node (ref "D02") (pin "D2") (pinfunction "P$2_D2") (pintype "bidirectional"))
    )
    (net (code "102") (name "I{slash}O_BAC_10") (class "Default")
      (node (ref "A02") (pin "E2") (pinfunction "P$2_E2") (pintype "bidirectional"))
      (node (ref "C03") (pin "K2") (pinfunction "IN11_K2") (pintype "input"))
      (node (ref "D02") (pin "E2") (pinfunction "P$2_E2") (pintype "bidirectional"))
    )
    (net (code "103") (name "I{slash}O_BAC_11") (class "Default")
      (node (ref "A02") (pin "H2") (pinfunction "P$2_H2") (pintype "bidirectional"))
      (node (ref "C03") (pin "M2") (pinfunction "IN12_M2") (pintype "input"))
      (node (ref "D02") (pin "H2") (pinfunction "P$2_H2") (pintype "bidirectional"))
    )
    (net (code "104") (name "I{slash}O_BMB_00") (class "Default")
      (node (ref "A03") (pin "B1") (pinfunction "P$2_B1") (pintype "bidirectional"))
      (node (ref "C02") (pin "A1") (pinfunction "IN1_A1") (pintype "input"))
      (node (ref "D03") (pin "B1") (pinfunction "P$2_B1") (pintype "bidirectional"))
    )
    (net (code "105") (name "I{slash}O_BMB_01") (class "Default")
      (node (ref "A03") (pin "D1") (pinfunction "P$2_D1") (pintype "bidirectional"))
      (node (ref "C02") (pin "D1") (pinfunction "IN2_D1") (pintype "input"))
      (node (ref "D03") (pin "D1") (pinfunction "P$2_D1") (pintype "bidirectional"))
    )
    (net (code "106") (name "I{slash}O_BMB_02") (class "Default")
      (node (ref "A03") (pin "E1") (pinfunction "P$2_E1") (pintype "bidirectional"))
      (node (ref "C02") (pin "F1") (pinfunction "IN3_F1") (pintype "input"))
      (node (ref "D03") (pin "E1") (pinfunction "P$2_E1") (pintype "bidirectional"))
    )
    (net (code "107") (name "I{slash}O_BMB_03") (class "Default")
      (node (ref "A03") (pin "J1") (pinfunction "P$2_J1") (pintype "bidirectional"))
      (node (ref "C02") (pin "J1") (pinfunction "IN4_J1") (pintype "input"))
      (node (ref "C04") (pin "D2") (pinfunction "D2_D2") (pintype "input"))
      (node (ref "C05") (pin "D2") (pinfunction "D2_D2") (pintype "input"))
      (node (ref "D03") (pin "J1") (pinfunction "P$2_J1") (pintype "bidirectional"))
    )
    (net (code "108") (name "I{slash}O_BMB_04") (class "Default")
      (node (ref "A03") (pin "M1") (pinfunction "P$2_M1") (pintype "bidirectional"))
      (node (ref "C02") (pin "L1") (pinfunction "IN5_L1") (pintype "input"))
      (node (ref "C04") (pin "E2") (pinfunction "E2_E2") (pintype "input"))
      (node (ref "C05") (pin "E2") (pinfunction "E2_E2") (pintype "input"))
      (node (ref "D03") (pin "M1") (pinfunction "P$2_M1") (pintype "bidirectional"))
    )
    (net (code "109") (name "I{slash}O_BMB_05") (class "Default")
      (node (ref "A03") (pin "S1") (pinfunction "P$2_S1") (pintype "bidirectional"))
      (node (ref "C02") (pin "N1") (pinfunction "IN6_N1") (pintype "input"))
      (node (ref "C04") (pin "F2") (pinfunction "F2_F2") (pintype "input"))
      (node (ref "C05") (pin "F2") (pinfunction "F2_F2") (pintype "input"))
      (node (ref "D03") (pin "S1") (pinfunction "P$2_S1") (pintype "bidirectional"))
    )
    (net (code "110") (name "I{slash}O_BMB_06") (class "Default")
      (node (ref "A03") (pin "E2") (pinfunction "P$2_E2") (pintype "bidirectional"))
      (node (ref "C02") (pin "R1") (pinfunction "IN7_R1") (pintype "input"))
      (node (ref "C04") (pin "H2") (pinfunction "H2_H2") (pintype "input"))
      (node (ref "C05") (pin "H2") (pinfunction "H2_H2") (pintype "input"))
      (node (ref "D03") (pin "E2") (pinfunction "P$2_E2") (pintype "bidirectional"))
    )
    (net (code "111") (name "I{slash}O_BMB_07") (class "Default")
      (node (ref "A03") (pin "K2") (pinfunction "P$2_K2") (pintype "bidirectional"))
      (node (ref "C02") (pin "V1") (pinfunction "IN8_V1") (pintype "input"))
      (node (ref "C04") (pin "J2") (pinfunction "J2_J2") (pintype "input"))
      (node (ref "C05") (pin "J2") (pinfunction "J2_J2") (pintype "input"))
      (node (ref "D03") (pin "K2") (pinfunction "P$2_K2") (pintype "bidirectional"))
    )
    (net (code "112") (name "I{slash}O_BMB_08") (class "Default")
      (node (ref "A03") (pin "P2") (pinfunction "P$2_P2") (pintype "bidirectional"))
      (node (ref "C02") (pin "E2") (pinfunction "IN9_E2") (pintype "input"))
      (node (ref "C05") (pin "K2") (pinfunction "K2_K2") (pintype "input"))
      (node (ref "D03") (pin "P2") (pinfunction "P$2_P2") (pintype "bidirectional"))
    )
    (net (code "113") (name "I{slash}O_BMB_09") (class "Default")
      (node (ref "A03") (pin "S2") (pinfunction "P$2_S2") (pintype "bidirectional"))
      (node (ref "C02") (pin "H2") (pinfunction "IN10_H2") (pintype "input"))
      (node (ref "D03") (pin "S2") (pinfunction "P$2_S2") (pintype "bidirectional"))
    )
    (net (code "114") (name "I{slash}O_BMB_10") (class "Default")
      (node (ref "A03") (pin "T2") (pinfunction "P$2_T2") (pintype "bidirectional"))
      (node (ref "C02") (pin "K2") (pinfunction "IN11_K2") (pintype "input"))
      (node (ref "D03") (pin "T2") (pinfunction "P$2_T2") (pintype "bidirectional"))
    )
    (net (code "115") (name "I{slash}O_BMB_11") (class "Default")
      (node (ref "A03") (pin "V2") (pinfunction "P$2_V2") (pintype "bidirectional"))
      (node (ref "C02") (pin "M2") (pinfunction "IN12_M2") (pintype "input"))
      (node (ref "D03") (pin "V2") (pinfunction "P$2_V2") (pintype "bidirectional"))
    )
    (net (code "116") (name "I{slash}O_DATA_IN") (class "Default")
      (node (ref "A05") (pin "M2") (pinfunction "P$2_M2") (pintype "bidirectional"))
      (node (ref "B05") (pin "J2") (pinfunction "E_J2") (pintype "open_collector"))
      (node (ref "D05") (pin "M2") (pinfunction "P$2_M2") (pintype "bidirectional"))
    )
    (net (code "117") (name "I{slash}O_PWR_CLR") (class "Default")
      (node (ref "A02") (pin "V2") (pinfunction "P$2_V2") (pintype "bidirectional"))
      (node (ref "C05") (pin "H1") (pinfunction "IN1_H1") (pintype "input"))
      (node (ref "D02") (pin "V2") (pinfunction "P$2_V2") (pintype "bidirectional"))
    )
    (net (code "118") (name "I{slash}O_TS03") (class "Default")
      (node (ref "A02") (pin "S2") (pinfunction "P$2_S2") (pintype "bidirectional"))
      (node (ref "C04") (pin "H1") (pinfunction "IN1_H1") (pintype "input"))
      (node (ref "D02") (pin "S2") (pinfunction "P$2_S2") (pintype "bidirectional"))
    )
    (net (code "119") (name "I{slash}O_TS04") (class "Default")
      (node (ref "A02") (pin "T2") (pinfunction "P$2_T2") (pintype "bidirectional"))
      (node (ref "D02") (pin "T2") (pinfunction "P$2_T2") (pintype "bidirectional"))
    )
    (net (code "120") (name "I{slash}~{O_0_TO_AC}") (class "Default")
      (node (ref "A04") (pin "P2") (pinfunction "P$2_P2") (pintype "bidirectional"))
      (node (ref "B05") (pin "L1") (pinfunction "E_L1") (pintype "open_collector"))
      (node (ref "D04") (pin "P2") (pinfunction "P$2_P2") (pintype "bidirectional"))
    )
    (net (code "121") (name "I{slash}~{O_1_TO_CA_INH}") (class "Default")
      (node (ref "A06") (pin "M2") (pinfunction "P$2_M2") (pintype "bidirectional"))
      (node (ref "B05") (pin "N2") (pinfunction "D_N2") (pintype "open_collector"))
      (node (ref "D06") (pin "M2") (pinfunction "P$2_M2") (pintype "bidirectional"))
    )
    (net (code "122") (name "I{slash}~{O_ADDR_ACC}") (class "Default")
      (node (ref "A05") (pin "S2") (pinfunction "P$2_S2") (pintype "bidirectional"))
      (node (ref "C02") (pin "U2") (pinfunction "IN15_U2") (pintype "input"))
      (node (ref "D05") (pin "S2") (pinfunction "P$2_S2") (pintype "bidirectional"))
    )
    (net (code "123") (name "I{slash}~{O_BMB_03}") (class "Default")
      (node (ref "A03") (pin "H1") (pinfunction "P$2_H1") (pintype "bidirectional"))
      (node (ref "D03") (pin "H1") (pinfunction "P$2_H1") (pintype "bidirectional"))
    )
    (net (code "124") (name "I{slash}~{O_BMB_04}") (class "Default")
      (node (ref "A03") (pin "L1") (pinfunction "P$2_L1") (pintype "bidirectional"))
      (node (ref "D03") (pin "L1") (pinfunction "P$2_L1") (pintype "bidirectional"))
    )
    (net (code "125") (name "I{slash}~{O_BMB_05}") (class "Default")
      (node (ref "A03") (pin "P1") (pinfunction "P$2_P1") (pintype "bidirectional"))
      (node (ref "D03") (pin "P1") (pinfunction "P$2_P1") (pintype "bidirectional"))
    )
    (net (code "126") (name "I{slash}~{O_BMB_06}") (class "Default")
      (node (ref "A03") (pin "D2") (pinfunction "P$2_D2") (pintype "bidirectional"))
      (node (ref "D03") (pin "D2") (pinfunction "P$2_D2") (pintype "bidirectional"))
    )
    (net (code "127") (name "I{slash}~{O_BMB_07}") (class "Default")
      (node (ref "A03") (pin "H2") (pinfunction "P$2_H2") (pintype "bidirectional"))
      (node (ref "D03") (pin "H2") (pinfunction "P$2_H2") (pintype "bidirectional"))
    )
    (net (code "128") (name "I{slash}~{O_BMB_08}") (class "Default")
      (node (ref "A03") (pin "M2") (pinfunction "P$2_M2") (pintype "bidirectional"))
      (node (ref "C04") (pin "K2") (pinfunction "K2_K2") (pintype "input"))
      (node (ref "D03") (pin "M2") (pinfunction "P$2_M2") (pintype "bidirectional"))
    )
    (net (code "129") (name "I{slash}~{O_BRK_RQ}") (class "Default")
      (node (ref "A05") (pin "K2") (pinfunction "P$2_K2") (pintype "bidirectional"))
      (node (ref "B05") (pin "D1") (pinfunction "D_D1") (pintype "open_collector"))
      (node (ref "D05") (pin "K2") (pinfunction "P$2_K2") (pintype "bidirectional"))
    )
    (net (code "130") (name "I{slash}~{O_BWC0}") (class "Default")
      (node (ref "A06") (pin "P2") (pinfunction "P$2_P2") (pintype "bidirectional"))
      (node (ref "C01") (pin "F1") (pinfunction "IN_F1") (pintype "input"))
      (node (ref "D06") (pin "P2") (pinfunction "P$2_P2") (pintype "bidirectional"))
    )
    (net (code "131") (name "I{slash}~{O_INT_RQ}") (class "Default")
      (node (ref "A04") (pin "M2") (pinfunction "P$2_M2") (pintype "bidirectional"))
      (node (ref "B05") (pin "E1") (pinfunction "E_E1") (pintype "open_collector"))
      (node (ref "D04") (pin "M2") (pinfunction "P$2_M2") (pintype "bidirectional"))
    )
    (net (code "132") (name "I{slash}~{O_SKP_RQ}") (class "Default")
      (node (ref "A04") (pin "K2") (pinfunction "P$2_K2") (pintype "bidirectional"))
      (node (ref "B05") (pin "K1") (pinfunction "D_K1") (pintype "open_collector"))
      (node (ref "D04") (pin "K2") (pinfunction "P$2_K2") (pintype "bidirectional"))
    )
    (net (code "133") (name "LDMF") (class "Default")
      (node (ref "C05") (pin "E1") (pinfunction "E1_E1") (pintype "output"))
      (node (ref "D11") (pin "B1") (pinfunction "C_B1") (pintype "input"))
      (node (ref "D11") (pin "D2") (pinfunction "C_D2") (pintype "input"))
      (node (ref "D11") (pin "H1") (pinfunction "C_H1") (pintype "input"))
    )
    (net (code "134") (name "LPB_00") (class "Default")
      (node (ref "A25") (pin "T2") (pinfunction "P$2_T2") (pintype "bidirectional"))
      (node (ref "C08") (pin "D1") (pinfunction "IN2B_D1") (pintype "input"))
      (node (ref "D08") (pin "E1") (pinfunction "E1_E1") (pintype "output"))
    )
    (net (code "135") (name "LPB_01") (class "Default")
      (node (ref "A25") (pin "U2") (pinfunction "P$2_U2") (pintype "bidirectional"))
      (node (ref "C08") (pin "K1") (pinfunction "IN2B_K1") (pintype "input"))
      (node (ref "D08") (pin "L1") (pinfunction "L1_L1") (pintype "output"))
    )
    (net (code "136") (name "LPB_02") (class "Default")
      (node (ref "A25") (pin "V2") (pinfunction "P$2_V2") (pintype "bidirectional"))
      (node (ref "C08") (pin "R1") (pinfunction "IN2B_R1") (pintype "input"))
      (node (ref "D08") (pin "S1") (pinfunction "S1_S1") (pintype "output"))
    )
    (net (code "137") (name "LPB_03") (class "Default")
      (node (ref "A26") (pin "A2") (pinfunction "P$2_A2") (pintype "bidirectional"))
      (node (ref "C08") (pin "H2") (pinfunction "IN2B_H2") (pintype "input"))
      (node (ref "D08") (pin "H2") (pinfunction "H2_H2") (pintype "output"))
    )
    (net (code "138") (name "LPB_04") (class "Default")
      (node (ref "A26") (pin "B2") (pinfunction "P$2_B2") (pintype "bidirectional"))
      (node (ref "C08") (pin "N2") (pinfunction "IN2B_N2") (pintype "input"))
      (node (ref "D08") (pin "P2") (pinfunction "P2_P2") (pintype "output"))
    )
    (net (code "139") (name "LPB_05") (class "Default")
      (node (ref "A26") (pin "C2") (pinfunction "P$2_C2") (pintype "bidirectional"))
      (node (ref "C08") (pin "U2") (pinfunction "IN2B_U2") (pintype "input"))
      (node (ref "D08") (pin "V2") (pinfunction "V2_V2") (pintype "output"))
    )
    (net (code "140") (name "LPB_NOT_EQ_1") (class "Default")
      (node (ref "A10") (pin "M1") (pinfunction "IN2_M1") (pintype "input"))
      (node (ref "D10") (pin "V2") (pinfunction "OUT_V2") (pintype "output"))
    )
    (net (code "141") (name "LPB_TO_DTB") (class "Default")
      (node (ref "A11") (pin "T2") (pinfunction "OUT_T2") (pintype "output"))
      (node (ref "C08") (pin "C1") (pinfunction "IN2A_C1") (pintype "input"))
      (node (ref "C08") (pin "F2") (pinfunction "IN2A_F2") (pintype "input"))
      (node (ref "C08") (pin "J1") (pinfunction "IN2A_J1") (pintype "input"))
      (node (ref "C08") (pin "M2") (pinfunction "IN2A_M2") (pintype "input"))
      (node (ref "C08") (pin "P1") (pinfunction "IN2A_P1") (pintype "input"))
      (node (ref "C08") (pin "T2") (pinfunction "IN2A_T2") (pintype "input"))
    )
    (net (code "142") (name "MC00") (class "Default")
      (node (ref "A26") (pin "S1") (pinfunction "P$2_S1") (pintype "bidirectional"))
      (node (ref "B13") (pin "E1") (pinfunction "1_E1") (pintype "output"))
      (node (ref "B13") (pin "E2") (pinfunction "D_E2") (pintype "input"))
      (node (ref "D10") (pin "D2") (pinfunction "IN5_D2") (pintype "input"))
    )
    (net (code "143") (name "MC01") (class "Default")
      (node (ref "A08") (pin "L2") (pinfunction "C_L2") (pintype "input"))
      (node (ref "A26") (pin "T1") (pinfunction "P$2_T1") (pintype "bidirectional"))
      (node (ref "B13") (pin "H2") (pinfunction "1_H2") (pintype "output"))
      (node (ref "B13") (pin "J1") (pinfunction "D_J1") (pintype "input"))
      (node (ref "C11") (pin "E1") (pinfunction "IN2_E1") (pintype "input"))
    )
    (net (code "144") (name "MC02") (class "Default")
      (node (ref "A26") (pin "U1") (pinfunction "P$2_U1") (pintype "bidirectional"))
      (node (ref "B11") (pin "U2") (pinfunction "IN2_U2") (pintype "input"))
      (node (ref "B13") (pin "L1") (pinfunction "1_L1") (pintype "output"))
      (node (ref "D12") (pin "D2") (pinfunction "IN1_D2") (pintype "input"))
      (node (ref "D12") (pin "E2") (pinfunction "IN2_E2") (pintype "input"))
    )
    (net (code "145") (name "MF00") (class "Default")
      (node (ref "A25") (pin "V1") (pinfunction "P$2_V1") (pintype "bidirectional"))
      (node (ref "D11") (pin "E1") (pinfunction "1_E1") (pintype "output"))
    )
    (net (code "146") (name "MF01") (class "Default")
      (node (ref "A26") (pin "A1") (pinfunction "P$2_A1") (pintype "bidirectional"))
      (node (ref "D11") (pin "H2") (pinfunction "1_H2") (pintype "output"))
    )
    (net (code "147") (name "MF02") (class "Default")
      (node (ref "A26") (pin "B1") (pinfunction "P$2_B1") (pintype "bidirectional"))
      (node (ref "D11") (pin "L1") (pinfunction "1_L1") (pintype "output"))
    )
    (net (code "148") (name "MKT") (class "Default")
      (node (ref "A26") (pin "H2") (pinfunction "P$2_H2") (pintype "bidirectional"))
      (node (ref "B12") (pin "S2") (pinfunction "IN2_S2") (pintype "input"))
      (node (ref "B13") (pin "V2") (pinfunction "1_V2") (pintype "output"))
      (node (ref "B15") (pin "L1") (pinfunction "IN1_L1") (pintype "input"))
      (node (ref "C15") (pin "L2") (pinfunction "IN1_L2") (pintype "input"))
    )
    (net (code "149") (name "MKTK") (class "Default")
      (node (ref "A08") (pin "R2") (pinfunction "0_R2") (pintype "output"))
      (node (ref "A25") (pin "P1") (pinfunction "P$2_P1") (pintype "bidirectional"))
    )
    (net (code "150") (name "MK_BLK_END") (class "Default")
      (node (ref "A09") (pin "T2") (pinfunction "IN3_T2") (pintype "input"))
      (node (ref "CD18") (pin "BU1") (pinfunction "BU1_BU1") (pintype "output"))
    )
    (net (code "151") (name "MK_BLK_MK") (class "Default")
      (node (ref "CD18") (pin "AE2") (pinfunction "AE2_AE2") (pintype "output"))
      (node (ref "D10") (pin "A1") (pinfunction "IN1_A1") (pintype "input"))
      (node (ref "D10") (pin "B1") (pinfunction "IN2_B1") (pintype "input"))
    )
    (net (code "152") (name "MK_BLK_START") (class "Default")
      (node (ref "CD18") (pin "AJ2") (pinfunction "AJ2_AJ2") (pintype "output"))
    )
    (net (code "153") (name "MK_BLK_SYNC") (class "Default")
      (node (ref "CD18") (pin "BS2") (pinfunction "BS2_BS2") (pintype "output"))
    )
    (net (code "154") (name "MK_DATA") (class "Default")
      (node (ref "CD18") (pin "BP2") (pinfunction "BP2_BP2") (pintype "output"))
    )
    (net (code "155") (name "MK_DATA_SYNC") (class "Default")
      (node (ref "CD18") (pin "AH1") (pinfunction "AH1_AH1") (pintype "output"))
    )
    (net (code "156") (name "MK_END") (class "Default")
      (node (ref "A08") (pin "C1") (pinfunction "D_C1") (pintype "input"))
      (node (ref "CD18") (pin "AF2") (pinfunction "AF2_AF2") (pintype "output"))
    )
    (net (code "157") (name "MOVE") (class "Default")
      (node (ref "D07") (pin "D2") (pinfunction "O0_D2") (pintype "output"))
    )
    (net (code "158") (name "MR00") (class "Default")
      (node (ref "A25") (pin "D1") (pinfunction "P$2_D1") (pintype "bidirectional"))
      (node (ref "B07") (pin "P2") (pinfunction "P2_P2") (pintype "output"))
      (node (ref "B14") (pin "M2") (pinfunction "D_M2") (pintype "input"))
    )
    (net (code "159") (name "MR01") (class "Default")
      (node (ref "A25") (pin "E1") (pinfunction "P$2_E1") (pintype "bidirectional"))
      (node (ref "C07") (pin "P2") (pinfunction "P2_P2") (pintype "output"))
      (node (ref "C12") (pin "B1") (pinfunction "IN2_B1") (pintype "input"))
    )
    (net (code "160") (name "Net-(A08D-D)") (class "Default")
      (node (ref "A08") (pin "E2") (pinfunction "D_E2") (pintype "input"))
      (node (ref "A09") (pin "L1") (pinfunction "OUT_L1") (pintype "output"))
    )
    (net (code "161") (name "Net-(A08E-S)") (class "Default")
      (node (ref "A08") (pin "K1") (pinfunction "S_K1") (pintype "input"))
      (node (ref "A11") (pin "E1") (pinfunction "OUT_E1") (pintype "output"))
    )
    (net (code "162") (name "Net-(A08F-D)") (class "Default")
      (node (ref "A08") (pin "M2") (pinfunction "D_M2") (pintype "input"))
      (node (ref "A09") (pin "J2") (pinfunction "OUT_J2") (pintype "output"))
    )
    (net (code "163") (name "Net-(A08G-C)") (class "Default")
      (node (ref "A08") (pin "N1") (pinfunction "C_N1") (pintype "input"))
      (node (ref "A11") (pin "D2") (pinfunction "OUT_D2") (pintype "output"))
    )
    (net (code "164") (name "Net-(A08G-D)") (class "Default")
      (node (ref "A08") (pin "P1") (pinfunction "D_P1") (pintype "input"))
      (node (ref "A10") (pin "N1") (pinfunction "OUT_N1") (pintype "output"))
    )
    (net (code "165") (name "Net-(A08H-S)") (class "Default")
      (node (ref "A08") (pin "U2") (pinfunction "S_U2") (pintype "input"))
      (node (ref "B10") (pin "S1") (pinfunction "OUT_S1") (pintype "output"))
    )
    (net (code "166") (name "Net-(A09A-OUT)") (class "Default")
      (node (ref "A09") (pin "E1") (pinfunction "OUT_E1") (pintype "output"))
      (node (ref "A11") (pin "A1") (pinfunction "IN_A1") (pintype "input"))
    )
    (net (code "167") (name "Net-(A09D-IN4)") (class "Default")
      (node (ref "A09") (pin "H2") (pinfunction "IN4_H2") (pintype "input"))
      (node (ref "A11") (pin "B1") (pinfunction "OUT_B1") (pintype "output"))
    )
    (net (code "168") (name "Net-(A09E-IN1)") (class "Default")
      (node (ref "A09") (pin "F1") (pinfunction "IN1_F1") (pintype "input"))
      (node (ref "C10") (pin "P2") (pinfunction "OUT_P2") (pintype "output"))
    )
    (net (code "169") (name "Net-(A09E-IN3)") (class "Default")
      (node (ref "A09") (pin "J1") (pinfunction "IN3_J1") (pintype "input"))
      (node (ref "A10") (pin "K1") (pinfunction "OUT_K1") (pintype "output"))
    )
    (net (code "170") (name "Net-(A09F-OUT)") (class "Default")
      (node (ref "A09") (pin "P2") (pinfunction "OUT_P2") (pintype "output"))
      (node (ref "A11") (pin "F1") (pinfunction "IN_F1") (pintype "input"))
    )
    (net (code "171") (name "Net-(A09G-OUT)") (class "Default")
      (node (ref "A09") (pin "S1") (pinfunction "OUT_S1") (pintype "output"))
      (node (ref "A10") (pin "U2") (pinfunction "IN2_U2") (pintype "input"))
    )
    (net (code "172") (name "Net-(A09J-IN4)") (class "Default")
      (node (ref "A09") (pin "U2") (pinfunction "IN4_U2") (pintype "input"))
      (node (ref "C17") (pin "R2") (pinfunction "OUT_R2") (pintype "output"))
    )
    (net (code "173") (name "Net-(A09J-OUT)") (class "Default")
      (node (ref "A09") (pin "V2") (pinfunction "OUT_V2") (pintype "output"))
      (node (ref "A11") (pin "S2") (pinfunction "IN_S2") (pintype "input"))
    )
    (net (code "174") (name "Net-(A10A-IN2)") (class "Default")
      (node (ref "A10") (pin "B1") (pinfunction "IN2_B1") (pintype "input"))
      (node (ref "A10") (pin "F1") (pinfunction "OUT_F1") (pintype "output"))
      (node (ref "B15") (pin "P2") (pinfunction "IN1_P2") (pintype "input"))
    )
    (net (code "175") (name "Net-(A10A-OUT)") (class "Default")
      (node (ref "A10") (pin "C1") (pinfunction "OUT_C1") (pintype "output"))
      (node (ref "A10") (pin "D1") (pinfunction "IN1_D1") (pintype "input"))
    )
    (net (code "176") (name "Net-(A10C-OUT)") (class "Default")
      (node (ref "A10") (pin "F2") (pinfunction "OUT_F2") (pintype "output"))
      (node (ref "A10") (pin "J2") (pinfunction "IN2_J2") (pintype "input"))
    )
    (net (code "177") (name "Net-(A10J-OUT)") (class "Default")
      (node (ref "A10") (pin "S1") (pinfunction "OUT_S1") (pintype "output"))
      (node (ref "A11") (pin "C1") (pinfunction "IN_C1") (pintype "input"))
    )
    (net (code "178") (name "Net-(A10K-OUT)") (class "Default")
      (node (ref "A10") (pin "S2") (pinfunction "OUT_S2") (pintype "output"))
      (node (ref "A10") (pin "T2") (pinfunction "IN1_T2") (pintype "input"))
    )
    (net (code "179") (name "Net-(A10N-OUT)") (class "Default")
      (node (ref "A10") (pin "V2") (pinfunction "OUT_V2") (pintype "output"))
      (node (ref "A11") (pin "D1") (pinfunction "IN_D1") (pintype "input"))
    )
    (net (code "180") (name "Net-(A11G-OUT)") (class "Default")
      (node (ref "A11") (pin "H1") (pinfunction "OUT_H1") (pintype "output"))
      (node (ref "A12") (pin "B1") (pinfunction "IN2_B1") (pintype "input"))
      (node (ref "A12") (pin "D1") (pinfunction "IN1_D1") (pintype "input"))
    )
    (net (code "181") (name "Net-(A11N-IN)") (class "Default")
      (node (ref "A11") (pin "P2") (pinfunction "IN_P2") (pintype "input"))
      (node (ref "A14") (pin "F2") (pinfunction "F2_F2") (pintype "output"))
    )
    (net (code "182") (name "Net-(A11O-IN)") (class "Default")
      (node (ref "A11") (pin "R1") (pinfunction "IN_R1") (pintype "input"))
      (node (ref "B11") (pin "S2") (pinfunction "OUT_S2") (pintype "output"))
    )
    (net (code "183") (name "Net-(A11Q-IN)") (class "Default")
      (node (ref "A11") (pin "V1") (pinfunction "IN_V1") (pintype "input"))
      (node (ref "B08") (pin "V2") (pinfunction "OUT_V2") (pintype "output"))
    )
    (net (code "184") (name "Net-(A11R-IN)") (class "Default")
      (node (ref "A11") (pin "U2") (pinfunction "IN_U2") (pintype "input"))
      (node (ref "A14") (pin "T2") (pinfunction "F2_T2") (pintype "output"))
    )
    (net (code "185") (name "Net-(A12C-OUT)") (class "Default")
      (node (ref "A12") (pin "F2") (pinfunction "OUT_F2") (pintype "output"))
      (node (ref "B10") (pin "A1") (pinfunction "IN1_A1") (pintype "input"))
      (node (ref "B10") (pin "B1") (pinfunction "IN2_B1") (pintype "input"))
    )
    (net (code "186") (name "Net-(A12F-IN2)") (class "Default")
      (node (ref "A12") (pin "J1") (pinfunction "IN2_J1") (pintype "input"))
      (node (ref "A12") (pin "N1") (pinfunction "OUT_N1") (pintype "output"))
      (node (ref "A12") (pin "P1") (pinfunction "IN1_P1") (pintype "input"))
    )
    (net (code "187") (name "Net-(A12G-OUT)") (class "Default")
      (node (ref "A12") (pin "K2") (pinfunction "OUT_K2") (pintype "output"))
      (node (ref "B10") (pin "C1") (pinfunction "IN3_C1") (pintype "input"))
      (node (ref "B10") (pin "D1") (pinfunction "IN4_D1") (pintype "input"))
    )
    (net (code "188") (name "Net-(A12I-OUT)") (class "Default")
      (node (ref "A12") (pin "N2") (pinfunction "OUT_N2") (pintype "output"))
      (node (ref "A12") (pin "T2") (pinfunction "IN1_T2") (pintype "input"))
    )
    (net (code "189") (name "Net-(A12K-OUT)") (class "Default")
      (node (ref "A12") (pin "S2") (pinfunction "OUT_S2") (pintype "output"))
      (node (ref "A12") (pin "U2") (pinfunction "IN2_U2") (pintype "input"))
    )
    (net (code "190") (name "Net-(A14-PadD2)") (class "Default")
      (node (ref "A14") (pin "D2") (pinfunction "D2_D2") (pintype "passive"))
      (node (ref "A14") (pin "E2") (pinfunction "E2_E2") (pintype "passive"))
    )
    (net (code "191") (name "Net-(A14-PadH1)") (class "Default")
      (node (ref "A14") (pin "H1") (pinfunction "H1_H1") (pintype "passive"))
      (node (ref "A14") (pin "L2") (pinfunction "L2_L2") (pintype "passive"))
    )
    (net (code "192") (name "Net-(A14D-D2)") (class "Default")
      (node (ref "A14") (pin "R2") (pinfunction "E2_R2") (pintype "passive"))
      (node (ref "A14") (pin "V2") (pinfunction "D2_V2") (pintype "passive"))
    )
    (net (code "193") (name "Net-(A14D-H1)") (class "Default")
      (node (ref "A14") (pin "S1") (pinfunction "H1_S1") (pintype "passive"))
      (node (ref "A14") (pin "S2") (pinfunction "L2_S2") (pintype "passive"))
    )
    (net (code "194") (name "Net-(A14D-H2)") (class "Default")
      (node (ref "A14") (pin "M2") (pinfunction "H2_M2") (pintype "input"))
      (node (ref "A14") (pin "N2") (pinfunction "J2_N2") (pintype "input"))
      (node (ref "A14") (pin "P2") (pinfunction "K2_P2") (pintype "input"))
      (node (ref "B15") (pin "F2") (pinfunction "OUT_F2") (pintype "output"))
    )
    (net (code "195") (name "Net-(A15A-IN3)") (class "Default")
      (node (ref "A15") (pin "C1") (pinfunction "IN3_C1") (pintype "input"))
      (node (ref "A15") (pin "D1") (pinfunction "IN4_D1") (pintype "input"))
      (node (ref "C17") (pin "D2") (pinfunction "OUT_D2") (pintype "output"))
    )
    (net (code "196") (name "Net-(A15D-IN1)") (class "Default")
      (node (ref "A15") (pin "D2") (pinfunction "IN1_D2") (pintype "input"))
      (node (ref "A15") (pin "E2") (pinfunction "IN2_E2") (pintype "input"))
      (node (ref "C17") (pin "F2") (pinfunction "OUT_F2") (pintype "output"))
    )
    (net (code "197") (name "Net-(A16-PadD2)") (class "Default")
      (node (ref "A16") (pin "D2") (pinfunction "D2_D2") (pintype "passive"))
      (node (ref "A16") (pin "E2") (pinfunction "E2_E2") (pintype "passive"))
    )
    (net (code "198") (name "Net-(A16C-D2)") (class "Default")
      (node (ref "A16") (pin "R2") (pinfunction "E2_R2") (pintype "passive"))
      (node (ref "A16") (pin "S2") (pinfunction "D2_S2") (pintype "passive"))
    )
    (net (code "199") (name "Net-(AB19A-P$2)") (class "Default")
      (node (ref "A18") (pin "D2") (pinfunction "D2_D2") (pintype "input"))
      (node (ref "A18") (pin "J2") (pinfunction "J2_J2") (pintype "output"))
      (node (ref "AB19") (pin "AF2") (pinfunction "P$2_AF2") (pintype "bidirectional"))
    )
    (net (code "200") (name "Net-(AB19B-P$2)") (class "Default")
      (node (ref "A18") (pin "E2") (pinfunction "E2_E2") (pintype "input"))
      (node (ref "A18") (pin "K2") (pinfunction "K2_K2") (pintype "output"))
      (node (ref "AB19") (pin "AH2") (pinfunction "P$2_AH2") (pintype "bidirectional"))
    )
    (net (code "201") (name "Net-(AB19D-P$2)") (class "Default")
      (node (ref "AB19") (pin "AN2") (pinfunction "P$2_AN2") (pintype "bidirectional"))
      (node (ref "B18") (pin "D2") (pinfunction "D2_D2") (pintype "input"))
      (node (ref "B18") (pin "J2") (pinfunction "J2_J2") (pintype "output"))
    )
    (net (code "202") (name "Net-(AB19E-P$2)") (class "Default")
      (node (ref "AB19") (pin "AP2") (pinfunction "P$2_AP2") (pintype "bidirectional"))
      (node (ref "B18") (pin "E2") (pinfunction "E2_E2") (pintype "input"))
      (node (ref "B18") (pin "K2") (pinfunction "K2_K2") (pintype "output"))
    )
    (net (code "203") (name "Net-(AB19H-P$2)") (class "Default")
      (node (ref "A20") (pin "D2") (pinfunction "D2_D2") (pintype "input"))
      (node (ref "A20") (pin "J2") (pinfunction "J2_J2") (pintype "output"))
      (node (ref "AB19") (pin "AV2") (pinfunction "P$2_AV2") (pintype "bidirectional"))
    )
    (net (code "204") (name "Net-(AB19I-P$2)") (class "Default")
      (node (ref "A20") (pin "E2") (pinfunction "E2_E2") (pintype "input"))
      (node (ref "A20") (pin "K2") (pinfunction "K2_K2") (pintype "output"))
      (node (ref "AB19") (pin "BD2") (pinfunction "P$2_BD2") (pintype "bidirectional"))
    )
    (net (code "205") (name "Net-(AB19K-P$2)") (class "Default")
      (node (ref "AB19") (pin "BH2") (pinfunction "P$2_BH2") (pintype "bidirectional"))
      (node (ref "B20") (pin "D2") (pinfunction "D2_D2") (pintype "input"))
      (node (ref "B20") (pin "J2") (pinfunction "J2_J2") (pintype "output"))
    )
    (net (code "206") (name "Net-(AB19L-P$2)") (class "Default")
      (node (ref "AB19") (pin "BJ2") (pinfunction "P$2_BJ2") (pintype "bidirectional"))
      (node (ref "B20") (pin "E2") (pinfunction "E2_E2") (pintype "input"))
      (node (ref "B20") (pin "K2") (pinfunction "K2_K2") (pintype "output"))
    )
    (net (code "207") (name "Net-(AB19N-P$2)") (class "Default")
      (node (ref "A21") (pin "D2") (pinfunction "D2_D2") (pintype "input"))
      (node (ref "A21") (pin "J2") (pinfunction "J2_J2") (pintype "output"))
      (node (ref "AB19") (pin "BN2") (pinfunction "P$2_BN2") (pintype "bidirectional"))
    )
    (net (code "208") (name "Net-(AB19O-P$2)") (class "Default")
      (node (ref "A21") (pin "E2") (pinfunction "E2_E2") (pintype "input"))
      (node (ref "A21") (pin "K2") (pinfunction "K2_K2") (pintype "output"))
      (node (ref "AB19") (pin "BP2") (pinfunction "P$2_BP2") (pintype "bidirectional"))
    )
    (net (code "209") (name "Net-(B06P-IN)") (class "Default")
      (node (ref "B06") (pin "S2") (pinfunction "IN_S2") (pintype "input"))
      (node (ref "B08") (pin "S2") (pinfunction "OUT_S2") (pintype "output"))
    )
    (net (code "210") (name "Net-(B08A-OUT)") (class "Default")
      (node (ref "B08") (pin "C1") (pinfunction "OUT_C1") (pintype "output"))
      (node (ref "B09") (pin "D1") (pinfunction "S_D1") (pintype "input"))
    )
    (net (code "211") (name "Net-(B08B-OUT)") (class "Default")
      (node (ref "B08") (pin "F1") (pinfunction "OUT_F1") (pintype "output"))
      (node (ref "B09") (pin "U2") (pinfunction "S_U2") (pintype "input"))
    )
    (net (code "212") (name "Net-(B08C-OUT)") (class "Default")
      (node (ref "B08") (pin "F2") (pinfunction "OUT_F2") (pintype "output"))
      (node (ref "B09") (pin "K1") (pinfunction "S_K1") (pintype "input"))
    )
    (net (code "213") (name "Net-(B08F-OUT)") (class "Default")
      (node (ref "B08") (pin "K1") (pinfunction "OUT_K1") (pintype "output"))
      (node (ref "B09") (pin "F2") (pinfunction "S_F2") (pintype "input"))
    )
    (net (code "214") (name "Net-(B08H-OUT)") (class "Default")
      (node (ref "B08") (pin "N1") (pinfunction "OUT_N1") (pintype "output"))
      (node (ref "B09") (pin "N2") (pinfunction "S_N2") (pintype "input"))
    )
    (net (code "215") (name "Net-(B08J-OUT)") (class "Default")
      (node (ref "B08") (pin "S1") (pinfunction "OUT_S1") (pintype "output"))
      (node (ref "B09") (pin "R1") (pinfunction "S_R1") (pintype "input"))
    )
    (net (code "216") (name "Net-(B10E-IN1)") (class "Default")
      (node (ref "B10") (pin "F1") (pinfunction "IN1_F1") (pintype "input"))
      (node (ref "B11") (pin "J1") (pinfunction "OUT_J1") (pintype "output"))
    )
    (net (code "217") (name "Net-(B10E-IN4)") (class "Default")
      (node (ref "B10") (pin "K1") (pinfunction "IN4_K1") (pintype "input"))
      (node (ref "C17") (pin "H1") (pinfunction "OUT_H1") (pintype "output"))
    )
    (net (code "218") (name "Net-(B11A-OUT)") (class "Default")
      (node (ref "B11") (pin "D1") (pinfunction "OUT_D1") (pintype "output"))
      (node (ref "B11") (pin "F2") (pinfunction "IN3_F2") (pintype "input"))
    )
    (net (code "219") (name "Net-(B11D-IN1)") (class "Default")
      (node (ref "B11") (pin "D2") (pinfunction "IN1_D2") (pintype "input"))
      (node (ref "B12") (pin "E1") (pinfunction "OUT_E1") (pintype "output"))
    )
    (net (code "220") (name "Net-(B11D-IN2)") (class "Default")
      (node (ref "B11") (pin "E2") (pinfunction "IN2_E2") (pintype "input"))
      (node (ref "B12") (pin "L1") (pinfunction "OUT_L1") (pintype "output"))
    )
    (net (code "221") (name "Net-(B11D-OUT)") (class "Default")
      (node (ref "B11") (pin "H2") (pinfunction "OUT_H2") (pintype "output"))
      (node (ref "C13") (pin "C1") (pinfunction "IN_C1") (pintype "input"))
    )
    (net (code "222") (name "Net-(B11E-IN1)") (class "Default")
      (node (ref "B11") (pin "E1") (pinfunction "IN1_E1") (pintype "input"))
      (node (ref "B11") (pin "U1") (pinfunction "OUT_U1") (pintype "output"))
    )
    (net (code "223") (name "Net-(B11E-IN3)") (class "Default")
      (node (ref "B11") (pin "H1") (pinfunction "IN3_H1") (pintype "input"))
      (node (ref "B11") (pin "N1") (pinfunction "OUT_N1") (pintype "output"))
    )
    (net (code "224") (name "Net-(B11F-IN3)") (class "Default")
      (node (ref "B11") (pin "L2") (pinfunction "IN3_L2") (pintype "input"))
      (node (ref "B15") (pin "S2") (pinfunction "OUT_S2") (pintype "output"))
    )
    (net (code "225") (name "Net-(B11J-OUT)") (class "Default")
      (node (ref "B11") (pin "V1") (pinfunction "OUT_V1") (pintype "output"))
      (node (ref "C17") (pin "J1") (pinfunction "IN_J1") (pintype "input"))
    )
    (net (code "226") (name "Net-(B12D-OUT)") (class "Default")
      (node (ref "B12") (pin "J2") (pinfunction "OUT_J2") (pintype "output"))
      (node (ref "B12") (pin "N2") (pinfunction "IN4_N2") (pintype "input"))
    )
    (net (code "227") (name "Net-(B12F-IN1)") (class "Default")
      (node (ref "B12") (pin "K2") (pinfunction "IN1_K2") (pintype "input"))
      (node (ref "C12") (pin "N1") (pinfunction "OUT_N1") (pintype "output"))
    )
    (net (code "228") (name "Net-(B12F-IN2)") (class "Default")
      (node (ref "B12") (pin "L2") (pinfunction "IN2_L2") (pintype "input"))
      (node (ref "C12") (pin "U1") (pinfunction "OUT_U1") (pintype "output"))
    )
    (net (code "229") (name "Net-(B12F-IN3)") (class "Default")
      (node (ref "B12") (pin "M2") (pinfunction "IN3_M2") (pintype "input"))
      (node (ref "C12") (pin "V1") (pinfunction "OUT_V1") (pintype "output"))
    )
    (net (code "230") (name "Net-(B12G-IN1)") (class "Default")
      (node (ref "B12") (pin "M1") (pinfunction "IN1_M1") (pintype "input"))
      (node (ref "C11") (pin "C1") (pinfunction "OUT_C1") (pintype "output"))
    )
    (net (code "231") (name "Net-(B12G-IN4)") (class "Default")
      (node (ref "B12") (pin "R1") (pinfunction "IN4_R1") (pintype "input"))
      (node (ref "C11") (pin "F1") (pinfunction "OUT_F1") (pintype "output"))
    )
    (net (code "232") (name "Net-(B12G-OUT)") (class "Default")
      (node (ref "B12") (pin "S1") (pinfunction "OUT_S1") (pintype "output"))
      (node (ref "C11") (pin "P1") (pinfunction "IN1_P1") (pintype "input"))
    )
    (net (code "233") (name "Net-(B12J-IN4)") (class "Default")
      (node (ref "B12") (pin "U2") (pinfunction "IN4_U2") (pintype "input"))
      (node (ref "C11") (pin "N1") (pinfunction "OUT_N1") (pintype "output"))
    )
    (net (code "234") (name "Net-(B12J-OUT)") (class "Default")
      (node (ref "B12") (pin "V2") (pinfunction "OUT_V2") (pintype "output"))
      (node (ref "C12") (pin "F1") (pinfunction "IN2_F1") (pintype "input"))
    )
    (net (code "235") (name "Net-(B13F-S)") (class "Default")
      (node (ref "B13") (pin "N2") (pinfunction "S_N2") (pintype "input"))
      (node (ref "B15") (pin "K1") (pinfunction "OUT_K1") (pintype "output"))
    )
    (net (code "236") (name "Net-(B14G-C)") (class "Default")
      (node (ref "B14") (pin "N1") (pinfunction "C_N1") (pintype "input"))
      (node (ref "B14") (pin "S2") (pinfunction "C_S2") (pintype "input"))
      (node (ref "D15") (pin "D2") (pinfunction "D2_D2") (pintype "output"))
    )
    (net (code "237") (name "Net-(B15B-OUT)") (class "Default")
      (node (ref "A14") (pin "H2") (pinfunction "H2_H2") (pintype "input"))
      (node (ref "A14") (pin "J2") (pinfunction "J2_J2") (pintype "input"))
      (node (ref "A14") (pin "K2") (pinfunction "K2_K2") (pintype "input"))
      (node (ref "B15") (pin "F1") (pinfunction "OUT_F1") (pintype "output"))
    )
    (net (code "238") (name "Net-(B15H-OUT)") (class "Default")
      (node (ref "B15") (pin "N1") (pinfunction "OUT_N1") (pintype "output"))
      (node (ref "C17") (pin "F1") (pinfunction "IN_F1") (pintype "input"))
    )
    (net (code "239") (name "Net-(B15J-OUT)") (class "Default")
      (node (ref "B15") (pin "S1") (pinfunction "OUT_S1") (pintype "output"))
      (node (ref "C17") (pin "L1") (pinfunction "IN_L1") (pintype "input"))
    )
    (net (code "240") (name "Net-(B16-PadD2)") (class "Default")
      (node (ref "B16") (pin "D2") (pinfunction "D2_D2") (pintype "passive"))
      (node (ref "B16") (pin "E2") (pinfunction "E2_E2") (pintype "passive"))
    )
    (net (code "241") (name "Net-(B16C-D2)") (class "Default")
      (node (ref "B16") (pin "R2") (pinfunction "E2_R2") (pintype "passive"))
      (node (ref "B16") (pin "S2") (pinfunction "D2_S2") (pintype "passive"))
    )
    (net (code "242") (name "Net-(C08A-OUT)") (class "Default")
      (node (ref "C08") (pin "E1") (pinfunction "OUT_E1") (pintype "output"))
      (node (ref "C09") (pin "D1") (pinfunction "S_D1") (pintype "input"))
    )
    (net (code "243") (name "Net-(C08D-OUT)") (class "Default")
      (node (ref "C08") (pin "J2") (pinfunction "OUT_J2") (pintype "output"))
      (node (ref "C09") (pin "N2") (pinfunction "S_N2") (pintype "input"))
    )
    (net (code "244") (name "Net-(C08E-OUT)") (class "Default")
      (node (ref "C08") (pin "L1") (pinfunction "OUT_L1") (pintype "output"))
      (node (ref "C09") (pin "F2") (pinfunction "S_F2") (pintype "input"))
    )
    (net (code "245") (name "Net-(C08F-OUT)") (class "Default")
      (node (ref "C08") (pin "P2") (pinfunction "OUT_P2") (pintype "output"))
      (node (ref "C09") (pin "R1") (pinfunction "S_R1") (pintype "input"))
    )
    (net (code "246") (name "Net-(C08G-OUT)") (class "Default")
      (node (ref "C08") (pin "S1") (pinfunction "OUT_S1") (pintype "output"))
      (node (ref "C09") (pin "K1") (pinfunction "S_K1") (pintype "input"))
    )
    (net (code "247") (name "Net-(C08J-OUT)") (class "Default")
      (node (ref "C08") (pin "V2") (pinfunction "OUT_V2") (pintype "output"))
      (node (ref "C09") (pin "U2") (pinfunction "S_U2") (pintype "input"))
    )
    (net (code "248") (name "Net-(C10A-OUT)") (class "Default")
      (node (ref "C10") (pin "E1") (pinfunction "OUT_E1") (pintype "output"))
      (node (ref "C14") (pin "C1") (pinfunction "D_C1") (pintype "input"))
    )
    (net (code "249") (name "Net-(C10D-OUT)") (class "Default")
      (node (ref "C10") (pin "J2") (pinfunction "OUT_J2") (pintype "output"))
      (node (ref "C17") (pin "M2") (pinfunction "IN_M2") (pintype "input"))
    )
    (net (code "250") (name "Net-(C10E-OUT)") (class "Default")
      (node (ref "C10") (pin "L1") (pinfunction "OUT_L1") (pintype "output"))
      (node (ref "C14") (pin "E2") (pinfunction "D_E2") (pintype "input"))
    )
    (net (code "251") (name "Net-(C10G-OUT)") (class "Default")
      (node (ref "C10") (pin "S1") (pinfunction "OUT_S1") (pintype "output"))
      (node (ref "C14") (pin "J1") (pinfunction "D_J1") (pintype "input"))
    )
    (net (code "252") (name "Net-(C10J-OUT)") (class "Default")
      (node (ref "C10") (pin "V2") (pinfunction "OUT_V2") (pintype "output"))
      (node (ref "C17") (pin "V1") (pinfunction "IN_V1") (pintype "input"))
    )
    (net (code "253") (name "Net-(C11C-OUT)") (class "Default")
      (node (ref "C11") (pin "F2") (pinfunction "OUT_F2") (pintype "output"))
      (node (ref "C12") (pin "H1") (pinfunction "IN3_H1") (pintype "input"))
    )
    (net (code "254") (name "Net-(C11F-OUT)") (class "Default")
      (node (ref "C11") (pin "K1") (pinfunction "OUT_K1") (pintype "output"))
      (node (ref "C11") (pin "L1") (pinfunction "IN1_L1") (pintype "input"))
    )
    (net (code "255") (name "Net-(C11G-OUT)") (class "Default")
      (node (ref "C11") (pin "K2") (pinfunction "OUT_K2") (pintype "output"))
      (node (ref "D12") (pin "K2") (pinfunction "IN1_K2") (pintype "input"))
      (node (ref "D12") (pin "L2") (pinfunction "IN2_L2") (pintype "input"))
    )
    (net (code "256") (name "Net-(C11J-OUT)") (class "Default")
      (node (ref "C11") (pin "S1") (pinfunction "OUT_S1") (pintype "output"))
      (node (ref "C12") (pin "E1") (pinfunction "IN1_E1") (pintype "input"))
    )
    (net (code "257") (name "Net-(C11K-OUT)") (class "Default")
      (node (ref "C11") (pin "S2") (pinfunction "OUT_S2") (pintype "output"))
      (node (ref "C11") (pin "T2") (pinfunction "IN1_T2") (pintype "input"))
    )
    (net (code "258") (name "Net-(C11N-OUT)") (class "Default")
      (node (ref "C11") (pin "V2") (pinfunction "OUT_V2") (pintype "output"))
      (node (ref "C13") (pin "V1") (pinfunction "IN_V1") (pintype "input"))
    )
    (net (code "259") (name "Net-(C12A-OUT)") (class "Default")
      (node (ref "C12") (pin "D1") (pinfunction "OUT_D1") (pintype "output"))
      (node (ref "C13") (pin "M2") (pinfunction "IN_M2") (pintype "input"))
    )
    (net (code "260") (name "Net-(C12D-OUT)") (class "Default")
      (node (ref "C12") (pin "H2") (pinfunction "OUT_H2") (pintype "output"))
      (node (ref "D12") (pin "M2") (pinfunction "IN3_M2") (pintype "input"))
      (node (ref "D12") (pin "N2") (pinfunction "IN4_N2") (pintype "input"))
    )
    (net (code "261") (name "Net-(C12H-OUT)") (class "Default")
      (node (ref "C12") (pin "S2") (pinfunction "OUT_S2") (pintype "output"))
      (node (ref "C15") (pin "P1") (pinfunction "IN1_P1") (pintype "input"))
    )
    (net (code "262") (name "Net-(C13B-OUT)") (class "Default")
      (node (ref "C13") (pin "D2") (pinfunction "OUT_D2") (pintype "output"))
      (node (ref "C14") (pin "P1") (pinfunction "D_P1") (pintype "input"))
    )
    (net (code "263") (name "Net-(C13L-OUT)") (class "Default")
      (node (ref "C13") (pin "N2") (pinfunction "OUT_N2") (pintype "output"))
      (node (ref "C14") (pin "N2") (pinfunction "S_N2") (pintype "input"))
    )
    (net (code "264") (name "Net-(C13N-IN)") (class "Default")
      (node (ref "C13") (pin "P2") (pinfunction "IN_P2") (pintype "input"))
      (node (ref "C15") (pin "F2") (pinfunction "OUT_F2") (pintype "output"))
    )
    (net (code "265") (name "Net-(C13P-IN)") (class "Default")
      (node (ref "C13") (pin "S2") (pinfunction "IN_S2") (pintype "input"))
      (node (ref "C15") (pin "K2") (pinfunction "OUT_K2") (pintype "output"))
    )
    (net (code "266") (name "Net-(C14F-C)") (class "Default")
      (node (ref "C14") (pin "L2") (pinfunction "C_L2") (pintype "input"))
      (node (ref "C15") (pin "S2") (pinfunction "OUT_S2") (pintype "output"))
    )
    (net (code "267") (name "Net-(C15A-OUT)") (class "Default")
      (node (ref "C15") (pin "C1") (pinfunction "OUT_C1") (pintype "output"))
      (node (ref "C15") (pin "H1") (pinfunction "IN1_H1") (pintype "input"))
    )
    (net (code "268") (name "Net-(C15B-OUT)") (class "Default")
      (node (ref "C15") (pin "F1") (pinfunction "OUT_F1") (pintype "output"))
      (node (ref "C15") (pin "J1") (pinfunction "IN2_J1") (pintype "input"))
    )
    (net (code "269") (name "Net-(C15H-OUT)") (class "Default")
      (node (ref "C15") (pin "N1") (pinfunction "OUT_N1") (pintype "output"))
      (node (ref "C15") (pin "R1") (pinfunction "IN2_R1") (pintype "input"))
    )
    (net (code "270") (name "Net-(C15I-OUT)") (class "Default")
      (node (ref "C15") (pin "N2") (pinfunction "OUT_N2") (pintype "output"))
      (node (ref "C17") (pin "P2") (pinfunction "IN_P2") (pintype "input"))
    )
    (net (code "271") (name "Net-(C16F-IN1)") (class "Default")
      (node (ref "C16") (pin "K2") (pinfunction "IN1_K2") (pintype "input"))
      (node (ref "C16") (pin "L2") (pinfunction "IN2_L2") (pintype "input"))
      (node (ref "C16") (pin "M2") (pinfunction "IN3_M2") (pintype "input"))
      (node (ref "C16") (pin "N2") (pinfunction "IN4_N2") (pintype "input"))
      (node (ref "C17") (pin "B1") (pinfunction "OUT_B1") (pintype "output"))
    )
    (net (code "272") (name "Net-(C16G-OUT)") (class "Default")
      (node (ref "B16") (pin "K2") (pinfunction "K2_K2") (pintype "input"))
      (node (ref "C16") (pin "S1") (pinfunction "OUT_S1") (pintype "output"))
    )
    (net (code "273") (name "Net-(C16J-OUT)") (class "Default")
      (node (ref "A16") (pin "H2") (pinfunction "H2_H2") (pintype "input"))
      (node (ref "C16") (pin "V2") (pinfunction "OUT_V2") (pintype "output"))
    )
    (net (code "274") (name "Net-(C17B-IN)") (class "Default")
      (node (ref "A16") (pin "F2") (pinfunction "F2_F2") (pintype "output"))
      (node (ref "C17") (pin "C1") (pinfunction "IN_C1") (pintype "input"))
    )
    (net (code "275") (name "Net-(C17D-IN)") (class "Default")
      (node (ref "B16") (pin "F2") (pinfunction "F2_F2") (pintype "output"))
      (node (ref "C17") (pin "E2") (pinfunction "IN_E2") (pintype "input"))
    )
    (net (code "276") (name "Net-(C17L-OUT)") (class "Default")
      (node (ref "C17") (pin "N2") (pinfunction "OUT_N2") (pintype "output"))
      (node (ref "D08") (pin "B1") (pinfunction "B1_B1") (pintype "input"))
      (node (ref "D08") (pin "H1") (pinfunction "H1_H1") (pintype "input"))
      (node (ref "D08") (pin "N1") (pinfunction "N1_N1") (pintype "input"))
    )
    (net (code "277") (name "Net-(C17O-IN)") (class "Default")
      (node (ref "C17") (pin "R1") (pinfunction "IN_R1") (pintype "input"))
      (node (ref "D17") (pin "F2") (pinfunction "F2_F2") (pintype "output"))
    )
    (net (code "278") (name "Net-(C17P-IN)") (class "Default")
      (node (ref "C17") (pin "S2") (pinfunction "IN_S2") (pintype "input"))
      (node (ref "D16") (pin "T2") (pinfunction "F2_T2") (pintype "output"))
    )
    (net (code "279") (name "Net-(C17Q-OUT)") (class "Default")
      (node (ref "C17") (pin "U1") (pinfunction "OUT_U1") (pintype "output"))
      (node (ref "D08") (pin "D2") (pinfunction "D2_D2") (pintype "input"))
      (node (ref "D08") (pin "L2") (pinfunction "L2_L2") (pintype "input"))
      (node (ref "D08") (pin "S2") (pinfunction "S2_S2") (pintype "input"))
    )
    (net (code "280") (name "Net-(D09A-OUT)") (class "Default")
      (node (ref "D08") (pin "C1") (pinfunction "C1_C1") (pintype "input"))
      (node (ref "D08") (pin "D1") (pinfunction "D1_D1") (pintype "input"))
      (node (ref "D09") (pin "E1") (pinfunction "OUT_E1") (pintype "output"))
    )
    (net (code "281") (name "Net-(D09D-OUT)") (class "Default")
      (node (ref "D08") (pin "E2") (pinfunction "E2_E2") (pintype "input"))
      (node (ref "D08") (pin "F2") (pinfunction "F2_F2") (pintype "input"))
      (node (ref "D09") (pin "J2") (pinfunction "OUT_J2") (pintype "output"))
    )
    (net (code "282") (name "Net-(D09E-OUT)") (class "Default")
      (node (ref "D08") (pin "J1") (pinfunction "J1_J1") (pintype "input"))
      (node (ref "D08") (pin "K1") (pinfunction "K1_K1") (pintype "input"))
      (node (ref "D09") (pin "L1") (pinfunction "OUT_L1") (pintype "output"))
    )
    (net (code "283") (name "Net-(D09F-OUT)") (class "Default")
      (node (ref "D08") (pin "M2") (pinfunction "M2_M2") (pintype "input"))
      (node (ref "D08") (pin "N2") (pinfunction "N2_N2") (pintype "input"))
      (node (ref "D09") (pin "P2") (pinfunction "OUT_P2") (pintype "output"))
    )
    (net (code "284") (name "Net-(D09G-OUT)") (class "Default")
      (node (ref "D08") (pin "P1") (pinfunction "P1_P1") (pintype "input"))
      (node (ref "D08") (pin "R1") (pinfunction "R1_R1") (pintype "input"))
      (node (ref "D09") (pin "S1") (pinfunction "OUT_S1") (pintype "output"))
    )
    (net (code "285") (name "Net-(D09J-OUT)") (class "Default")
      (node (ref "D08") (pin "T2") (pinfunction "T2_T2") (pintype "input"))
      (node (ref "D08") (pin "U2") (pinfunction "U2_U2") (pintype "input"))
      (node (ref "D09") (pin "V2") (pinfunction "OUT_V2") (pintype "output"))
    )
    (net (code "286") (name "Net-(D10D-OUT)") (class "Default")
      (node (ref "D10") (pin "P2") (pinfunction "OUT_P2") (pintype "output"))
      (node (ref "D14") (pin "J2") (pinfunction "N1_J2") (pintype "input"))
    )
    (net (code "287") (name "Net-(D12A-IN1)") (class "Default")
      (node (ref "D12") (pin "A1") (pinfunction "IN1_A1") (pintype "input"))
      (node (ref "D12") (pin "B1") (pinfunction "IN2_B1") (pintype "input"))
      (node (ref "D12") (pin "C1") (pinfunction "IN3_C1") (pintype "input"))
      (node (ref "D12") (pin "D1") (pinfunction "IN4_D1") (pintype "input"))
      (node (ref "D13") (pin "F2") (pinfunction "F2_F2") (pintype "output"))
    )
    (net (code "288") (name "Net-(D13C-D2)") (class "Default")
      (node (ref "D13") (pin "R2") (pinfunction "E2_R2") (pintype "passive"))
      (node (ref "D13") (pin "S2") (pinfunction "D2_S2") (pintype "passive"))
    )
    (net (code "289") (name "Net-(D14-PadM2)") (class "Default")
      (node (ref "D14") (pin "M2") (pinfunction "M2_M2") (pintype "passive"))
      (node (ref "D14") (pin "V2") (pinfunction "V2_V2") (pintype "passive"))
    )
    (net (code "290") (name "Net-(D14-PadP1)") (class "Default")
      (node (ref "D14") (pin "P1") (pinfunction "P1_P1") (pintype "passive"))
      (node (ref "D14") (pin "V1") (pinfunction "V1_V1") (pintype "passive"))
    )
    (net (code "291") (name "Net-(D14E-M2)") (class "Default")
      (node (ref "D14") (pin "D2") (pinfunction "M2_D2") (pintype "passive"))
      (node (ref "D14") (pin "H1") (pinfunction "P2_H1") (pintype "passive"))
    )
    (net (code "292") (name "Net-(D14E-P1)") (class "Default")
      (node (ref "D14") (pin "A1") (pinfunction "V1_A1") (pintype "passive"))
      (node (ref "D14") (pin "C1") (pinfunction "P1_C1") (pintype "passive"))
    )
    (net (code "293") (name "Net-(D15-PadN2)") (class "Default")
      (node (ref "D15") (pin "N2") (pinfunction "N2_N2") (pintype "passive"))
      (node (ref "D15") (pin "S2") (pinfunction "S2_S2") (pintype "passive"))
    )
    (net (code "294") (name "Net-(D16D-D2)") (class "Default")
      (node (ref "D16") (pin "R2") (pinfunction "E2_R2") (pintype "passive"))
      (node (ref "D16") (pin "V2") (pinfunction "D2_V2") (pintype "passive"))
    )
    (net (code "295") (name "Net-(D16D-H1)") (class "Default")
      (node (ref "D16") (pin "S1") (pinfunction "H1_S1") (pintype "passive"))
      (node (ref "D16") (pin "S2") (pinfunction "L2_S2") (pintype "passive"))
    )
    (net (code "296") (name "Net-(D17-PadD2)") (class "Default")
      (node (ref "D17") (pin "D2") (pinfunction "D2_D2") (pintype "passive"))
      (node (ref "D17") (pin "E2") (pinfunction "E2_E2") (pintype "passive"))
    )
    (net (code "297") (name "Net-(D17C-D2)") (class "Default")
      (node (ref "D17") (pin "R2") (pinfunction "E2_R2") (pintype "passive"))
      (node (ref "D17") (pin "S2") (pinfunction "D2_S2") (pintype "passive"))
    )
    (net (code "298") (name "PAR") (class "Default")
      (node (ref "A08") (pin "U1") (pinfunction "0_U1") (pintype "output"))
      (node (ref "A25") (pin "T1") (pinfunction "P$2_T1") (pintype "bidirectional"))
    )
    (net (code "299") (name "PC+ES") (class "Default")
      (node (ref "A11") (pin "H2") (pinfunction "IN_H2") (pintype "input"))
      (node (ref "A12") (pin "C1") (pinfunction "OUT_C1") (pintype "output"))
    )
    (net (code "300") (name "PWR_CLR") (class "Default")
      (node (ref "C06") (pin "R2") (pinfunction "OUT_R2") (pintype "output"))
    )
    (net (code "301") (name "RD+WD") (class "Default")
      (node (ref "A09") (pin "P1") (pinfunction "IN3_P1") (pintype "input"))
      (node (ref "B08") (pin "N2") (pinfunction "OUT_N2") (pintype "output"))
      (node (ref "B12") (pin "D2") (pinfunction "IN1_D2") (pintype "input"))
      (node (ref "C12") (pin "R1") (pinfunction "IN2_R1") (pintype "input"))
    )
    (net (code "302") (name "RDD_00") (class "Default")
      (node (ref "A21") (pin "U2") (pinfunction "U2_U2") (pintype "output"))
      (node (ref "B09") (pin "M2") (pinfunction "D_M2") (pintype "input"))
      (node (ref "D09") (pin "C1") (pinfunction "IN2A_C1") (pintype "input"))
      (node (ref "D09") (pin "F2") (pinfunction "IN2A_F2") (pintype "input"))
    )
    (net (code "303") (name "RDD_01") (class "Default")
      (node (ref "B09") (pin "P1") (pinfunction "D_P1") (pintype "input"))
      (node (ref "B20") (pin "U2") (pinfunction "U2_U2") (pintype "output"))
      (node (ref "D09") (pin "J1") (pinfunction "IN2A_J1") (pintype "input"))
      (node (ref "D09") (pin "M2") (pinfunction "IN2A_M2") (pintype "input"))
    )
    (net (code "304") (name "RDD_02") (class "Default")
      (node (ref "A20") (pin "U2") (pinfunction "U2_U2") (pintype "output"))
      (node (ref "B09") (pin "E2") (pinfunction "D_E2") (pintype "input"))
      (node (ref "D09") (pin "P1") (pinfunction "IN2A_P1") (pintype "input"))
      (node (ref "D09") (pin "T2") (pinfunction "IN2A_T2") (pintype "input"))
    )
    (net (code "305") (name "RDMK") (class "Default")
      (node (ref "B18") (pin "U2") (pinfunction "U2_U2") (pintype "output"))
      (node (ref "CD18") (pin "AS2") (pinfunction "AS2_AS2") (pintype "input"))
    )
    (net (code "306") (name "RD_EN") (class "Default")
      (node (ref "C11") (pin "J1") (pinfunction "IN2_J1") (pintype "input"))
      (node (ref "C11") (pin "N2") (pinfunction "OUT_N2") (pintype "output"))
    )
    (net (code "307") (name "RD_EN_LPB_00-02") (class "Default")
      (node (ref "C10") (pin "D2") (pinfunction "IN1A_D2") (pintype "input"))
      (node (ref "C13") (pin "T2") (pinfunction "OUT_T2") (pintype "output"))
      (node (ref "D09") (pin "D1") (pinfunction "IN2B_D1") (pintype "input"))
      (node (ref "D09") (pin "K1") (pinfunction "IN2B_K1") (pintype "input"))
      (node (ref "D09") (pin "R1") (pinfunction "IN2B_R1") (pintype "input"))
    )
    (net (code "308") (name "RD_EN_LPB_03-05") (class "Default")
      (node (ref "C10") (pin "R2") (pinfunction "IN1A_R2") (pintype "input"))
      (node (ref "C13") (pin "R2") (pinfunction "OUT_R2") (pintype "output"))
      (node (ref "D09") (pin "H2") (pinfunction "IN2B_H2") (pintype "input"))
      (node (ref "D09") (pin "N2") (pinfunction "IN2B_N2") (pintype "input"))
      (node (ref "D09") (pin "U2") (pinfunction "IN2B_U2") (pintype "input"))
    )
    (net (code "309") (name "READ_ALL") (class "Default")
      (node (ref "D07") (pin "N2") (pinfunction "O3_N2") (pintype "output"))
    )
    (net (code "310") (name "READ_DATA") (class "Default")
      (node (ref "A10") (pin "L1") (pinfunction "IN1_L1") (pintype "input"))
      (node (ref "C11") (pin "H1") (pinfunction "IN1_H1") (pintype "input"))
      (node (ref "D07") (pin "J2") (pinfunction "O2_J2") (pintype "output"))
    )
    (net (code "311") (name "RSTA") (class "Default")
      (node (ref "C04") (pin "A1") (pinfunction "A1_A1") (pintype "output"))
    )
    (net (code "312") (name "RSTB") (class "Default")
      (node (ref "C05") (pin "C1") (pinfunction "C1_C1") (pintype "output"))
    )
    (net (code "313") (name "SE") (class "Default")
      (node (ref "D07") (pin "L2") (pinfunction "O7_L2") (pintype "output"))
    )
    (net (code "314") (name "SEARCH") (class "Default")
      (node (ref "C11") (pin "D2") (pinfunction "IN1_D2") (pintype "input"))
      (node (ref "D07") (pin "E2") (pinfunction "O1_E2") (pintype "output"))
    )
    (net (code "315") (name "SEL") (class "Default")
      (node (ref "A08") (pin "H2") (pinfunction "1_H2") (pintype "output"))
      (node (ref "A25") (pin "S1") (pinfunction "P$2_S1") (pintype "bidirectional"))
    )
    (net (code "316") (name "SHIFT_CK") (class "Default")
      (node (ref "C17") (pin "K1") (pinfunction "OUT_K1") (pintype "output"))
      (node (ref "CD18") (pin "BR2") (pinfunction "BR2_BR2") (pintype "input"))
    )
    (net (code "317") (name "SH_DTB") (class "Default")
      (node (ref "A10") (pin "R2") (pinfunction "IN2_R2") (pintype "input"))
      (node (ref "B09") (pin "B1") (pinfunction "C_B1") (pintype "input"))
      (node (ref "B09") (pin "D2") (pinfunction "C_D2") (pintype "input"))
      (node (ref "B09") (pin "H1") (pinfunction "C_H1") (pintype "input"))
      (node (ref "B09") (pin "L2") (pinfunction "C_L2") (pintype "input"))
      (node (ref "B09") (pin "N1") (pinfunction "C_N1") (pintype "input"))
      (node (ref "B09") (pin "S2") (pinfunction "C_S2") (pintype "input"))
      (node (ref "B10") (pin "E1") (pinfunction "OUT_E1") (pintype "output"))
      (node (ref "C09") (pin "B1") (pinfunction "C_B1") (pintype "input"))
      (node (ref "C09") (pin "D2") (pinfunction "C_D2") (pintype "input"))
      (node (ref "C09") (pin "H1") (pinfunction "C_H1") (pintype "input"))
      (node (ref "C09") (pin "L2") (pinfunction "C_L2") (pintype "input"))
      (node (ref "C09") (pin "N1") (pinfunction "C_N1") (pintype "input"))
      (node (ref "C09") (pin "S2") (pinfunction "C_S2") (pintype "input"))
    )
    (net (code "318") (name "SH_EN") (class "Default")
      (node (ref "A11") (pin "N2") (pinfunction "OUT_N2") (pintype "output"))
      (node (ref "A12") (pin "E2") (pinfunction "IN2_E2") (pintype "input"))
      (node (ref "C10") (pin "A1") (pinfunction "IN1A_A1") (pintype "input"))
      (node (ref "C10") (pin "F1") (pinfunction "IN1A_F1") (pintype "input"))
      (node (ref "C10") (pin "M1") (pinfunction "IN1A_M1") (pintype "input"))
    )
    (net (code "319") (name "SH_ST") (class "Default")
      (node (ref "C17") (pin "A1") (pinfunction "IN_A1") (pintype "input"))
      (node (ref "CD18") (pin "AM1") (pinfunction "AM1_AM1") (pintype "output"))
    )
    (net (code "320") (name "SH_ST-B") (class "Default")
      (node (ref "C16") (pin "P2") (pinfunction "OUT_P2") (pintype "output"))
      (node (ref "CD18") (pin "BC1") (pinfunction "BC1_BC1") (pintype "input"))
    )
    (net (code "321") (name "SINGLE_UNIT") (class "Default")
      (node (ref "A09") (pin "K1") (pinfunction "IN4_K1") (pintype "input"))
      (node (ref "B21") (pin "U2") (pinfunction "OUT_U2") (pintype "output"))
    )
    (net (code "322") (name "SP_DY") (class "Default")
      (node (ref "D14") (pin "H2") (pinfunction "H2_H2") (pintype "output"))
    )
    (net (code "323") (name "ST_BLK_MK") (class "Default")
      (node (ref "A26") (pin "K1") (pinfunction "P$2_K1") (pintype "bidirectional"))
      (node (ref "C13") (pin "E2") (pinfunction "IN_E2") (pintype "input"))
      (node (ref "CD18") (pin "AR2") (pinfunction "AR2_AR2") (pintype "output"))
    )
    (net (code "324") (name "ST_CK") (class "Default")
      (node (ref "A10") (pin "P1") (pinfunction "IN1_P1") (pintype "input"))
      (node (ref "A26") (pin "P1") (pinfunction "P$2_P1") (pintype "bidirectional"))
      (node (ref "C13") (pin "J1") (pinfunction "IN_J1") (pintype "input"))
      (node (ref "CD18") (pin "BR1") (pinfunction "BR1_BR1") (pintype "output"))
      (node (ref "D17") (pin "M2") (pinfunction "K2_M2") (pintype "input"))
      (node (ref "D17") (pin "N2") (pinfunction "J2_N2") (pintype "input"))
      (node (ref "D17") (pin "P2") (pinfunction "H2_P2") (pintype "input"))
    )
    (net (code "325") (name "ST_CK_0P") (class "Default")
      (node (ref "B12") (pin "H2") (pinfunction "IN4_H2") (pintype "input"))
      (node (ref "C12") (pin "S1") (pinfunction "IN3_S1") (pintype "input"))
      (node (ref "C13") (pin "B1") (pinfunction "OUT_B1") (pintype "output"))
    )
    (net (code "326") (name "ST_DATA") (class "Default")
      (node (ref "B12") (pin "A1") (pinfunction "IN1_A1") (pintype "input"))
      (node (ref "C13") (pin "H2") (pinfunction "IN_H2") (pintype "input"))
      (node (ref "C16") (pin "J2") (pinfunction "OUT_J2") (pintype "output"))
    )
    (net (code "327") (name "ST_FINAL") (class "Default")
      (node (ref "A09") (pin "S2") (pinfunction "IN2_S2") (pintype "input"))
      (node (ref "A26") (pin "N1") (pinfunction "P$2_N1") (pintype "bidirectional"))
      (node (ref "C11") (pin "D1") (pinfunction "IN1_D1") (pintype "input"))
      (node (ref "C13") (pin "L1") (pinfunction "IN_L1") (pintype "input"))
      (node (ref "CD18") (pin "BL2") (pinfunction "BL2_BL2") (pintype "output"))
    )
    (net (code "328") (name "ST_IDLE") (class "Default")
      (node (ref "A26") (pin "R1") (pinfunction "P$2_R1") (pintype "bidirectional"))
      (node (ref "C13") (pin "K2") (pinfunction "IN_K2") (pintype "input"))
      (node (ref "CD18") (pin "BD2") (pinfunction "BD2_BD2") (pintype "input"))
    )
    (net (code "329") (name "ST_REV_CK") (class "Default")
      (node (ref "A26") (pin "L1") (pinfunction "P$2_L1") (pintype "bidirectional"))
      (node (ref "B11") (pin "S1") (pinfunction "IN3_S1") (pintype "input"))
      (node (ref "C11") (pin "A1") (pinfunction "IN1_A1") (pintype "input"))
      (node (ref "C13") (pin "D1") (pinfunction "IN_D1") (pintype "input"))
      (node (ref "CD18") (pin "BS1") (pinfunction "BS1_BS1") (pintype "output"))
      (node (ref "D12") (pin "F2") (pinfunction "IN3_F2") (pintype "input"))
      (node (ref "D12") (pin "H2") (pinfunction "IN4_H2") (pintype "input"))
    )
    (net (code "330") (name "SWTM") (class "Default")
      (node (ref "A26") (pin "V2") (pinfunction "P$2_V2") (pintype "bidirectional"))
      (node (ref "B06") (pin "P2") (pinfunction "IN_P2") (pintype "input"))
      (node (ref "B08") (pin "V1") (pinfunction "P$1_V1") (pintype "passive"))
      (node (ref "B11") (pin "B1") (pinfunction "IN2_B1") (pintype "input"))
      (node (ref "C10") (pin "N2") (pinfunction "IN2B_N2") (pintype "input"))
      (node (ref "C12") (pin "P2") (pinfunction "IN2_P2") (pintype "input"))
      (node (ref "C15") (pin "L1") (pinfunction "IN1_L1") (pintype "input"))
    )
    (net (code "331") (name "SYNC") (class "Default")
      (node (ref "B10") (pin "D2") (pinfunction "IN1_D2") (pintype "input"))
      (node (ref "B10") (pin "E2") (pinfunction "IN2_E2") (pintype "input"))
      (node (ref "CD18") (pin "BN2") (pinfunction "BN2_BN2") (pintype "output"))
    )
    (net (code "332") (name "SYNC_EN") (class "Default")
      (node (ref "B11") (pin "M2") (pinfunction "OUT_M2") (pintype "output"))
      (node (ref "CD18") (pin "BH1") (pinfunction "BH1_BH1") (pintype "input"))
    )
    (net (code "333") (name "T3") (class "Default")
      (node (ref "C17") (pin "S1") (pinfunction "OUT_S1") (pintype "output"))
      (node (ref "D12") (pin "N1") (pinfunction "IN2_N1") (pintype "input"))
      (node (ref "D12") (pin "P1") (pinfunction "IN3_P1") (pintype "input"))
    )
    (net (code "334") (name "TIM") (class "Default")
      (node (ref "A08") (pin "L1") (pinfunction "1_L1") (pintype "output"))
      (node (ref "A25") (pin "U1") (pinfunction "P$2_U1") (pintype "bidirectional"))
    )
    (net (code "335") (name "TM_EN") (class "Default")
      (node (ref "A18") (pin "R2") (pinfunction "R2_R2") (pintype "input"))
      (node (ref "B18") (pin "R2") (pinfunction "R2_R2") (pintype "input"))
      (node (ref "C13") (pin "N1") (pinfunction "IN_N1") (pintype "input"))
      (node (ref "C15") (pin "S1") (pinfunction "OUT_S1") (pintype "output"))
      (node (ref "C16") (pin "M1") (pinfunction "IN1_M1") (pintype "input"))
      (node (ref "C16") (pin "R2") (pinfunction "IN1_R2") (pintype "input"))
    )
    (net (code "336") (name "TP00") (class "Default")
      (node (ref "A08") (pin "B1") (pinfunction "C_B1") (pintype "input"))
      (node (ref "A15") (pin "L1") (pinfunction "OUT_L1") (pintype "output"))
      (node (ref "A16") (pin "M2") (pinfunction "K2_M2") (pintype "input"))
      (node (ref "A16") (pin "N2") (pinfunction "J2_N2") (pintype "input"))
      (node (ref "A16") (pin "P2") (pinfunction "H2_P2") (pintype "input"))
      (node (ref "B10") (pin "F2") (pinfunction "IN3_F2") (pintype "input"))
      (node (ref "B10") (pin "H2") (pinfunction "IN4_H2") (pintype "input"))
      (node (ref "B10") (pin "N1") (pinfunction "IN2_N1") (pintype "input"))
      (node (ref "B13") (pin "B1") (pinfunction "C_B1") (pintype "input"))
      (node (ref "B13") (pin "D2") (pinfunction "C_D2") (pintype "input"))
      (node (ref "B13") (pin "H1") (pinfunction "C_H1") (pintype "input"))
      (node (ref "B15") (pin "J1") (pinfunction "IN2_J1") (pintype "input"))
      (node (ref "C15") (pin "E1") (pinfunction "IN2_E1") (pintype "input"))
    )
    (net (code "337") (name "TP00_A") (class "Default")
      (node (ref "A15") (pin "S1") (pinfunction "OUT_S1") (pintype "output"))
      (node (ref "B10") (pin "H1") (pinfunction "IN2_H1") (pintype "input"))
      (node (ref "C12") (pin "E2") (pinfunction "IN2_E2") (pintype "input"))
    )
    (net (code "338") (name "TP01") (class "Default")
      (node (ref "A12") (pin "J2") (pinfunction "IN2_J2") (pintype "input"))
      (node (ref "A15") (pin "P2") (pinfunction "OUT_P2") (pintype "output"))
      (node (ref "B16") (pin "M2") (pinfunction "K2_M2") (pintype "input"))
      (node (ref "B16") (pin "N2") (pinfunction "J2_N2") (pintype "input"))
      (node (ref "B16") (pin "P2") (pinfunction "H2_P2") (pintype "input"))
      (node (ref "C11") (pin "J2") (pinfunction "IN2_J2") (pintype "input"))
      (node (ref "C15") (pin "B1") (pinfunction "IN2_B1") (pintype "input"))
      (node (ref "CD18") (pin "BF1") (pinfunction "BF1_BF1") (pintype "input"))
    )
    (net (code "339") (name "TP01_A") (class "Default")
      (node (ref "A15") (pin "V2") (pinfunction "OUT_V2") (pintype "output"))
      (node (ref "B12") (pin "T2") (pinfunction "IN3_T2") (pintype "input"))
      (node (ref "C15") (pin "M2") (pinfunction "IN2_M2") (pintype "input"))
    )
    (net (code "340") (name "T_TRK") (class "Default")
      (node (ref "A18") (pin "U2") (pinfunction "U2_U2") (pintype "output"))
      (node (ref "B15") (pin "E2") (pinfunction "IN2_E2") (pintype "input"))
      (node (ref "C15") (pin "R2") (pinfunction "IN2_R2") (pintype "input"))
      (node (ref "D14") (pin "S1") (pinfunction "S1_S1") (pintype "input"))
      (node (ref "D14") (pin "U1") (pinfunction "U1_U1") (pintype "input"))
    )
    (net (code "341") (name "U+M_DY") (class "Default")
      (node (ref "D14") (pin "K1") (pinfunction "H2_K1") (pintype "output"))
    )
    (net (code "342") (name "USR_00") (class "Default")
      (node (ref "A07") (pin "V2") (pinfunction "IN2_V2") (pintype "input"))
      (node (ref "A25") (pin "A1") (pinfunction "P$2_A1") (pintype "bidirectional"))
      (node (ref "B07") (pin "E1") (pinfunction "E1_E1") (pintype "output"))
    )
    (net (code "343") (name "USR_01") (class "Default")
      (node (ref "A07") (pin "U2") (pinfunction "IN1_U2") (pintype "input"))
      (node (ref "A25") (pin "B1") (pinfunction "P$2_B1") (pintype "bidirectional"))
      (node (ref "B07") (pin "H2") (pinfunction "H2_H2") (pintype "output"))
    )
    (net (code "344") (name "USR_02") (class "Default")
      (node (ref "A07") (pin "V1") (pinfunction "IN0_V1") (pintype "input"))
      (node (ref "A25") (pin "C1") (pinfunction "P$2_C1") (pintype "bidirectional"))
      (node (ref "B07") (pin "L1") (pinfunction "L1_L1") (pintype "output"))
    )
    (net (code "345") (name "UTS") (class "Default")
      (node (ref "A10") (pin "E1") (pinfunction "IN2_E1") (pintype "input"))
      (node (ref "A26") (pin "J1") (pinfunction "P$2_J1") (pintype "bidirectional"))
      (node (ref "B15") (pin "P1") (pinfunction "IN1_P1") (pintype "input"))
      (node (ref "C14") (pin "R2") (pinfunction "0_R2") (pintype "output"))
    )
    (net (code "346") (name "VCC") (class "Default")
      (node (ref "AB01") (pin "AA2") (pinfunction "VCC_AA2") (pintype "power_in"))
      (node (ref "AB01") (pin "AB1") (pinfunction "VCC_AB1") (pintype "power_in"))
      (node (ref "AB01") (pin "AC1") (pinfunction "VCC_AC1") (pintype "power_in"))
      (node (ref "AB01") (pin "AD1") (pinfunction "VCC_AD1") (pintype "power_in"))
      (node (ref "AB01") (pin "AE1") (pinfunction "VCC_AE1") (pintype "power_in"))
      (node (ref "AB01") (pin "AF1") (pinfunction "VCC_AF1") (pintype "power_in"))
      (node (ref "AB01") (pin "AH1") (pinfunction "VCC_AH1") (pintype "power_in"))
      (node (ref "AB01") (pin "AJ1") (pinfunction "VCC_AJ1") (pintype "power_in"))
      (node (ref "AB01") (pin "AK1") (pinfunction "VCC_AK1") (pintype "power_in"))
      (node (ref "AB01") (pin "AL1") (pinfunction "VCC_AL1") (pintype "power_in"))
      (node (ref "AB01") (pin "BA2") (pinfunction "VCC_BA2") (pintype "power_in"))
      (node (ref "AB01") (pin "BB1") (pinfunction "VCC_BB1") (pintype "power_in"))
      (node (ref "AB01") (pin "BC1") (pinfunction "VCC_BC1") (pintype "power_in"))
      (node (ref "AB01") (pin "BD1") (pinfunction "VCC_BD1") (pintype "power_in"))
      (node (ref "AB01") (pin "BE1") (pinfunction "VCC_BE1") (pintype "power_in"))
    )
    (net (code "347") (name "W+UTS") (class "Default")
      (node (ref "A15") (pin "A1") (pinfunction "IN1_A1") (pintype "input"))
      (node (ref "A15") (pin "H2") (pinfunction "IN4_H2") (pintype "input"))
      (node (ref "C12") (pin "M2") (pinfunction "OUT_M2") (pintype "output"))
    )
    (net (code "348") (name "W-INH") (class "Default")
      (node (ref "A08") (pin "V1") (pinfunction "0_V1") (pintype "output"))
    )
    (net (code "349") (name "W01") (class "Default")
      (node (ref "A26") (pin "J2") (pinfunction "P$2_J2") (pintype "bidirectional"))
      (node (ref "CD18") (pin "BJ2") (pinfunction "BJ2_BJ2") (pintype "output"))
    )
    (net (code "350") (name "W01-W05") (class "Default")
      (node (ref "CD18") (pin "AK1") (pinfunction "AK1_AK1") (pintype "output"))
    )
    (net (code "351") (name "W02") (class "Default")
      (node (ref "A26") (pin "K2") (pinfunction "P$2_K2") (pintype "bidirectional"))
      (node (ref "CD18") (pin "BV2") (pinfunction "BV2_BV2") (pintype "output"))
    )
    (net (code "352") (name "W03") (class "Default")
      (node (ref "A26") (pin "L2") (pinfunction "P$2_L2") (pintype "bidirectional"))
      (node (ref "CD18") (pin "BE2") (pinfunction "BE2_BE2") (pintype "output"))
    )
    (net (code "353") (name "W04") (class "Default")
      (node (ref "A26") (pin "M2") (pinfunction "P$2_M2") (pintype "bidirectional"))
      (node (ref "CD18") (pin "AT2") (pinfunction "AT2_AT2") (pintype "output"))
    )
    (net (code "354") (name "W05") (class "Default")
      (node (ref "A26") (pin "N2") (pinfunction "P$2_N2") (pintype "bidirectional"))
      (node (ref "CD18") (pin "BU2") (pinfunction "BU2_BU2") (pintype "output"))
    )
    (net (code "355") (name "W06") (class "Default")
      (node (ref "A26") (pin "P2") (pinfunction "P$2_P2") (pintype "bidirectional"))
      (node (ref "CD18") (pin "AM2") (pinfunction "AM2_AM2") (pintype "output"))
    )
    (net (code "356") (name "W07") (class "Default")
      (node (ref "A26") (pin "R2") (pinfunction "P$2_R2") (pintype "bidirectional"))
      (node (ref "CD18") (pin "AK2") (pinfunction "AK2_AK2") (pintype "output"))
    )
    (net (code "357") (name "W08") (class "Default")
      (node (ref "A26") (pin "S2") (pinfunction "P$2_S2") (pintype "bidirectional"))
      (node (ref "CD18") (pin "AL1") (pinfunction "AL1_AL1") (pintype "output"))
    )
    (net (code "358") (name "W09") (class "Default")
      (node (ref "A26") (pin "T2") (pinfunction "P$2_T2") (pintype "bidirectional"))
      (node (ref "CD18") (pin "BF2") (pinfunction "BF2_BF2") (pintype "output"))
    )
    (net (code "359") (name "WB00") (class "Default")
      (node (ref "A21") (pin "N2") (pinfunction "N2_N2") (pintype "input"))
      (node (ref "A25") (pin "P2") (pinfunction "P$2_P2") (pintype "bidirectional"))
      (node (ref "B18") (pin "N2") (pinfunction "N2_N2") (pintype "input"))
      (node (ref "C14") (pin "F1") (pinfunction "0_F1") (pintype "output"))
      (node (ref "D09") (pin "A1") (pinfunction "IN1A_A1") (pintype "input"))
    )
    (net (code "360") (name "WB01") (class "Default")
      (node (ref "A25") (pin "R2") (pinfunction "P$2_R2") (pintype "bidirectional"))
      (node (ref "B20") (pin "N2") (pinfunction "N2_N2") (pintype "input"))
      (node (ref "C14") (pin "J2") (pinfunction "0_J2") (pintype "output"))
      (node (ref "D09") (pin "F1") (pinfunction "IN1A_F1") (pintype "input"))
    )
    (net (code "361") (name "WB02") (class "Default")
      (node (ref "A20") (pin "N2") (pinfunction "N2_N2") (pintype "input"))
      (node (ref "A25") (pin "S2") (pinfunction "P$2_S2") (pintype "bidirectional"))
      (node (ref "C14") (pin "M1") (pinfunction "0_M1") (pintype "output"))
      (node (ref "D09") (pin "M1") (pinfunction "IN1A_M1") (pintype "input"))
    )
    (net (code "362") (name "WC") (class "Default")
      (node (ref "A26") (pin "H1") (pinfunction "P$2_H1") (pintype "bidirectional"))
      (node (ref "B10") (pin "M1") (pinfunction "IN1_M1") (pintype "input"))
      (node (ref "B11") (pin "K1") (pinfunction "IN1_K1") (pintype "input"))
      (node (ref "D11") (pin "S1") (pinfunction "1_S1") (pintype "output"))
    )
    (net (code "363") (name "WC0") (class "Default")
      (node (ref "C01") (pin "H1") (pinfunction "OUT_H1") (pintype "output"))
      (node (ref "C06") (pin "M2") (pinfunction "IN_M2") (pintype "input"))
    )
    (net (code "364") (name "WRITE_ALL") (class "Default")
      (node (ref "A08") (pin "S2") (pinfunction "C_S2") (pintype "input"))
      (node (ref "B11") (pin "M1") (pinfunction "IN3_M1") (pintype "input"))
      (node (ref "B12") (pin "F1") (pinfunction "IN1_F1") (pintype "input"))
      (node (ref "D07") (pin "M2") (pinfunction "O5_M2") (pintype "output"))
    )
    (net (code "365") (name "WRITE_DATA") (class "Default")
      (node (ref "A09") (pin "R2") (pinfunction "IN1_R2") (pintype "input"))
      (node (ref "B11") (pin "R1") (pinfunction "IN2_R1") (pintype "input"))
      (node (ref "B12") (pin "B1") (pinfunction "IN2_B1") (pintype "input"))
      (node (ref "B12") (pin "P1") (pinfunction "IN3_P1") (pintype "input"))
      (node (ref "D07") (pin "F2") (pinfunction "O4_F2") (pintype "output"))
    )
    (net (code "366") (name "WRITE_OK") (class "Default")
      (node (ref "A22") (pin "D2") (pinfunction "D2_D2") (pintype "output"))
      (node (ref "B11") (pin "C1") (pinfunction "IN3_C1") (pintype "input"))
      (node (ref "B15") (pin "R1") (pinfunction "IN2_R1") (pintype "input"))
      (node (ref "C17") (pin "H2") (pinfunction "IN_H2") (pintype "input"))
    )
    (net (code "367") (name "WRITE_OK+UTS") (class "Default")
      (node (ref "B12") (pin "D1") (pinfunction "IN4_D1") (pintype "input"))
      (node (ref "B12") (pin "K1") (pinfunction "IN4_K1") (pintype "input"))
      (node (ref "C17") (pin "M1") (pinfunction "OUT_M1") (pintype "output"))
    )
    (net (code "368") (name "WRTM") (class "Default")
      (node (ref "B11") (pin "A1") (pinfunction "IN1_A1") (pintype "input"))
      (node (ref "C10") (pin "K2") (pinfunction "IN1A_K2") (pintype "input"))
      (node (ref "C12") (pin "N2") (pinfunction "IN1_N2") (pintype "input"))
      (node (ref "D07") (pin "H2") (pinfunction "O6_H2") (pintype "output"))
    )
    (net (code "369") (name "WRTM+FR03") (class "Default")
      (node (ref "B08") (pin "K2") (pinfunction "OUT_K2") (pintype "output"))
      (node (ref "C12") (pin "M1") (pinfunction "IN3_M1") (pintype "input"))
      (node (ref "C12") (pin "V2") (pinfunction "IN3_V2") (pintype "input"))
    )
    (net (code "370") (name "WR_EN") (class "Default")
      (node (ref "A20") (pin "R2") (pinfunction "R2_R2") (pintype "input"))
      (node (ref "A21") (pin "R2") (pinfunction "R2_R2") (pintype "input"))
      (node (ref "A26") (pin "F1") (pinfunction "P$2_F1") (pintype "bidirectional"))
      (node (ref "B20") (pin "R2") (pinfunction "R2_R2") (pintype "input"))
      (node (ref "C10") (pin "H2") (pinfunction "IN2B_H2") (pintype "input"))
      (node (ref "C10") (pin "U2") (pinfunction "IN2B_U2") (pintype "input"))
      (node (ref "C12") (pin "D2") (pinfunction "IN1_D2") (pintype "input"))
      (node (ref "C14") (pin "U1") (pinfunction "0_U1") (pintype "output"))
      (node (ref "C15") (pin "A1") (pinfunction "IN1_A1") (pintype "input"))
      (node (ref "C15") (pin "M1") (pinfunction "IN2_M1") (pintype "input"))
      (node (ref "D09") (pin "B1") (pinfunction "IN1B_B1") (pintype "input"))
      (node (ref "D09") (pin "E2") (pinfunction "IN1B_E2") (pintype "input"))
      (node (ref "D09") (pin "H1") (pinfunction "IN1B_H1") (pintype "input"))
      (node (ref "D09") (pin "L2") (pinfunction "IN1B_L2") (pintype "input"))
      (node (ref "D09") (pin "N1") (pinfunction "IN1B_N1") (pintype "input"))
      (node (ref "D09") (pin "S2") (pinfunction "IN1B_S2") (pintype "input"))
    )
    (net (code "371") (name "XOR_TO_LPB") (class "Default")
      (node (ref "C10") (pin "E2") (pinfunction "IN1B_E2") (pintype "input"))
      (node (ref "C10") (pin "F2") (pinfunction "IN2A_F2") (pintype "input"))
      (node (ref "C10") (pin "S2") (pinfunction "IN1B_S2") (pintype "input"))
      (node (ref "C10") (pin "T2") (pinfunction "IN2A_T2") (pintype "input"))
      (node (ref "D12") (pin "P2") (pinfunction "OUT_P2") (pintype "output"))
    )
    (net (code "372") (name "XSAD") (class "Default")
      (node (ref "A09") (pin "R1") (pinfunction "IN4_R1") (pintype "input"))
      (node (ref "A11") (pin "L2") (pinfunction "OUT_L2") (pintype "output"))
    )
    (net (code "373") (name "XSA_DY") (class "Default")
      (node (ref "A08") (pin "D2") (pinfunction "C_D2") (pintype "input"))
      (node (ref "B14") (pin "B1") (pinfunction "C_B1") (pintype "input"))
      (node (ref "B14") (pin "L2") (pinfunction "C_L2") (pintype "input"))
      (node (ref "C17") (pin "T2") (pinfunction "OUT_T2") (pintype "output"))
    )
    (net (code "374") (name "XSTA") (class "Default")
      (node (ref "B07") (pin "B1") (pinfunction "B1_B1") (pintype "input"))
      (node (ref "B07") (pin "D2") (pinfunction "D2_D2") (pintype "input"))
      (node (ref "B07") (pin "H1") (pinfunction "H1_H1") (pintype "input"))
      (node (ref "B07") (pin "L2") (pinfunction "L2_L2") (pintype "input"))
      (node (ref "B07") (pin "N1") (pinfunction "N1_N1") (pintype "input"))
      (node (ref "B07") (pin "S2") (pinfunction "S2_S2") (pintype "input"))
      (node (ref "C04") (pin "E1") (pinfunction "E1_E1") (pintype "output"))
      (node (ref "C07") (pin "B1") (pinfunction "B1_B1") (pintype "input"))
      (node (ref "C07") (pin "D2") (pinfunction "D2_D2") (pintype "input"))
      (node (ref "C07") (pin "H1") (pinfunction "H1_H1") (pintype "input"))
      (node (ref "C07") (pin "L2") (pinfunction "L2_L2") (pintype "input"))
      (node (ref "D11") (pin "N1") (pinfunction "C_N1") (pintype "input"))
      (node (ref "D13") (pin "M2") (pinfunction "K2_M2") (pintype "input"))
      (node (ref "D13") (pin "N2") (pinfunction "J2_N2") (pintype "input"))
      (node (ref "D13") (pin "P2") (pinfunction "H2_P2") (pintype "input"))
    )
    (net (code "375") (name "unconnected-(A07A-O8-PadP2)") (class "Default")
      (node (ref "A07") (pin "P2") (pinfunction "O8_P2") (pintype "output"))
    )
    (net (code "376") (name "unconnected-(A07A-O9-PadR2)") (class "Default")
      (node (ref "A07") (pin "R2") (pinfunction "O9_R2") (pintype "output"))
    )
    (net (code "377") (name "unconnected-(A07A-~{O8}-PadP1)") (class "Default")
      (node (ref "A07") (pin "P1") (pinfunction "~{O8}_P1") (pintype "output"))
    )
    (net (code "378") (name "unconnected-(A07A-~{O9}-PadR1)") (class "Default")
      (node (ref "A07") (pin "R1") (pinfunction "~{O9}_R1") (pintype "output"))
    )
    (net (code "379") (name "unconnected-(A14-PadD1)") (class "Default")
      (node (ref "A14") (pin "D1") (pinfunction "D1_D1") (pintype "passive"))
    )
    (net (code "380") (name "unconnected-(A14-PadE1)") (class "Default")
      (node (ref "A14") (pin "E1") (pinfunction "E1_E1") (pintype "passive"))
    )
    (net (code "381") (name "unconnected-(A14-PadF1)") (class "Default")
      (node (ref "A14") (pin "F1") (pinfunction "F1_F1") (pintype "passive"))
    )
    (net (code "382") (name "unconnected-(A14-PadJ1)") (class "Default")
      (node (ref "A14") (pin "J1") (pinfunction "J1_J1") (pintype "passive"))
    )
    (net (code "383") (name "unconnected-(A14D-D1-PadN1)") (class "Default")
      (node (ref "A14") (pin "N1") (pinfunction "D1_N1") (pintype "passive"))
    )
    (net (code "384") (name "unconnected-(A14D-E1-PadP1)") (class "Default")
      (node (ref "A14") (pin "P1") (pinfunction "E1_P1") (pintype "passive"))
    )
    (net (code "385") (name "unconnected-(A14D-F1-PadR1)") (class "Default")
      (node (ref "A14") (pin "R1") (pinfunction "F1_R1") (pintype "passive"))
    )
    (net (code "386") (name "unconnected-(A14D-J1-PadU1)") (class "Default")
      (node (ref "A14") (pin "U1") (pinfunction "J1_U1") (pintype "passive"))
    )
    (net (code "387") (name "unconnected-(A18-PadH2)") (class "Default")
      (node (ref "A18") (pin "H2") (pinfunction "H2_H2") (pintype "input"))
    )
    (net (code "388") (name "unconnected-(A18-PadL2)") (class "Default")
      (node (ref "A18") (pin "L2") (pinfunction "L2_L2") (pintype "input"))
    )
    (net (code "389") (name "unconnected-(A18-PadM2)") (class "Default")
      (node (ref "A18") (pin "M2") (pinfunction "M2_M2") (pintype "input"))
    )
    (net (code "390") (name "unconnected-(A20-PadH2)") (class "Default")
      (node (ref "A20") (pin "H2") (pinfunction "H2_H2") (pintype "input"))
    )
    (net (code "391") (name "unconnected-(A20-PadL2)") (class "Default")
      (node (ref "A20") (pin "L2") (pinfunction "L2_L2") (pintype "input"))
    )
    (net (code "392") (name "unconnected-(A20-PadM2)") (class "Default")
      (node (ref "A20") (pin "M2") (pinfunction "M2_M2") (pintype "input"))
    )
    (net (code "393") (name "unconnected-(A21-PadH2)") (class "Default")
      (node (ref "A21") (pin "H2") (pinfunction "H2_H2") (pintype "input"))
    )
    (net (code "394") (name "unconnected-(A21-PadL2)") (class "Default")
      (node (ref "A21") (pin "L2") (pinfunction "L2_L2") (pintype "input"))
    )
    (net (code "395") (name "unconnected-(A21-PadM2)") (class "Default")
      (node (ref "A21") (pin "M2") (pinfunction "M2_M2") (pintype "input"))
    )
    (net (code "396") (name "unconnected-(A22-PadE2)") (class "Default")
      (node (ref "A22") (pin "E2") (pinfunction "E2_E2") (pintype "passive"))
    )
    (net (code "397") (name "unconnected-(AB01-PadBM1)") (class "Default")
      (node (ref "AB01") (pin "BM1") (pinfunction "BM1_BM1") (pintype "output"))
    )
    (net (code "398") (name "unconnected-(AB01-PadBN1)") (class "Default")
      (node (ref "AB01") (pin "BN1") (pinfunction "BN1_BN1") (pintype "input"))
    )
    (net (code "399") (name "unconnected-(AB01-PadBP1)") (class "Default")
      (node (ref "AB01") (pin "BP1") (pinfunction "BP1_BP1") (pintype "input"))
    )
    (net (code "400") (name "unconnected-(AB01-PadBR1)") (class "Default")
      (node (ref "AB01") (pin "BR1") (pinfunction "BR1_BR1") (pintype "output"))
    )
    (net (code "401") (name "unconnected-(B05H-B-PadL2)") (class "Default")
      (node (ref "B05") (pin "L2") (pinfunction "B_L2") (pintype "input"))
    )
    (net (code "402") (name "unconnected-(B05H-E-PadP2)") (class "Default")
      (node (ref "B05") (pin "P2") (pinfunction "E_P2") (pintype "open_collector"))
    )
    (net (code "403") (name "unconnected-(B18-PadH2)") (class "Default")
      (node (ref "B18") (pin "H2") (pinfunction "H2_H2") (pintype "input"))
    )
    (net (code "404") (name "unconnected-(B18-PadL2)") (class "Default")
      (node (ref "B18") (pin "L2") (pinfunction "L2_L2") (pintype "input"))
    )
    (net (code "405") (name "unconnected-(B18-PadM2)") (class "Default")
      (node (ref "B18") (pin "M2") (pinfunction "M2_M2") (pintype "input"))
    )
    (net (code "406") (name "unconnected-(B20-PadH2)") (class "Default")
      (node (ref "B20") (pin "H2") (pinfunction "H2_H2") (pintype "input"))
    )
    (net (code "407") (name "unconnected-(B20-PadL2)") (class "Default")
      (node (ref "B20") (pin "L2") (pinfunction "L2_L2") (pintype "input"))
    )
    (net (code "408") (name "unconnected-(B20-PadM2)") (class "Default")
      (node (ref "B20") (pin "M2") (pinfunction "M2_M2") (pintype "input"))
    )
    (net (code "409") (name "unconnected-(B22K-A-PadR2)") (class "Default")
      (node (ref "B22") (pin "R2") (pinfunction "A_R2") (pintype "input"))
    )
    (net (code "410") (name "unconnected-(B22K-D-PadU2)") (class "Default")
      (node (ref "B22") (pin "U2") (pinfunction "D_U2") (pintype "output"))
    )
    (net (code "411") (name "unconnected-(C02A-IN13-PadP2)") (class "Default")
      (node (ref "C02") (pin "P2") (pinfunction "IN13_P2") (pintype "input"))
    )
    (net (code "412") (name "unconnected-(C02A-IN14-PadS2)") (class "Default")
      (node (ref "C02") (pin "S2") (pinfunction "IN14_S2") (pintype "input"))
    )
    (net (code "413") (name "unconnected-(C02A-O13-PadR2)") (class "Default")
      (node (ref "C02") (pin "R2") (pinfunction "O13_R2") (pintype "output"))
    )
    (net (code "414") (name "unconnected-(C02A-O14-PadT2)") (class "Default")
      (node (ref "C02") (pin "T2") (pinfunction "O14_T2") (pintype "output"))
    )
    (net (code "415") (name "unconnected-(C03A-IN13-PadP2)") (class "Default")
      (node (ref "C03") (pin "P2") (pinfunction "IN13_P2") (pintype "input"))
    )
    (net (code "416") (name "unconnected-(C03A-IN14-PadS2)") (class "Default")
      (node (ref "C03") (pin "S2") (pinfunction "IN14_S2") (pintype "input"))
    )
    (net (code "417") (name "unconnected-(C03A-IN15-PadU2)") (class "Default")
      (node (ref "C03") (pin "U2") (pinfunction "IN15_U2") (pintype "input"))
    )
    (net (code "418") (name "unconnected-(C03A-O13-PadR2)") (class "Default")
      (node (ref "C03") (pin "R2") (pinfunction "O13_R2") (pintype "output"))
    )
    (net (code "419") (name "unconnected-(C03A-O14-PadT2)") (class "Default")
      (node (ref "C03") (pin "T2") (pinfunction "O14_T2") (pintype "output"))
    )
    (net (code "420") (name "unconnected-(C03A-O15-PadV2)") (class "Default")
      (node (ref "C03") (pin "V2") (pinfunction "O15_V2") (pintype "output"))
    )
    (net (code "421") (name "unconnected-(C07-PadN1)") (class "Default")
      (node (ref "C07") (pin "N1") (pinfunction "N1_N1") (pintype "input"))
    )
    (net (code "422") (name "unconnected-(C07-PadP1)") (class "Default")
      (node (ref "C07") (pin "P1") (pinfunction "P1_P1") (pintype "input"))
    )
    (net (code "423") (name "unconnected-(C07-PadR1)") (class "Default")
      (node (ref "C07") (pin "R1") (pinfunction "R1_R1") (pintype "input"))
    )
    (net (code "424") (name "unconnected-(C07-PadS1)") (class "Default")
      (node (ref "C07") (pin "S1") (pinfunction "S1_S1") (pintype "output"))
    )
    (net (code "425") (name "unconnected-(C07-PadS2)") (class "Default")
      (node (ref "C07") (pin "S2") (pinfunction "S2_S2") (pintype "input"))
    )
    (net (code "426") (name "unconnected-(C07-PadT2)") (class "Default")
      (node (ref "C07") (pin "T2") (pinfunction "T2_T2") (pintype "input"))
    )
    (net (code "427") (name "unconnected-(C07-PadU1)") (class "Default")
      (node (ref "C07") (pin "U1") (pinfunction "U1_U1") (pintype "output"))
    )
    (net (code "428") (name "unconnected-(C07-PadU2)") (class "Default")
      (node (ref "C07") (pin "U2") (pinfunction "U2_U2") (pintype "input"))
    )
    (net (code "429") (name "unconnected-(C07-PadV1)") (class "Default")
      (node (ref "C07") (pin "V1") (pinfunction "V1_V1") (pintype "output"))
    )
    (net (code "430") (name "unconnected-(C07-PadV2)") (class "Default")
      (node (ref "C07") (pin "V2") (pinfunction "V2_V2") (pintype "output"))
    )
    (net (code "431") (name "unconnected-(CD18-PadAN2)") (class "Default")
      (node (ref "CD18") (pin "AN2") (pinfunction "AN2_AN2") (pintype "output"))
    )
    (net (code "432") (name "unconnected-(CD18-PadAU1)") (class "Default")
      (node (ref "CD18") (pin "AU1") (pinfunction "AU1_AU1") (pintype "output"))
    )
    (net (code "433") (name "unconnected-(D07A-O8-PadP2)") (class "Default")
      (node (ref "D07") (pin "P2") (pinfunction "O8_P2") (pintype "output"))
    )
    (net (code "434") (name "unconnected-(D07A-O9-PadR2)") (class "Default")
      (node (ref "D07") (pin "R2") (pinfunction "O9_R2") (pintype "output"))
    )
    (net (code "435") (name "unconnected-(D07A-~{O8}-PadP1)") (class "Default")
      (node (ref "D07") (pin "P1") (pinfunction "~{O8}_P1") (pintype "output"))
    )
    (net (code "436") (name "unconnected-(D07A-~{O9}-PadR1)") (class "Default")
      (node (ref "D07") (pin "R1") (pinfunction "~{O9}_R1") (pintype "output"))
    )
    (net (code "437") (name "unconnected-(D13-PadD2)") (class "Default")
      (node (ref "D13") (pin "D2") (pinfunction "D2_D2") (pintype "passive"))
    )
    (net (code "438") (name "unconnected-(D13-PadE2)") (class "Default")
      (node (ref "D13") (pin "E2") (pinfunction "E2_E2") (pintype "passive"))
    )
    (net (code "439") (name "unconnected-(D14-PadN2)") (class "Default")
      (node (ref "D14") (pin "N2") (pinfunction "N2_N2") (pintype "passive"))
    )
    (net (code "440") (name "unconnected-(D14-PadP2)") (class "Default")
      (node (ref "D14") (pin "P2") (pinfunction "P2_P2") (pintype "passive"))
    )
    (net (code "441") (name "unconnected-(D14-PadR2)") (class "Default")
      (node (ref "D14") (pin "R2") (pinfunction "R2_R2") (pintype "passive"))
    )
    (net (code "442") (name "unconnected-(D14-PadS2)") (class "Default")
      (node (ref "D14") (pin "S2") (pinfunction "S2_S2") (pintype "passive"))
    )
    (net (code "443") (name "unconnected-(D14-PadU2)") (class "Default")
      (node (ref "D14") (pin "U2") (pinfunction "U2_U2") (pintype "passive"))
    )
    (net (code "444") (name "unconnected-(D14E-N2-PadJ1)") (class "Default")
      (node (ref "D14") (pin "J1") (pinfunction "N2_J1") (pintype "passive"))
    )
    (net (code "445") (name "unconnected-(D14E-R2-PadF1)") (class "Default")
      (node (ref "D14") (pin "F1") (pinfunction "R2_F1") (pintype "passive"))
    )
    (net (code "446") (name "unconnected-(D14E-S2-PadE1)") (class "Default")
      (node (ref "D14") (pin "E1") (pinfunction "S2_E1") (pintype "passive"))
    )
    (net (code "447") (name "unconnected-(D14E-U2-PadD1)") (class "Default")
      (node (ref "D14") (pin "D1") (pinfunction "U2_D1") (pintype "passive"))
    )
    (net (code "448") (name "unconnected-(D14E-V2-PadB1)") (class "Default")
      (node (ref "D14") (pin "B1") (pinfunction "V2_B1") (pintype "passive"))
    )
    (net (code "449") (name "unconnected-(D15-PadE2)") (class "Default")
      (node (ref "D15") (pin "E2") (pinfunction "E2_E2") (pintype "output"))
    )
    (net (code "450") (name "unconnected-(D15-PadM2)") (class "Default")
      (node (ref "D15") (pin "M2") (pinfunction "M2_M2") (pintype "passive"))
    )
    (net (code "451") (name "unconnected-(D15-PadP2)") (class "Default")
      (node (ref "D15") (pin "P2") (pinfunction "P2_P2") (pintype "passive"))
    )
    (net (code "452") (name "unconnected-(D15-PadR2)") (class "Default")
      (node (ref "D15") (pin "R2") (pinfunction "R2_R2") (pintype "passive"))
    )
    (net (code "453") (name "unconnected-(D15-PadT2)") (class "Default")
      (node (ref "D15") (pin "T2") (pinfunction "T2_T2") (pintype "passive"))
    )
    (net (code "454") (name "unconnected-(D16D-D1-PadN1)") (class "Default")
      (node (ref "D16") (pin "N1") (pinfunction "D1_N1") (pintype "passive"))
    )
    (net (code "455") (name "unconnected-(D16D-E1-PadP1)") (class "Default")
      (node (ref "D16") (pin "P1") (pinfunction "E1_P1") (pintype "passive"))
    )
    (net (code "456") (name "unconnected-(D16D-F1-PadR1)") (class "Default")
      (node (ref "D16") (pin "R1") (pinfunction "F1_R1") (pintype "passive"))
    )
    (net (code "457") (name "unconnected-(D16D-J1-PadU1)") (class "Default")
      (node (ref "D16") (pin "U1") (pinfunction "J1_U1") (pintype "passive"))
    )
    (net (code "458") (name "~{0_TO_AC}") (class "Default")
      (node (ref "B05") (pin "H1") (pinfunction "B_H1") (pintype "input"))
      (node (ref "B06") (pin "T2") (pinfunction "OUT_T2") (pintype "output"))
    )
    (net (code "459") (name "~{0_TO_DTB}") (class "Default")
      (node (ref "A11") (pin "L1") (pinfunction "IN_L1") (pintype "input"))
      (node (ref "B09") (pin "A1") (pinfunction "R_A1") (pintype "input"))
      (node (ref "B09") (pin "K2") (pinfunction "R_K2") (pintype "input"))
      (node (ref "B10") (pin "L1") (pinfunction "OUT_L1") (pintype "output"))
      (node (ref "C09") (pin "A1") (pinfunction "R_A1") (pintype "input"))
      (node (ref "C09") (pin "K2") (pinfunction "R_K2") (pintype "input"))
    )
    (net (code "460") (name "~{0_TO_EF}") (class "Default")
      (node (ref "A08") (pin "A1") (pinfunction "R_A1") (pintype "input"))
      (node (ref "A08") (pin "N2") (pinfunction "S_N2") (pintype "input"))
      (node (ref "A08") (pin "R1") (pinfunction "S_R1") (pintype "input"))
      (node (ref "A11") (pin "F2") (pinfunction "OUT_F2") (pintype "output"))
    )
    (net (code "461") (name "~{0_TO_LPB}") (class "Default")
      (node (ref "D08") (pin "A1") (pinfunction "A1_A1") (pintype "input"))
      (node (ref "D08") (pin "K2") (pinfunction "K2_K2") (pintype "input"))
      (node (ref "D12") (pin "J2") (pinfunction "OUT_J2") (pintype "output"))
    )
    (net (code "462") (name "~{0_TO_STATE}") (class "Default")
      (node (ref "C16") (pin "L1") (pinfunction "OUT_L1") (pintype "output"))
      (node (ref "CD18") (pin "AV2") (pinfunction "AV2_AV2") (pintype "input"))
    )
    (net (code "463") (name "~{0_TO_STA}") (class "Default")
      (node (ref "A11") (pin "P1") (pinfunction "OUT_P1") (pintype "output"))
      (node (ref "B07") (pin "A1") (pinfunction "A1_A1") (pintype "input"))
      (node (ref "B07") (pin "K2") (pinfunction "K2_K2") (pintype "input"))
      (node (ref "B11") (pin "P2") (pinfunction "IN2_P2") (pintype "input"))
      (node (ref "C07") (pin "A1") (pinfunction "A1_A1") (pintype "input"))
    )
    (net (code "464") (name "~{0_TO_W}") (class "Default")
      (node (ref "C16") (pin "E1") (pinfunction "OUT_E1") (pintype "output"))
      (node (ref "CD18") (pin "BH2") (pinfunction "BH2_BH2") (pintype "input"))
    )
    (net (code "465") (name "~{00}") (class "Default")
      (node (ref "A07") (pin "D1") (pinfunction "~{O0}_D1") (pintype "output"))
      (node (ref "B22") (pin "S2") (pinfunction "B_S2") (pintype "input"))
    )
    (net (code "466") (name "~{01}") (class "Default")
      (node (ref "A07") (pin "E1") (pinfunction "~{O1}_E1") (pintype "output"))
      (node (ref "A23") (pin "N1") (pinfunction "B_N1") (pintype "input"))
    )
    (net (code "467") (name "~{02}") (class "Default")
      (node (ref "A07") (pin "J1") (pinfunction "~{O2}_J1") (pintype "output"))
      (node (ref "A23") (pin "D2") (pinfunction "A_D2") (pintype "input"))
    )
    (net (code "468") (name "~{03}") (class "Default")
      (node (ref "A07") (pin "N1") (pinfunction "~{O3}_N1") (pintype "output"))
      (node (ref "A23") (pin "E2") (pinfunction "B_E2") (pintype "input"))
    )
    (net (code "469") (name "~{04}") (class "Default")
      (node (ref "A07") (pin "F1") (pinfunction "~{O4}_F1") (pintype "output"))
      (node (ref "A23") (pin "K2") (pinfunction "A_K2") (pintype "input"))
    )
    (net (code "470") (name "~{05}") (class "Default")
      (node (ref "A07") (pin "M1") (pinfunction "~{O5}_M1") (pintype "output"))
      (node (ref "A23") (pin "L2") (pinfunction "B_L2") (pintype "input"))
    )
    (net (code "471") (name "~{06}") (class "Default")
      (node (ref "A07") (pin "H1") (pinfunction "~{O6}_H1") (pintype "output"))
      (node (ref "A23") (pin "R2") (pinfunction "A_R2") (pintype "input"))
    )
    (net (code "472") (name "~{07}") (class "Default")
      (node (ref "A07") (pin "L1") (pinfunction "~{O7}_L1") (pintype "output"))
      (node (ref "A23") (pin "S2") (pinfunction "B_S2") (pintype "input"))
    )
    (net (code "473") (name "~{76}") (class "Default")
      (node (ref "C06") (pin "T2") (pinfunction "OUT_T2") (pintype "output"))
      (node (ref "D12") (pin "R2") (pinfunction "IN1_R2") (pintype "input"))
      (node (ref "D12") (pin "S2") (pinfunction "IN2_S2") (pintype "input"))
    )
    (net (code "474") (name "~{77}") (class "Default")
      (node (ref "C06") (pin "V2") (pinfunction "OUT_V2") (pintype "output"))
      (node (ref "D12") (pin "T2") (pinfunction "IN3_T2") (pintype "input"))
      (node (ref "D12") (pin "U2") (pinfunction "IN4_U2") (pintype "input"))
    )
    (net (code "475") (name "~{ADDR_ACC}") (class "Default")
      (node (ref "B08") (pin "T2") (pinfunction "IN1_T2") (pintype "input"))
      (node (ref "C17") (pin "P1") (pinfunction "OUT_P1") (pintype "output"))
    )
    (net (code "476") (name "~{B-BRK}") (class "Default")
      (node (ref "B02") (pin "C1") (pinfunction "C_C1") (pintype "input"))
      (node (ref "B02") (pin "F2") (pinfunction "C_F2") (pintype "input"))
      (node (ref "B02") (pin "J1") (pinfunction "C_J1") (pintype "input"))
      (node (ref "B02") (pin "M2") (pinfunction "C_M2") (pintype "input"))
      (node (ref "B02") (pin "P1") (pinfunction "C_P1") (pintype "input"))
      (node (ref "B02") (pin "T2") (pinfunction "C_T2") (pintype "input"))
      (node (ref "B10") (pin "V2") (pinfunction "OUT_V2") (pintype "output"))
    )
    (net (code "477") (name "~{BAC_00}") (class "Default")
      (node (ref "B06") (pin "A1") (pinfunction "IN_A1") (pintype "input"))
      (node (ref "C03") (pin "B1") (pinfunction "O1_B1") (pintype "output"))
      (node (ref "D10") (pin "F1") (pinfunction "IN1_F1") (pintype "input"))
    )
    (net (code "478") (name "~{BAC_01}") (class "Default")
      (node (ref "B06") (pin "D1") (pinfunction "IN_D1") (pintype "input"))
      (node (ref "C03") (pin "E1") (pinfunction "O2_E1") (pintype "output"))
      (node (ref "D10") (pin "H1") (pinfunction "IN2_H1") (pintype "input"))
    )
    (net (code "479") (name "~{BAC_02}") (class "Default")
      (node (ref "B06") (pin "F1") (pinfunction "IN_F1") (pintype "input"))
      (node (ref "C03") (pin "H1") (pinfunction "O3_H1") (pintype "output"))
      (node (ref "D10") (pin "J1") (pinfunction "IN3_J1") (pintype "input"))
    )
    (net (code "480") (name "~{BAC_03}") (class "Default")
      (node (ref "B06") (pin "J1") (pinfunction "IN_J1") (pintype "input"))
      (node (ref "C03") (pin "K1") (pinfunction "O4_K1") (pintype "output"))
      (node (ref "D10") (pin "K1") (pinfunction "IN4_K1") (pintype "input"))
    )
    (net (code "481") (name "~{BAC_04}") (class "Default")
      (node (ref "B06") (pin "L1") (pinfunction "IN_L1") (pintype "input"))
      (node (ref "C03") (pin "M1") (pinfunction "O5_M1") (pintype "output"))
      (node (ref "D10") (pin "K2") (pinfunction "IN5_K2") (pintype "input"))
    )
    (net (code "482") (name "~{BAC_05}") (class "Default")
      (node (ref "B06") (pin "N1") (pinfunction "IN_N1") (pintype "input"))
      (node (ref "C03") (pin "P1") (pinfunction "O6_P1") (pintype "output"))
    )
    (net (code "483") (name "~{BAC_06}") (class "Default")
      (node (ref "B06") (pin "R1") (pinfunction "IN_R1") (pintype "input"))
      (node (ref "C03") (pin "S1") (pinfunction "O7_S1") (pintype "output"))
    )
    (net (code "484") (name "~{BAC_07}") (class "Default")
      (node (ref "B06") (pin "V1") (pinfunction "IN_V1") (pintype "input"))
      (node (ref "C03") (pin "U1") (pinfunction "O8_U1") (pintype "output"))
    )
    (net (code "485") (name "~{BAC_08}") (class "Default")
      (node (ref "B06") (pin "C1") (pinfunction "IN_C1") (pintype "input"))
      (node (ref "C03") (pin "F2") (pinfunction "O9_F2") (pintype "output"))
    )
    (net (code "486") (name "~{BAC_09}") (class "Default")
      (node (ref "B06") (pin "E2") (pinfunction "IN_E2") (pintype "input"))
      (node (ref "C03") (pin "J2") (pinfunction "O10_J2") (pintype "output"))
    )
    (net (code "487") (name "~{BAC_10}") (class "Default")
      (node (ref "A10") (pin "D2") (pinfunction "IN1_D2") (pintype "input"))
      (node (ref "B06") (pin "H2") (pinfunction "IN_H2") (pintype "input"))
      (node (ref "C03") (pin "L2") (pinfunction "O11_L2") (pintype "output"))
    )
    (net (code "488") (name "~{BAC_11}") (class "Default")
      (node (ref "B06") (pin "K2") (pinfunction "IN_K2") (pintype "input"))
      (node (ref "C03") (pin "N2") (pinfunction "O12_N2") (pintype "output"))
      (node (ref "C11") (pin "R2") (pinfunction "IN2_R2") (pintype "input"))
    )
    (net (code "489") (name "~{BLK_IN_SYNC}") (class "Default")
      (node (ref "A10") (pin "A1") (pinfunction "IN1_A1") (pintype "input"))
      (node (ref "C13") (pin "R1") (pinfunction "IN_R1") (pintype "input"))
      (node (ref "D10") (pin "J2") (pinfunction "OUT_J2") (pintype "output"))
    )
    (net (code "490") (name "~{BMB_00}") (class "Default")
      (node (ref "C02") (pin "B1") (pinfunction "O1_B1") (pintype "output"))
      (node (ref "C06") (pin "A1") (pinfunction "IN_A1") (pintype "input"))
    )
    (net (code "491") (name "~{BMB_01}") (class "Default")
      (node (ref "C02") (pin "E1") (pinfunction "O2_E1") (pintype "output"))
      (node (ref "C06") (pin "D1") (pinfunction "IN_D1") (pintype "input"))
    )
    (net (code "492") (name "~{BMB_02}") (class "Default")
      (node (ref "C02") (pin "H1") (pinfunction "O3_H1") (pintype "output"))
      (node (ref "C06") (pin "F1") (pinfunction "IN_F1") (pintype "input"))
    )
    (net (code "493") (name "~{BMB_03}") (class "Default")
      (node (ref "C02") (pin "K1") (pinfunction "O4_K1") (pintype "output"))
      (node (ref "C06") (pin "J1") (pinfunction "IN_J1") (pintype "input"))
    )
    (net (code "494") (name "~{BMB_04}") (class "Default")
      (node (ref "C02") (pin "M1") (pinfunction "O5_M1") (pintype "output"))
      (node (ref "C06") (pin "L1") (pinfunction "IN_L1") (pintype "input"))
    )
    (net (code "495") (name "~{BMB_05}") (class "Default")
      (node (ref "C02") (pin "P1") (pinfunction "O6_P1") (pintype "output"))
      (node (ref "C06") (pin "N1") (pinfunction "IN_N1") (pintype "input"))
    )
    (net (code "496") (name "~{BMB_06}") (class "Default")
      (node (ref "C02") (pin "S1") (pinfunction "O7_S1") (pintype "output"))
      (node (ref "C06") (pin "R1") (pinfunction "IN_R1") (pintype "input"))
    )
    (net (code "497") (name "~{BMB_07}") (class "Default")
      (node (ref "C02") (pin "U1") (pinfunction "O8_U1") (pintype "output"))
      (node (ref "C06") (pin "V1") (pinfunction "IN_V1") (pintype "input"))
    )
    (net (code "498") (name "~{BMB_08}") (class "Default")
      (node (ref "C02") (pin "F2") (pinfunction "O9_F2") (pintype "output"))
      (node (ref "C06") (pin "C1") (pinfunction "IN_C1") (pintype "input"))
    )
    (net (code "499") (name "~{BMB_09}") (class "Default")
      (node (ref "C02") (pin "J2") (pinfunction "O10_J2") (pintype "output"))
      (node (ref "C06") (pin "E2") (pinfunction "IN_E2") (pintype "input"))
    )
    (net (code "500") (name "~{BMB_10}") (class "Default")
      (node (ref "C02") (pin "L2") (pinfunction "O11_L2") (pintype "output"))
      (node (ref "C06") (pin "H2") (pinfunction "IN_H2") (pintype "input"))
    )
    (net (code "501") (name "~{BMB_11}") (class "Default")
      (node (ref "C02") (pin "N2") (pinfunction "O12_N2") (pintype "output"))
      (node (ref "C06") (pin "K2") (pinfunction "IN_K2") (pintype "input"))
    )
    (net (code "502") (name "~{BMR00}") (class "Default")
      (node (ref "A23") (pin "H1") (pinfunction "B_H1") (pintype "input"))
      (node (ref "B14") (pin "R2") (pinfunction "0_R2") (pintype "output"))
    )
    (net (code "503") (name "~{BMR01}") (class "Default")
      (node (ref "A23") (pin "A1") (pinfunction "A_A1") (pintype "input"))
      (node (ref "B14") (pin "E1") (pinfunction "1_E1") (pintype "output"))
    )
    (net (code "504") (name "~{C00}") (class "Default")
      (node (ref "A12") (pin "P2") (pinfunction "IN1_P2") (pintype "input"))
      (node (ref "B13") (pin "P1") (pinfunction "D_P1") (pintype "input"))
      (node (ref "B13") (pin "S2") (pinfunction "C_S2") (pintype "input"))
      (node (ref "B13") (pin "U1") (pinfunction "0_U1") (pintype "output"))
      (node (ref "B15") (pin "H1") (pinfunction "IN1_H1") (pintype "input"))
      (node (ref "C15") (pin "J2") (pinfunction "IN2_J2") (pintype "input"))
    )
    (net (code "505") (name "~{C01}") (class "Default")
      (node (ref "A12") (pin "R2") (pinfunction "IN2_R2") (pintype "input"))
      (node (ref "B10") (pin "P1") (pinfunction "IN3_P1") (pintype "input"))
      (node (ref "B13") (pin "M2") (pinfunction "D_M2") (pintype "input"))
      (node (ref "B13") (pin "R2") (pinfunction "0_R2") (pintype "output"))
      (node (ref "C12") (pin "F2") (pinfunction "IN3_F2") (pintype "input"))
      (node (ref "D10") (pin "D1") (pinfunction "IN4_D1") (pintype "input"))
    )
    (net (code "506") (name "~{CK00}") (class "Default")
      (node (ref "A18") (pin "N2") (pinfunction "N2_N2") (pintype "input"))
      (node (ref "B14") (pin "T2") (pinfunction "D_T2") (pintype "input"))
      (node (ref "B14") (pin "U1") (pinfunction "0_U1") (pintype "output"))
    )
    (net (code "507") (name "~{CK01}") (class "Default")
      (node (ref "B14") (pin "V1") (pinfunction "0_V1") (pintype "output"))
      (node (ref "C16") (pin "S2") (pinfunction "IN2_S2") (pintype "input"))
      (node (ref "C16") (pin "T2") (pinfunction "IN3_T2") (pintype "input"))
      (node (ref "C16") (pin "U2") (pinfunction "IN4_U2") (pintype "input"))
    )
    (net (code "508") (name "~{CLR_DF}") (class "Default")
      (node (ref "A11") (pin "U1") (pinfunction "OUT_U1") (pintype "output"))
      (node (ref "D11") (pin "N2") (pinfunction "S_N2") (pintype "input"))
    )
    (net (code "509") (name "~{CLR_DTF}") (class "Default")
      (node (ref "C13") (pin "U1") (pinfunction "OUT_U1") (pintype "output"))
      (node (ref "D11") (pin "U2") (pinfunction "S_U2") (pintype "input"))
    )
    (net (code "510") (name "~{CSTA}") (class "Default")
      (node (ref "A10") (pin "L2") (pinfunction "IN1_L2") (pintype "input"))
      (node (ref "C04") (pin "D1") (pinfunction "D1_D1") (pintype "output"))
    )
    (net (code "511") (name "~{DATA}") (class "Default")
      (node (ref "B12") (pin "N1") (pinfunction "IN2_N1") (pintype "input"))
      (node (ref "C11") (pin "L2") (pinfunction "IN1_L2") (pintype "input"))
      (node (ref "C13") (pin "H1") (pinfunction "OUT_H1") (pintype "output"))
      (node (ref "C16") (pin "D2") (pinfunction "IN1_D2") (pintype "input"))
    )
    (net (code "512") (name "~{DB_00}") (class "Default")
      (node (ref "A06") (pin "B1") (pinfunction "P$2_B1") (pintype "bidirectional"))
      (node (ref "B02") (pin "D1") (pinfunction "D_D1") (pintype "open_collector"))
      (node (ref "D06") (pin "B1") (pinfunction "P$2_B1") (pintype "bidirectional"))
    )
    (net (code "513") (name "~{DB_01}") (class "Default")
      (node (ref "A06") (pin "D1") (pinfunction "P$2_D1") (pintype "bidirectional"))
      (node (ref "B02") (pin "E1") (pinfunction "E_E1") (pintype "open_collector"))
      (node (ref "D06") (pin "D1") (pinfunction "P$2_D1") (pintype "bidirectional"))
    )
    (net (code "514") (name "~{DB_02}") (class "Default")
      (node (ref "A06") (pin "E1") (pinfunction "P$2_E1") (pintype "bidirectional"))
      (node (ref "B02") (pin "K1") (pinfunction "D_K1") (pintype "open_collector"))
      (node (ref "D06") (pin "E1") (pinfunction "P$2_E1") (pintype "bidirectional"))
    )
    (net (code "515") (name "~{DB_03}") (class "Default")
      (node (ref "A06") (pin "H1") (pinfunction "P$2_H1") (pintype "bidirectional"))
      (node (ref "B02") (pin "L1") (pinfunction "E_L1") (pintype "open_collector"))
      (node (ref "D06") (pin "H1") (pinfunction "P$2_H1") (pintype "bidirectional"))
    )
    (net (code "516") (name "~{DB_04}") (class "Default")
      (node (ref "A06") (pin "J1") (pinfunction "P$2_J1") (pintype "bidirectional"))
      (node (ref "B02") (pin "R1") (pinfunction "D_R1") (pintype "open_collector"))
      (node (ref "D06") (pin "J1") (pinfunction "P$2_J1") (pintype "bidirectional"))
    )
    (net (code "517") (name "~{DB_05}") (class "Default")
      (node (ref "A06") (pin "L1") (pinfunction "P$2_L1") (pintype "bidirectional"))
      (node (ref "B02") (pin "S1") (pinfunction "E_S1") (pintype "open_collector"))
      (node (ref "D06") (pin "L1") (pinfunction "P$2_L1") (pintype "bidirectional"))
    )
    (net (code "518") (name "~{DB_06}") (class "Default")
      (node (ref "A06") (pin "M1") (pinfunction "P$2_M1") (pintype "bidirectional"))
      (node (ref "B02") (pin "H2") (pinfunction "D_H2") (pintype "open_collector"))
      (node (ref "D06") (pin "M1") (pinfunction "P$2_M1") (pintype "bidirectional"))
    )
    (net (code "519") (name "~{DB_07}") (class "Default")
      (node (ref "A06") (pin "P1") (pinfunction "P$2_P1") (pintype "bidirectional"))
      (node (ref "B02") (pin "J2") (pinfunction "E_J2") (pintype "open_collector"))
      (node (ref "D06") (pin "P1") (pinfunction "P$2_P1") (pintype "bidirectional"))
    )
    (net (code "520") (name "~{DB_08}") (class "Default")
      (node (ref "A06") (pin "S1") (pinfunction "P$2_S1") (pintype "bidirectional"))
      (node (ref "B02") (pin "N2") (pinfunction "D_N2") (pintype "open_collector"))
      (node (ref "D06") (pin "S1") (pinfunction "P$2_S1") (pintype "bidirectional"))
    )
    (net (code "521") (name "~{DB_09}") (class "Default")
      (node (ref "A06") (pin "D2") (pinfunction "P$2_D2") (pintype "bidirectional"))
      (node (ref "B02") (pin "P2") (pinfunction "E_P2") (pintype "open_collector"))
      (node (ref "D06") (pin "D2") (pinfunction "P$2_D2") (pintype "bidirectional"))
    )
    (net (code "522") (name "~{DB_10}") (class "Default")
      (node (ref "A06") (pin "E2") (pinfunction "P$2_E2") (pintype "bidirectional"))
      (node (ref "B02") (pin "U2") (pinfunction "D_U2") (pintype "open_collector"))
      (node (ref "D06") (pin "E2") (pinfunction "P$2_E2") (pintype "bidirectional"))
    )
    (net (code "523") (name "~{DB_11}") (class "Default")
      (node (ref "A06") (pin "H2") (pinfunction "P$2_H2") (pintype "bidirectional"))
      (node (ref "B02") (pin "V2") (pinfunction "E_V2") (pintype "open_collector"))
      (node (ref "D06") (pin "H2") (pinfunction "P$2_H2") (pintype "bidirectional"))
    )
    (net (code "524") (name "~{DF}") (class "Default")
      (node (ref "B05") (pin "A1") (pinfunction "A_A1") (pintype "input"))
      (node (ref "B12") (pin "J1") (pinfunction "IN3_J1") (pintype "input"))
      (node (ref "D11") (pin "P2") (pinfunction "1_P2") (pintype "output"))
    )
    (net (code "525") (name "~{DTB_00}") (class "Default")
      (node (ref "B02") (pin "A1") (pinfunction "A_A1") (pintype "input"))
      (node (ref "C09") (pin "F1") (pinfunction "0_F1") (pintype "output"))
    )
    (net (code "526") (name "~{DTB_01}") (class "Default")
      (node (ref "B02") (pin "B1") (pinfunction "B_B1") (pintype "input"))
      (node (ref "C09") (pin "J2") (pinfunction "0_J2") (pintype "output"))
    )
    (net (code "527") (name "~{DTB_02}") (class "Default")
      (node (ref "B02") (pin "F1") (pinfunction "A_F1") (pintype "input"))
      (node (ref "C09") (pin "M1") (pinfunction "0_M1") (pintype "output"))
    )
    (net (code "528") (name "~{DTB_03}") (class "Default")
      (node (ref "B02") (pin "H1") (pinfunction "B_H1") (pintype "input"))
      (node (ref "C09") (pin "R2") (pinfunction "0_R2") (pintype "output"))
    )
    (net (code "529") (name "~{DTB_04}") (class "Default")
      (node (ref "B02") (pin "M1") (pinfunction "A_M1") (pintype "input"))
      (node (ref "C09") (pin "U1") (pinfunction "0_U1") (pintype "output"))
    )
    (net (code "530") (name "~{DTB_05}") (class "Default")
      (node (ref "B02") (pin "N1") (pinfunction "B_N1") (pintype "input"))
      (node (ref "C09") (pin "V1") (pinfunction "0_V1") (pintype "output"))
    )
    (net (code "531") (name "~{DTB_06}") (class "Default")
      (node (ref "B02") (pin "D2") (pinfunction "A_D2") (pintype "input"))
      (node (ref "B09") (pin "F1") (pinfunction "0_F1") (pintype "output"))
    )
    (net (code "532") (name "~{DTB_07}") (class "Default")
      (node (ref "B02") (pin "E2") (pinfunction "B_E2") (pintype "input"))
      (node (ref "B09") (pin "V1") (pinfunction "0_V1") (pintype "output"))
    )
    (net (code "533") (name "~{DTB_08}") (class "Default")
      (node (ref "B02") (pin "K2") (pinfunction "A_K2") (pintype "input"))
      (node (ref "B09") (pin "M1") (pinfunction "0_M1") (pintype "output"))
    )
    (net (code "534") (name "~{DTB_09}") (class "Default")
      (node (ref "B02") (pin "L2") (pinfunction "B_L2") (pintype "input"))
      (node (ref "B09") (pin "R2") (pinfunction "0_R2") (pintype "output"))
    )
    (net (code "535") (name "~{DTB_10}") (class "Default")
      (node (ref "B02") (pin "R2") (pinfunction "A_R2") (pintype "input"))
      (node (ref "B09") (pin "U1") (pinfunction "0_U1") (pintype "output"))
    )
    (net (code "536") (name "~{DTB_11}") (class "Default")
      (node (ref "B02") (pin "S2") (pinfunction "B_S2") (pintype "input"))
      (node (ref "B09") (pin "J2") (pinfunction "0_J2") (pintype "output"))
    )
    (net (code "537") (name "~{DTF}") (class "Default")
      (node (ref "B04") (pin "L2") (pinfunction "B_L2") (pintype "input"))
      (node (ref "B12") (pin "C1") (pinfunction "IN3_C1") (pintype "input"))
      (node (ref "D11") (pin "V2") (pinfunction "1_V2") (pintype "output"))
    )
    (net (code "538") (name "~{DTSF}") (class "Default")
      (node (ref "C05") (pin "B1") (pinfunction "B1_B1") (pintype "output"))
    )
    (net (code "539") (name "~{EA_00}") (class "Default")
      (node (ref "A06") (pin "V2") (pinfunction "P$2_V2") (pintype "bidirectional"))
      (node (ref "B05") (pin "R1") (pinfunction "D_R1") (pintype "open_collector"))
      (node (ref "D06") (pin "V2") (pinfunction "P$2_V2") (pintype "bidirectional"))
    )
    (net (code "540") (name "~{EA_01}") (class "Default")
      (node (ref "A06") (pin "T2") (pinfunction "P$2_T2") (pintype "bidirectional"))
      (node (ref "B05") (pin "S1") (pinfunction "E_S1") (pintype "open_collector"))
      (node (ref "D06") (pin "T2") (pinfunction "P$2_T2") (pintype "bidirectional"))
    )
    (net (code "541") (name "~{EA_02}") (class "Default")
      (node (ref "A06") (pin "S2") (pinfunction "P$2_S2") (pintype "bidirectional"))
      (node (ref "B05") (pin "H2") (pinfunction "D_H2") (pintype "open_collector"))
      (node (ref "D06") (pin "S2") (pinfunction "P$2_S2") (pintype "bidirectional"))
    )
    (net (code "542") (name "~{EF}") (class "Default")
      (node (ref "A11") (pin "K1") (pinfunction "OUT_K1") (pintype "output"))
      (node (ref "B04") (pin "A1") (pinfunction "A_A1") (pintype "input"))
    )
    (net (code "543") (name "~{END}") (class "Default")
      (node (ref "A08") (pin "F1") (pinfunction "0_F1") (pintype "output"))
      (node (ref "A09") (pin "M2") (pinfunction "IN3_M2") (pintype "input"))
      (node (ref "B04") (pin "F1") (pinfunction "A_F1") (pintype "input"))
    )
    (net (code "544") (name "~{ENI}") (class "Default")
      (node (ref "B03") (pin "L2") (pinfunction "B_L2") (pintype "input"))
      (node (ref "C07") (pin "M1") (pinfunction "M1_M1") (pintype "output"))
    )
    (net (code "545") (name "~{FR_00}") (class "Default")
      (node (ref "B03") (pin "N1") (pinfunction "B_N1") (pintype "input"))
      (node (ref "B07") (pin "U1") (pinfunction "U1_U1") (pintype "output"))
      (node (ref "C12") (pin "K1") (pinfunction "IN1_K1") (pintype "input"))
      (node (ref "C12") (pin "P1") (pinfunction "IN1_P1") (pintype "input"))
    )
    (net (code "546") (name "~{FR_01}") (class "Default")
      (node (ref "A12") (pin "H2") (pinfunction "IN1_H2") (pintype "input"))
      (node (ref "B03") (pin "D2") (pinfunction "A_D2") (pintype "input"))
      (node (ref "B05") (pin "E2") (pinfunction "B_E2") (pintype "input"))
      (node (ref "B07") (pin "V1") (pinfunction "V1_V1") (pintype "output"))
    )
    (net (code "547") (name "~{FR_02}") (class "Default")
      (node (ref "B03") (pin "E2") (pinfunction "B_E2") (pintype "input"))
      (node (ref "C07") (pin "F1") (pinfunction "F1_F1") (pintype "output"))
    )
    (net (code "548") (name "~{FR_03}") (class "Default")
      (node (ref "B03") (pin "K2") (pinfunction "A_K2") (pintype "input"))
      (node (ref "B08") (pin "J2") (pinfunction "IN2_J2") (pintype "input"))
      (node (ref "C07") (pin "J2") (pinfunction "J2_J2") (pintype "output"))
    )
    (net (code "549") (name "~{IM_00}") (class "Default")
      (node (ref "A04") (pin "B1") (pinfunction "P$2_B1") (pintype "bidirectional"))
      (node (ref "B03") (pin "D1") (pinfunction "D_D1") (pintype "open_collector"))
      (node (ref "B04") (pin "D1") (pinfunction "D_D1") (pintype "open_collector"))
      (node (ref "D04") (pin "B1") (pinfunction "P$2_B1") (pintype "bidirectional"))
    )
    (net (code "550") (name "~{IM_01}") (class "Default")
      (node (ref "A04") (pin "D1") (pinfunction "P$2_D1") (pintype "bidirectional"))
      (node (ref "B03") (pin "E1") (pinfunction "E_E1") (pintype "open_collector"))
      (node (ref "B04") (pin "E1") (pinfunction "E_E1") (pintype "open_collector"))
      (node (ref "D04") (pin "D1") (pinfunction "P$2_D1") (pintype "bidirectional"))
    )
    (net (code "551") (name "~{IM_02}") (class "Default")
      (node (ref "A04") (pin "E1") (pinfunction "P$2_E1") (pintype "bidirectional"))
      (node (ref "B03") (pin "K1") (pinfunction "D_K1") (pintype "open_collector"))
      (node (ref "B04") (pin "K1") (pinfunction "D_K1") (pintype "open_collector"))
      (node (ref "D04") (pin "E1") (pinfunction "P$2_E1") (pintype "bidirectional"))
    )
    (net (code "552") (name "~{IM_03}") (class "Default")
      (node (ref "A04") (pin "H1") (pinfunction "P$2_H1") (pintype "bidirectional"))
      (node (ref "B03") (pin "L1") (pinfunction "E_L1") (pintype "open_collector"))
      (node (ref "B04") (pin "L1") (pinfunction "E_L1") (pintype "open_collector"))
      (node (ref "D04") (pin "H1") (pinfunction "P$2_H1") (pintype "bidirectional"))
    )
    (net (code "553") (name "~{IM_04}") (class "Default")
      (node (ref "A04") (pin "J1") (pinfunction "P$2_J1") (pintype "bidirectional"))
      (node (ref "B03") (pin "R1") (pinfunction "D_R1") (pintype "open_collector"))
      (node (ref "B04") (pin "R1") (pinfunction "D_R1") (pintype "open_collector"))
      (node (ref "D04") (pin "J1") (pinfunction "P$2_J1") (pintype "bidirectional"))
    )
    (net (code "554") (name "~{IM_05}") (class "Default")
      (node (ref "A04") (pin "L1") (pinfunction "P$2_L1") (pintype "bidirectional"))
      (node (ref "B03") (pin "S1") (pinfunction "E_S1") (pintype "open_collector"))
      (node (ref "B04") (pin "S1") (pinfunction "E_S1") (pintype "open_collector"))
      (node (ref "D04") (pin "L1") (pinfunction "P$2_L1") (pintype "bidirectional"))
    )
    (net (code "555") (name "~{IM_06}") (class "Default")
      (node (ref "A04") (pin "M1") (pinfunction "P$2_M1") (pintype "bidirectional"))
      (node (ref "B03") (pin "H2") (pinfunction "D_H2") (pintype "open_collector"))
      (node (ref "B04") (pin "H2") (pinfunction "D_H2") (pintype "open_collector"))
      (node (ref "D04") (pin "M1") (pinfunction "P$2_M1") (pintype "bidirectional"))
    )
    (net (code "556") (name "~{IM_07}") (class "Default")
      (node (ref "A04") (pin "P1") (pinfunction "P$2_P1") (pintype "bidirectional"))
      (node (ref "B03") (pin "J2") (pinfunction "E_J2") (pintype "open_collector"))
      (node (ref "B04") (pin "J2") (pinfunction "E_J2") (pintype "open_collector"))
      (node (ref "D04") (pin "P1") (pinfunction "P$2_P1") (pintype "bidirectional"))
    )
    (net (code "557") (name "~{IM_08}") (class "Default")
      (node (ref "A04") (pin "S1") (pinfunction "P$2_S1") (pintype "bidirectional"))
      (node (ref "B03") (pin "N2") (pinfunction "D_N2") (pintype "open_collector"))
      (node (ref "B04") (pin "N2") (pinfunction "D_N2") (pintype "open_collector"))
      (node (ref "D04") (pin "S1") (pinfunction "P$2_S1") (pintype "bidirectional"))
    )
    (net (code "558") (name "~{IM_09}") (class "Default")
      (node (ref "A04") (pin "D2") (pinfunction "P$2_D2") (pintype "bidirectional"))
      (node (ref "B03") (pin "P2") (pinfunction "E_P2") (pintype "open_collector"))
      (node (ref "D04") (pin "D2") (pinfunction "P$2_D2") (pintype "bidirectional"))
    )
    (net (code "559") (name "~{IM_10}") (class "Default")
      (node (ref "A04") (pin "E2") (pinfunction "P$2_E2") (pintype "bidirectional"))
      (node (ref "D04") (pin "E2") (pinfunction "P$2_E2") (pintype "bidirectional"))
    )
    (net (code "560") (name "~{IM_11}") (class "Default")
      (node (ref "A04") (pin "H2") (pinfunction "P$2_H2") (pintype "bidirectional"))
      (node (ref "B04") (pin "P2") (pinfunction "E_P2") (pintype "open_collector"))
      (node (ref "D04") (pin "H2") (pinfunction "P$2_H2") (pintype "bidirectional"))
    )
    (net (code "561") (name "~{INT_RQ}") (class "Default")
      (node (ref "A12") (pin "K1") (pinfunction "OUT_K1") (pintype "output"))
      (node (ref "B05") (pin "B1") (pinfunction "B_B1") (pintype "input"))
    )
    (net (code "562") (name "~{LDMF}") (class "Default")
      (node (ref "B08") (pin "P2") (pinfunction "IN1_P2") (pintype "input"))
      (node (ref "C05") (pin "F1") (pinfunction "F1_F1") (pintype "output"))
    )
    (net (code "563") (name "~{LPB_00}") (class "Default")
      (node (ref "D08") (pin "F1") (pinfunction "F1_F1") (pintype "output"))
      (node (ref "D10") (pin "M1") (pinfunction "IN1_M1") (pintype "input"))
    )
    (net (code "564") (name "~{LPB_01}") (class "Default")
      (node (ref "D08") (pin "M1") (pinfunction "M1_M1") (pintype "output"))
      (node (ref "D10") (pin "N1") (pinfunction "IN2_N1") (pintype "input"))
    )
    (net (code "565") (name "~{LPB_02}") (class "Default")
      (node (ref "D08") (pin "U1") (pinfunction "U1_U1") (pintype "output"))
      (node (ref "D10") (pin "P1") (pinfunction "IN3_P1") (pintype "input"))
    )
    (net (code "566") (name "~{LPB_03}") (class "Default")
      (node (ref "D08") (pin "J2") (pinfunction "J2_J2") (pintype "output"))
      (node (ref "D10") (pin "R1") (pinfunction "IN4_R1") (pintype "input"))
    )
    (net (code "567") (name "~{LPB_04}") (class "Default")
      (node (ref "D08") (pin "R2") (pinfunction "R2_R2") (pintype "output"))
      (node (ref "D10") (pin "R2") (pinfunction "IN5_R2") (pintype "input"))
    )
    (net (code "568") (name "~{LPB_05}") (class "Default")
      (node (ref "D08") (pin "V1") (pinfunction "V1_V1") (pintype "output"))
      (node (ref "D10") (pin "S2") (pinfunction "IN6_S2") (pintype "input"))
      (node (ref "D10") (pin "T2") (pinfunction "IN7_T2") (pintype "input"))
      (node (ref "D10") (pin "U2") (pinfunction "IN8_U2") (pintype "input"))
    )
    (net (code "569") (name "~{M-STOP}") (class "Default")
      (node (ref "A11") (pin "S1") (pinfunction "OUT_S1") (pintype "output"))
      (node (ref "B14") (pin "D1") (pinfunction "S_D1") (pintype "input"))
      (node (ref "C07") (pin "K2") (pinfunction "K2_K2") (pintype "input"))
      (node (ref "D14") (pin "L1") (pinfunction "M1_L1") (pintype "input"))
    )
    (net (code "570") (name "~{MB_TO_DTB}") (class "Default")
      (node (ref "D12") (pin "F1") (pinfunction "IN1_F1") (pintype "input"))
      (node (ref "D12") (pin "H1") (pinfunction "IN2_H1") (pintype "input"))
      (node (ref "D12") (pin "J1") (pinfunction "IN3_J1") (pintype "input"))
      (node (ref "D12") (pin "K1") (pinfunction "IN4_K1") (pintype "input"))
      (node (ref "D12") (pin "S1") (pinfunction "OUT_S1") (pintype "output"))
    )
    (net (code "571") (name "~{MC00}") (class "Default")
      (node (ref "A10") (pin "R1") (pinfunction "IN2_R1") (pintype "input"))
      (node (ref "B11") (pin "T2") (pinfunction "IN1_T2") (pintype "input"))
      (node (ref "B13") (pin "F1") (pinfunction "0_F1") (pintype "output"))
    )
    (net (code "572") (name "~{MC01}") (class "Default")
      (node (ref "B11") (pin "P1") (pinfunction "IN1_P1") (pintype "input"))
      (node (ref "B13") (pin "J2") (pinfunction "0_J2") (pintype "output"))
      (node (ref "C11") (pin "B1") (pinfunction "IN2_B1") (pintype "input"))
      (node (ref "D10") (pin "E2") (pinfunction "IN6_E2") (pintype "input"))
    )
    (net (code "573") (name "~{MC02}") (class "Default")
      (node (ref "B13") (pin "C1") (pinfunction "D_C1") (pintype "input"))
      (node (ref "B13") (pin "M1") (pinfunction "0_M1") (pintype "output"))
      (node (ref "D10") (pin "F2") (pinfunction "IN7_F2") (pintype "input"))
    )
    (net (code "574") (name "~{MF00}") (class "Default")
      (node (ref "B04") (pin "D2") (pinfunction "A_D2") (pintype "input"))
      (node (ref "B05") (pin "M1") (pinfunction "A_M1") (pintype "input"))
      (node (ref "D11") (pin "F1") (pinfunction "0_F1") (pintype "output"))
    )
    (net (code "575") (name "~{MF01}") (class "Default")
      (node (ref "B04") (pin "E2") (pinfunction "B_E2") (pintype "input"))
      (node (ref "B05") (pin "N1") (pinfunction "B_N1") (pintype "input"))
      (node (ref "D11") (pin "J2") (pinfunction "0_J2") (pintype "output"))
    )
    (net (code "576") (name "~{MF02}") (class "Default")
      (node (ref "B04") (pin "K2") (pinfunction "A_K2") (pintype "input"))
      (node (ref "B05") (pin "D2") (pinfunction "A_D2") (pintype "input"))
      (node (ref "D11") (pin "M1") (pinfunction "0_M1") (pintype "output"))
    )
    (net (code "577") (name "~{MKTK}") (class "Default")
      (node (ref "A08") (pin "P2") (pinfunction "1_P2") (pintype "output"))
      (node (ref "A09") (pin "K2") (pinfunction "IN1_K2") (pintype "input"))
      (node (ref "B04") (pin "B1") (pinfunction "B_B1") (pintype "input"))
    )
    (net (code "578") (name "~{MKT}") (class "Default")
      (node (ref "B10") (pin "R1") (pinfunction "IN4_R1") (pintype "input"))
      (node (ref "B13") (pin "T2") (pinfunction "D_T2") (pintype "input"))
      (node (ref "B13") (pin "V1") (pinfunction "0_V1") (pintype "output"))
      (node (ref "C14") (pin "N1") (pinfunction "C_N1") (pintype "input"))
      (node (ref "D10") (pin "H2") (pinfunction "IN8_H2") (pintype "input"))
    )
    (net (code "579") (name "~{MK_BLK_END}") (class "Default")
      (node (ref "A09") (pin "C1") (pinfunction "IN3_C1") (pintype "input"))
      (node (ref "CD18") (pin "BV1") (pinfunction "BV1_BV1") (pintype "output"))
    )
    (net (code "580") (name "~{MK_BLK_MK}") (class "Default")
      (node (ref "CD18") (pin "AD2") (pinfunction "AD2_AD2") (pintype "output"))
    )
    (net (code "581") (name "~{MK_BLK_START}") (class "Default")
      (node (ref "A09") (pin "A1") (pinfunction "IN1_A1") (pintype "input"))
      (node (ref "CD18") (pin "AF1") (pinfunction "AF1_AF1") (pintype "output"))
    )
    (net (code "582") (name "~{MK_BLK_SYNC}") (class "Default")
      (node (ref "CD18") (pin "BT2") (pinfunction "BT2_BT2") (pintype "output"))
    )
    (net (code "583") (name "~{MK_DATA_SYNC}") (class "Default")
      (node (ref "CD18") (pin "AJ1") (pinfunction "AJ1_AJ1") (pintype "output"))
    )
    (net (code "584") (name "~{MK_DATA}") (class "Default")
      (node (ref "A09") (pin "B1") (pinfunction "IN2_B1") (pintype "input"))
      (node (ref "CD18") (pin "AU2") (pinfunction "AU2_AU2") (pintype "output"))
    )
    (net (code "585") (name "~{MK_END}") (class "Default")
      (node (ref "A09") (pin "D1") (pinfunction "IN4_D1") (pintype "input"))
      (node (ref "CD18") (pin "AH2") (pinfunction "AH2_AH2") (pintype "output"))
    )
    (net (code "586") (name "~{MOVE}") (class "Default")
      (node (ref "A09") (pin "F2") (pinfunction "IN3_F2") (pintype "input"))
      (node (ref "D07") (pin "D1") (pinfunction "~{O0}_D1") (pintype "output"))
    )
    (net (code "587") (name "~{MR00}") (class "Default")
      (node (ref "B03") (pin "H1") (pinfunction "B_H1") (pintype "input"))
      (node (ref "B07") (pin "R2") (pinfunction "R2_R2") (pintype "output"))
    )
    (net (code "588") (name "~{MR01}") (class "Default")
      (node (ref "B03") (pin "M1") (pinfunction "A_M1") (pintype "input"))
      (node (ref "B14") (pin "C1") (pinfunction "D_C1") (pintype "input"))
      (node (ref "C07") (pin "R2") (pinfunction "R2_R2") (pintype "output"))
    )
    (net (code "589") (name "~{PAR}") (class "Default")
      (node (ref "A08") (pin "S1") (pinfunction "1_S1") (pintype "output"))
      (node (ref "A12") (pin "E1") (pinfunction "IN2_E1") (pintype "input"))
      (node (ref "B04") (pin "M1") (pinfunction "A_M1") (pintype "input"))
    )
    (net (code "590") (name "~{PC+ES}") (class "Default")
      (node (ref "A11") (pin "J2") (pinfunction "OUT_J2") (pintype "output"))
      (node (ref "B11") (pin "R2") (pinfunction "IN3_R2") (pintype "input"))
    )
    (net (code "591") (name "~{PWR_CLR}") (class "Default")
      (node (ref "A10") (pin "H2") (pinfunction "IN1_H2") (pintype "input"))
      (node (ref "A10") (pin "M2") (pinfunction "IN2_M2") (pintype "input"))
      (node (ref "A12") (pin "A1") (pinfunction "IN1_A1") (pintype "input"))
      (node (ref "A23") (pin "M1") (pinfunction "A_M1") (pintype "input"))
      (node (ref "B08") (pin "U2") (pinfunction "IN2_U2") (pintype "input"))
      (node (ref "C05") (pin "K1") (pinfunction "OUT_K1") (pintype "output"))
      (node (ref "C06") (pin "P2") (pinfunction "IN_P2") (pintype "input"))
      (node (ref "C11") (pin "U2") (pinfunction "IN2_U2") (pintype "input"))
      (node (ref "C14") (pin "R1") (pinfunction "S_R1") (pintype "input"))
      (node (ref "D11") (pin "A1") (pinfunction "R_A1") (pintype "input"))
    )
    (net (code "592") (name "~{RDD_00}") (class "Default")
      (node (ref "A21") (pin "V2") (pinfunction "V2_V2") (pintype "output"))
    )
    (net (code "593") (name "~{RDD_01}") (class "Default")
      (node (ref "B20") (pin "V2") (pinfunction "V2_V2") (pintype "output"))
    )
    (net (code "594") (name "~{RDD_02}") (class "Default")
      (node (ref "A20") (pin "V2") (pinfunction "V2_V2") (pintype "output"))
    )
    (net (code "595") (name "~{RDMK}") (class "Default")
      (node (ref "B18") (pin "V2") (pinfunction "V2_V2") (pintype "output"))
    )
    (net (code "596") (name "~{READ_ALL}") (class "Default")
      (node (ref "C11") (pin "M1") (pinfunction "IN2_M1") (pintype "input"))
      (node (ref "D07") (pin "N1") (pinfunction "~{O3}_N1") (pintype "output"))
    )
    (net (code "597") (name "~{READ_DATA}") (class "Default")
      (node (ref "B08") (pin "L2") (pinfunction "IN1_L2") (pintype "input"))
      (node (ref "B11") (pin "J2") (pinfunction "IN1_J2") (pintype "input"))
      (node (ref "D07") (pin "J1") (pinfunction "~{O2}_J1") (pintype "output"))
    )
    (net (code "598") (name "~{RSTA}") (class "Default")
      (node (ref "B03") (pin "C1") (pinfunction "C_C1") (pintype "input"))
      (node (ref "B03") (pin "F2") (pinfunction "C_F2") (pintype "input"))
      (node (ref "B03") (pin "J1") (pinfunction "C_J1") (pintype "input"))
      (node (ref "B03") (pin "M2") (pinfunction "C_M2") (pintype "input"))
      (node (ref "B03") (pin "P1") (pinfunction "C_P1") (pintype "input"))
      (node (ref "C04") (pin "B1") (pinfunction "B1_B1") (pintype "output"))
    )
    (net (code "599") (name "~{RSTB}") (class "Default")
      (node (ref "B04") (pin "C1") (pinfunction "C_C1") (pintype "input"))
      (node (ref "B04") (pin "F2") (pinfunction "C_F2") (pintype "input"))
      (node (ref "B04") (pin "J1") (pinfunction "C_J1") (pintype "input"))
      (node (ref "B04") (pin "M2") (pinfunction "C_M2") (pintype "input"))
      (node (ref "B04") (pin "P1") (pinfunction "C_P1") (pintype "input"))
      (node (ref "C05") (pin "D1") (pinfunction "D1_D1") (pintype "output"))
    )
    (net (code "600") (name "~{SEARCH}") (class "Default")
      (node (ref "B05") (pin "K2") (pinfunction "A_K2") (pintype "input"))
      (node (ref "B11") (pin "K2") (pinfunction "IN2_K2") (pintype "input"))
      (node (ref "D07") (pin "E1") (pinfunction "~{O1}_E1") (pintype "output"))
    )
    (net (code "601") (name "~{SEL}") (class "Default")
      (node (ref "A08") (pin "J2") (pinfunction "0_J2") (pintype "output"))
      (node (ref "A09") (pin "N2") (pinfunction "IN4_N2") (pintype "input"))
      (node (ref "B04") (pin "H1") (pinfunction "B_H1") (pintype "input"))
    )
    (net (code "602") (name "~{SE}") (class "Default")
      (node (ref "A09") (pin "H1") (pinfunction "IN2_H1") (pintype "input"))
      (node (ref "D07") (pin "L1") (pinfunction "~{O7}_L1") (pintype "output"))
    )
    (net (code "603") (name "~{SH_EN}") (class "Default")
      (node (ref "A11") (pin "M2") (pinfunction "IN_M2") (pintype "input"))
      (node (ref "A12") (pin "V2") (pinfunction "OUT_V2") (pintype "output"))
      (node (ref "C10") (pin "C1") (pinfunction "IN2A_C1") (pintype "input"))
      (node (ref "C10") (pin "J1") (pinfunction "IN2A_J1") (pintype "input"))
      (node (ref "C10") (pin "P1") (pinfunction "IN2A_P1") (pintype "input"))
    )
    (net (code "604") (name "~{SKP_RQ}") (class "Default")
      (node (ref "A12") (pin "S1") (pinfunction "OUT_S1") (pintype "output"))
      (node (ref "B05") (pin "F1") (pinfunction "A_F1") (pintype "input"))
    )
    (net (code "605") (name "~{SP_DY}") (class "Default")
      (node (ref "C14") (pin "M2") (pinfunction "D_M2") (pintype "input"))
      (node (ref "D14") (pin "F2") (pinfunction "F2_F2") (pintype "output"))
    )
    (net (code "606") (name "~{ST_BLK_MK}") (class "Default")
      (node (ref "A09") (pin "D2") (pinfunction "IN1_D2") (pintype "input"))
      (node (ref "A09") (pin "M1") (pinfunction "IN1_M1") (pintype "input"))
      (node (ref "C13") (pin "F2") (pinfunction "OUT_F2") (pintype "output"))
    )
    (net (code "607") (name "~{ST_CK_0P}") (class "Default")
      (node (ref "C13") (pin "A1") (pinfunction "IN_A1") (pintype "input"))
      (node (ref "D17") (pin "L2") (pinfunction "F2_L2") (pintype "output"))
    )
    (net (code "608") (name "~{ST_CK}") (class "Default")
      (node (ref "C13") (pin "K1") (pinfunction "OUT_K1") (pintype "output"))
      (node (ref "C16") (pin "E2") (pinfunction "IN2_E2") (pintype "input"))
    )
    (net (code "609") (name "~{ST_DATA}") (class "Default")
      (node (ref "C13") (pin "J2") (pinfunction "OUT_J2") (pintype "output"))
    )
    (net (code "610") (name "~{ST_FINAL}") (class "Default")
      (node (ref "C11") (pin "M2") (pinfunction "IN2_M2") (pintype "input"))
      (node (ref "C13") (pin "M1") (pinfunction "OUT_M1") (pintype "output"))
      (node (ref "C16") (pin "F2") (pinfunction "IN3_F2") (pintype "input"))
    )
    (net (code "611") (name "~{ST_IDLE}") (class "Default")
      (node (ref "A09") (pin "E2") (pinfunction "IN2_E2") (pintype "input"))
      (node (ref "A09") (pin "N1") (pinfunction "IN2_N1") (pintype "input"))
      (node (ref "C13") (pin "L2") (pinfunction "OUT_L2") (pintype "output"))
    )
    (net (code "612") (name "~{ST_REV_CK}") (class "Default")
      (node (ref "C13") (pin "E1") (pinfunction "OUT_E1") (pintype "output"))
    )
    (net (code "613") (name "~{SWTM}") (class "Default")
      (node (ref "B06") (pin "R2") (pinfunction "OUT_R2") (pintype "output"))
      (node (ref "C10") (pin "L2") (pinfunction "IN1B_L2") (pintype "input"))
    )
    (net (code "614") (name "~{SYNC-P}") (class "Default")
      (node (ref "B10") (pin "J2") (pinfunction "OUT_J2") (pintype "output"))
      (node (ref "B13") (pin "A1") (pinfunction "R_A1") (pintype "input"))
      (node (ref "B13") (pin "K2") (pinfunction "R_K2") (pintype "input"))
    )
    (net (code "615") (name "~{SYNC}") (class "Default")
      (node (ref "CD18") (pin "BM2") (pinfunction "BM2_BM2") (pintype "output"))
    )
    (net (code "616") (name "~{TIM}") (class "Default")
      (node (ref "A08") (pin "M1") (pinfunction "0_M1") (pintype "output"))
      (node (ref "A09") (pin "L2") (pinfunction "IN2_L2") (pintype "input"))
      (node (ref "B04") (pin "N1") (pinfunction "B_N1") (pintype "input"))
    )
    (net (code "617") (name "~{TM_EN}") (class "Default")
      (node (ref "B15") (pin "D1") (pinfunction "IN1_D1") (pintype "input"))
      (node (ref "B15") (pin "D2") (pinfunction "IN1_D2") (pintype "input"))
      (node (ref "C12") (pin "C1") (pinfunction "IN3_C1") (pintype "input"))
      (node (ref "C12") (pin "K2") (pinfunction "IN2_K2") (pintype "input"))
      (node (ref "C13") (pin "P1") (pinfunction "OUT_P1") (pintype "output"))
      (node (ref "D15") (pin "J2") (pinfunction "J2_J2") (pintype "input"))
      (node (ref "D15") (pin "K2") (pinfunction "K2_K2") (pintype "input"))
    )
    (net (code "618") (name "~{TP00_A}") (class "Default")
      (node (ref "A15") (pin "M1") (pinfunction "IN1_M1") (pintype "input"))
      (node (ref "A15") (pin "N1") (pinfunction "IN2_N1") (pintype "input"))
      (node (ref "A15") (pin "P1") (pinfunction "IN3_P1") (pintype "input"))
      (node (ref "A15") (pin "R1") (pinfunction "IN4_R1") (pintype "input"))
      (node (ref "A16") (pin "L2") (pinfunction "F2_L2") (pintype "output"))
    )
    (net (code "619") (name "~{TP0_XTLK_DY}") (class "Default")
      (node (ref "A11") (pin "R2") (pinfunction "OUT_R2") (pintype "output"))
      (node (ref "A15") (pin "F2") (pinfunction "IN3_F2") (pintype "input"))
      (node (ref "A16") (pin "J2") (pinfunction "J2_J2") (pintype "input"))
      (node (ref "A16") (pin "K2") (pinfunction "K2_K2") (pintype "input"))
    )
    (net (code "620") (name "~{TP00}") (class "Default")
      (node (ref "A15") (pin "E1") (pinfunction "OUT_E1") (pintype "output"))
      (node (ref "A15") (pin "F1") (pinfunction "IN1_F1") (pintype "input"))
      (node (ref "A15") (pin "H1") (pinfunction "IN2_H1") (pintype "input"))
      (node (ref "A15") (pin "J1") (pinfunction "IN3_J1") (pintype "input"))
      (node (ref "A15") (pin "K1") (pinfunction "IN4_K1") (pintype "input"))
      (node (ref "B13") (pin "N1") (pinfunction "C_N1") (pintype "input"))
      (node (ref "CD18") (pin "AN1") (pinfunction "AN1_AN1") (pintype "input"))
    )
    (net (code "621") (name "~{TP01_A}") (class "Default")
      (node (ref "A15") (pin "R2") (pinfunction "IN1_R2") (pintype "input"))
      (node (ref "A15") (pin "S2") (pinfunction "IN2_S2") (pintype "input"))
      (node (ref "A15") (pin "T2") (pinfunction "IN3_T2") (pintype "input"))
      (node (ref "A15") (pin "U2") (pinfunction "IN4_U2") (pintype "input"))
      (node (ref "B16") (pin "L2") (pinfunction "F2_L2") (pintype "output"))
    )
    (net (code "622") (name "~{TP1_XTLK_DY}") (class "Default")
      (node (ref "A11") (pin "V2") (pinfunction "OUT_V2") (pintype "output"))
      (node (ref "A15") (pin "B1") (pinfunction "IN2_B1") (pintype "input"))
      (node (ref "B16") (pin "H2") (pinfunction "H2_H2") (pintype "input"))
      (node (ref "B16") (pin "J2") (pinfunction "J2_J2") (pintype "input"))
    )
    (net (code "623") (name "~{TP01}") (class "Default")
      (node (ref "A15") (pin "J2") (pinfunction "OUT_J2") (pintype "output"))
      (node (ref "A15") (pin "K2") (pinfunction "IN1_K2") (pintype "input"))
      (node (ref "A15") (pin "L2") (pinfunction "IN2_L2") (pintype "input"))
      (node (ref "A15") (pin "M2") (pinfunction "IN3_M2") (pintype "input"))
      (node (ref "A15") (pin "N2") (pinfunction "IN4_N2") (pintype "input"))
      (node (ref "B13") (pin "L2") (pinfunction "C_L2") (pintype "input"))
    )
    (net (code "624") (name "~{TS03}") (class "Default")
      (node (ref "C04") (pin "K1") (pinfunction "OUT_K1") (pintype "output"))
      (node (ref "D17") (pin "H2") (pinfunction "H2_H2") (pintype "input"))
      (node (ref "D17") (pin "J2") (pinfunction "J2_J2") (pintype "input"))
      (node (ref "D17") (pin "K2") (pinfunction "K2_K2") (pintype "input"))
    )
    (net (code "625") (name "~{T_00}") (class "Default")
      (node (ref "A24") (pin "V2") (pinfunction "P$2_V2") (pintype "bidirectional"))
      (node (ref "B22") (pin "V2") (pinfunction "E_V2") (pintype "output"))
      (node (ref "B23") (pin "V2") (pinfunction "P$1_V2") (pintype "passive"))
    )
    (net (code "626") (name "~{T_01}") (class "Default")
      (node (ref "A23") (pin "S1") (pinfunction "E_S1") (pintype "output"))
      (node (ref "A24") (pin "M2") (pinfunction "P$2_M2") (pintype "bidirectional"))
      (node (ref "B23") (pin "M2") (pinfunction "P$1_M2") (pintype "passive"))
    )
    (net (code "627") (name "~{T_02}") (class "Default")
      (node (ref "A23") (pin "H2") (pinfunction "D_H2") (pintype "output"))
      (node (ref "A24") (pin "N2") (pinfunction "P$2_N2") (pintype "bidirectional"))
      (node (ref "B23") (pin "N2") (pinfunction "P$1_N2") (pintype "passive"))
    )
    (net (code "628") (name "~{T_03}") (class "Default")
      (node (ref "A23") (pin "J2") (pinfunction "E_J2") (pintype "output"))
      (node (ref "A24") (pin "P2") (pinfunction "P$2_P2") (pintype "bidirectional"))
      (node (ref "B23") (pin "P2") (pinfunction "P$1_P2") (pintype "passive"))
    )
    (net (code "629") (name "~{T_04}") (class "Default")
      (node (ref "A23") (pin "N2") (pinfunction "D_N2") (pintype "output"))
      (node (ref "A24") (pin "R2") (pinfunction "P$2_R2") (pintype "bidirectional"))
      (node (ref "B23") (pin "R2") (pinfunction "P$1_R2") (pintype "passive"))
    )
    (net (code "630") (name "~{T_05}") (class "Default")
      (node (ref "A23") (pin "P2") (pinfunction "E_P2") (pintype "output"))
      (node (ref "A24") (pin "S2") (pinfunction "P$2_S2") (pintype "bidirectional"))
      (node (ref "B23") (pin "S2") (pinfunction "P$1_S2") (pintype "passive"))
    )
    (net (code "631") (name "~{T_06}") (class "Default")
      (node (ref "A23") (pin "U2") (pinfunction "D_U2") (pintype "output"))
      (node (ref "A24") (pin "T2") (pinfunction "P$2_T2") (pintype "bidirectional"))
      (node (ref "B23") (pin "T2") (pinfunction "P$1_T2") (pintype "passive"))
    )
    (net (code "632") (name "~{T_07}") (class "Default")
      (node (ref "A23") (pin "V2") (pinfunction "E_V2") (pintype "output"))
      (node (ref "A24") (pin "U2") (pinfunction "P$2_U2") (pintype "bidirectional"))
      (node (ref "B23") (pin "U2") (pinfunction "P$1_U2") (pintype "passive"))
    )
    (net (code "633") (name "~{T_FWD}") (class "Default")
      (node (ref "A23") (pin "K1") (pinfunction "D_K1") (pintype "output"))
      (node (ref "A24") (pin "E2") (pinfunction "P$2_E2") (pintype "bidirectional"))
      (node (ref "B23") (pin "H2") (pinfunction "P$1_H2") (pintype "passive"))
    )
    (net (code "634") (name "~{T_GO}") (class "Default")
      (node (ref "A23") (pin "D1") (pinfunction "D_D1") (pintype "output"))
      (node (ref "A24") (pin "C2") (pinfunction "P$2_C2") (pintype "bidirectional"))
      (node (ref "B23") (pin "D2") (pinfunction "P$1_D2") (pintype "passive"))
    )
    (net (code "635") (name "~{T_PWR_CLR}") (class "Default")
      (node (ref "A23") (pin "R1") (pinfunction "D_R1") (pintype "output"))
      (node (ref "A24") (pin "H2") (pinfunction "P$2_H2") (pintype "bidirectional"))
      (node (ref "B23") (pin "K2") (pinfunction "P$1_K2") (pintype "passive"))
    )
    (net (code "636") (name "~{T_REV}") (class "Default")
      (node (ref "A23") (pin "L1") (pinfunction "E_L1") (pintype "output"))
      (node (ref "A24") (pin "F2") (pinfunction "P$2_F2") (pintype "bidirectional"))
      (node (ref "B23") (pin "J2") (pinfunction "P$1_J2") (pintype "passive"))
    )
    (net (code "637") (name "~{T_SINGLE_UNIT}") (class "Default")
      (node (ref "A24") (pin "K2") (pinfunction "P$2_K2") (pintype "bidirectional"))
      (node (ref "B21") (pin "T2") (pinfunction "IN_T2") (pintype "input"))
    )
    (net (code "638") (name "~{T_STOP}") (class "Default")
      (node (ref "A23") (pin "E1") (pinfunction "E_E1") (pintype "output"))
      (node (ref "A24") (pin "D2") (pinfunction "P$2_D2") (pintype "bidirectional"))
      (node (ref "B23") (pin "E2") (pinfunction "P$1_E2") (pintype "passive"))
    )
    (net (code "639") (name "~{T_TRK}") (class "Default")
      (node (ref "A18") (pin "V2") (pinfunction "V2_V2") (pintype "output"))
      (node (ref "B15") (pin "E1") (pinfunction "IN2_E1") (pintype "input"))
    )
    (net (code "640") (name "~{T_WRITE_OK}") (class "Default")
      (node (ref "A22") (pin "H2") (pinfunction "H2_H2") (pintype "input"))
      (node (ref "A24") (pin "L2") (pinfunction "P$2_L2") (pintype "bidirectional"))
      (node (ref "B23") (pin "L2") (pinfunction "P$1_L2") (pintype "passive"))
    )
    (net (code "641") (name "~{U+M_DY}") (class "Default")
      (node (ref "C12") (pin "A1") (pinfunction "IN1_A1") (pintype "input"))
      (node (ref "C12") (pin "R2") (pinfunction "IN3_R2") (pintype "input"))
      (node (ref "D14") (pin "E2") (pinfunction "F2_E2") (pintype "output"))
      (node (ref "D14") (pin "N1") (pinfunction "N1_N1") (pintype "input"))
    )
    (net (code "642") (name "~{USR_00}") (class "Default")
      (node (ref "B03") (pin "A1") (pinfunction "A_A1") (pintype "input"))
      (node (ref "B07") (pin "F1") (pinfunction "F1_F1") (pintype "output"))
    )
    (net (code "643") (name "~{USR_01}") (class "Default")
      (node (ref "B03") (pin "B1") (pinfunction "B_B1") (pintype "input"))
      (node (ref "B07") (pin "J2") (pinfunction "J2_J2") (pintype "output"))
    )
    (net (code "644") (name "~{USR_02}") (class "Default")
      (node (ref "B03") (pin "F1") (pinfunction "A_F1") (pintype "input"))
      (node (ref "B07") (pin "M1") (pinfunction "M1_M1") (pintype "output"))
    )
    (net (code "645") (name "~{UTS}") (class "Default")
      (node (ref "C12") (pin "L2") (pinfunction "IN3_L2") (pintype "input"))
      (node (ref "C14") (pin "P2") (pinfunction "1_P2") (pintype "output"))
      (node (ref "C15") (pin "P2") (pinfunction "IN1_P2") (pintype "input"))
      (node (ref "C16") (pin "A1") (pinfunction "IN1_A1") (pintype "input"))
      (node (ref "C16") (pin "B1") (pinfunction "IN2_B1") (pintype "input"))
      (node (ref "C16") (pin "C1") (pinfunction "IN3_C1") (pintype "input"))
      (node (ref "C16") (pin "D1") (pinfunction "IN4_D1") (pintype "input"))
      (node (ref "C16") (pin "F1") (pinfunction "IN1_F1") (pintype "input"))
      (node (ref "C16") (pin "H1") (pinfunction "IN2_H1") (pintype "input"))
      (node (ref "C16") (pin "J1") (pinfunction "IN3_J1") (pintype "input"))
      (node (ref "C16") (pin "K1") (pinfunction "IN4_K1") (pintype "input"))
    )
    (net (code "646") (name "~{W-INH}") (class "Default")
      (node (ref "A08") (pin "V2") (pinfunction "1_V2") (pintype "output"))
      (node (ref "B11") (pin "L1") (pinfunction "IN2_L1") (pintype "input"))
      (node (ref "B12") (pin "H1") (pinfunction "IN2_H1") (pintype "input"))
    )
    (net (code "647") (name "~{WB00}") (class "Default")
      (node (ref "A21") (pin "P2") (pinfunction "P2_P2") (pintype "input"))
      (node (ref "B18") (pin "P2") (pinfunction "P2_P2") (pintype "input"))
      (node (ref "C10") (pin "D1") (pinfunction "IN2B_D1") (pintype "input"))
      (node (ref "C14") (pin "E1") (pinfunction "1_E1") (pintype "output"))
    )
    (net (code "648") (name "~{WB01}") (class "Default")
      (node (ref "B20") (pin "P2") (pinfunction "P2_P2") (pintype "input"))
      (node (ref "C10") (pin "K1") (pinfunction "IN2B_K1") (pintype "input"))
      (node (ref "C14") (pin "H2") (pinfunction "1_H2") (pintype "output"))
    )
    (net (code "649") (name "~{WB02}") (class "Default")
      (node (ref "A20") (pin "P2") (pinfunction "P2_P2") (pintype "input"))
      (node (ref "C10") (pin "R1") (pinfunction "IN2B_R1") (pintype "input"))
      (node (ref "C14") (pin "L1") (pinfunction "1_L1") (pintype "output"))
    )
    (net (code "650") (name "~{WC0}") (class "Default")
      (node (ref "C06") (pin "N2") (pinfunction "OUT_N2") (pintype "output"))
      (node (ref "D11") (pin "R1") (pinfunction "S_R1") (pintype "input"))
    )
    (net (code "651") (name "~{WC}") (class "Default")
      (node (ref "B12") (pin "F2") (pinfunction "IN3_F2") (pintype "input"))
      (node (ref "C12") (pin "T2") (pinfunction "IN1_T2") (pintype "input"))
      (node (ref "D11") (pin "M2") (pinfunction "D_M2") (pintype "input"))
      (node (ref "D11") (pin "U1") (pinfunction "0_U1") (pintype "output"))
    )
    (net (code "652") (name "~{WRITE_ALL}") (class "Default")
      (node (ref "D07") (pin "M1") (pinfunction "~{O5}_M1") (pintype "output"))
    )
    (net (code "653") (name "~{WRITE_DATA}") (class "Default")
      (node (ref "B08") (pin "M2") (pinfunction "IN2_M2") (pintype "input"))
      (node (ref "D07") (pin "F1") (pinfunction "~{O4}_F1") (pintype "output"))
    )
    (net (code "654") (name "~{WRITE_OK}") (class "Default")
      (node (ref "A10") (pin "J1") (pinfunction "IN2_J1") (pintype "input"))
      (node (ref "C17") (pin "J2") (pinfunction "OUT_J2") (pintype "output"))
    )
    (net (code "655") (name "~{WRTM}") (class "Default")
      (node (ref "B08") (pin "H2") (pinfunction "IN1_H2") (pintype "input"))
      (node (ref "C10") (pin "M2") (pinfunction "IN2A_M2") (pintype "input"))
      (node (ref "D07") (pin "H1") (pinfunction "~{O6}_H1") (pintype "output"))
    )
    (net (code "656") (name "~{WR_EN}") (class "Default")
      (node (ref "B11") (pin "F1") (pinfunction "IN2_F1") (pintype "input"))
      (node (ref "C11") (pin "H2") (pinfunction "IN1_H2") (pintype "input"))
      (node (ref "C12") (pin "J2") (pinfunction "IN1_J2") (pintype "input"))
      (node (ref "C14") (pin "S1") (pinfunction "1_S1") (pintype "output"))
      (node (ref "C15") (pin "D2") (pinfunction "IN1_D2") (pintype "input"))
      (node (ref "C15") (pin "H2") (pinfunction "IN1_H2") (pintype "input"))
    )
    (net (code "657") (name "~{XSAD}") (class "Default")
      (node (ref "A11") (pin "K2") (pinfunction "IN_K2") (pintype "input"))
      (node (ref "D13") (pin "L2") (pinfunction "F2_L2") (pintype "output"))
    )
    (net (code "658") (name "~{XSTA}") (class "Default")
      (node (ref "B08") (pin "R2") (pinfunction "IN2_R2") (pintype "input"))
      (node (ref "C04") (pin "F1") (pinfunction "F1_F1") (pintype "output"))
      (node (ref "D13") (pin "H2") (pinfunction "H2_H2") (pintype "input"))
      (node (ref "D13") (pin "J2") (pinfunction "J2_J2") (pintype "input"))
      (node (ref "D13") (pin "K2") (pinfunction "K2_K2") (pintype "input"))
      (node (ref "D14") (pin "K2") (pinfunction "U1_K2") (pintype "input"))
      (node (ref "D14") (pin "L2") (pinfunction "S1_L2") (pintype "input"))
      (node (ref "D16") (pin "M2") (pinfunction "H2_M2") (pintype "input"))
      (node (ref "D16") (pin "N2") (pinfunction "J2_N2") (pintype "input"))
    )
  )
)
